# 2x16MUX_1.net
KiCad netlist of a schematic drawn in EAGLE
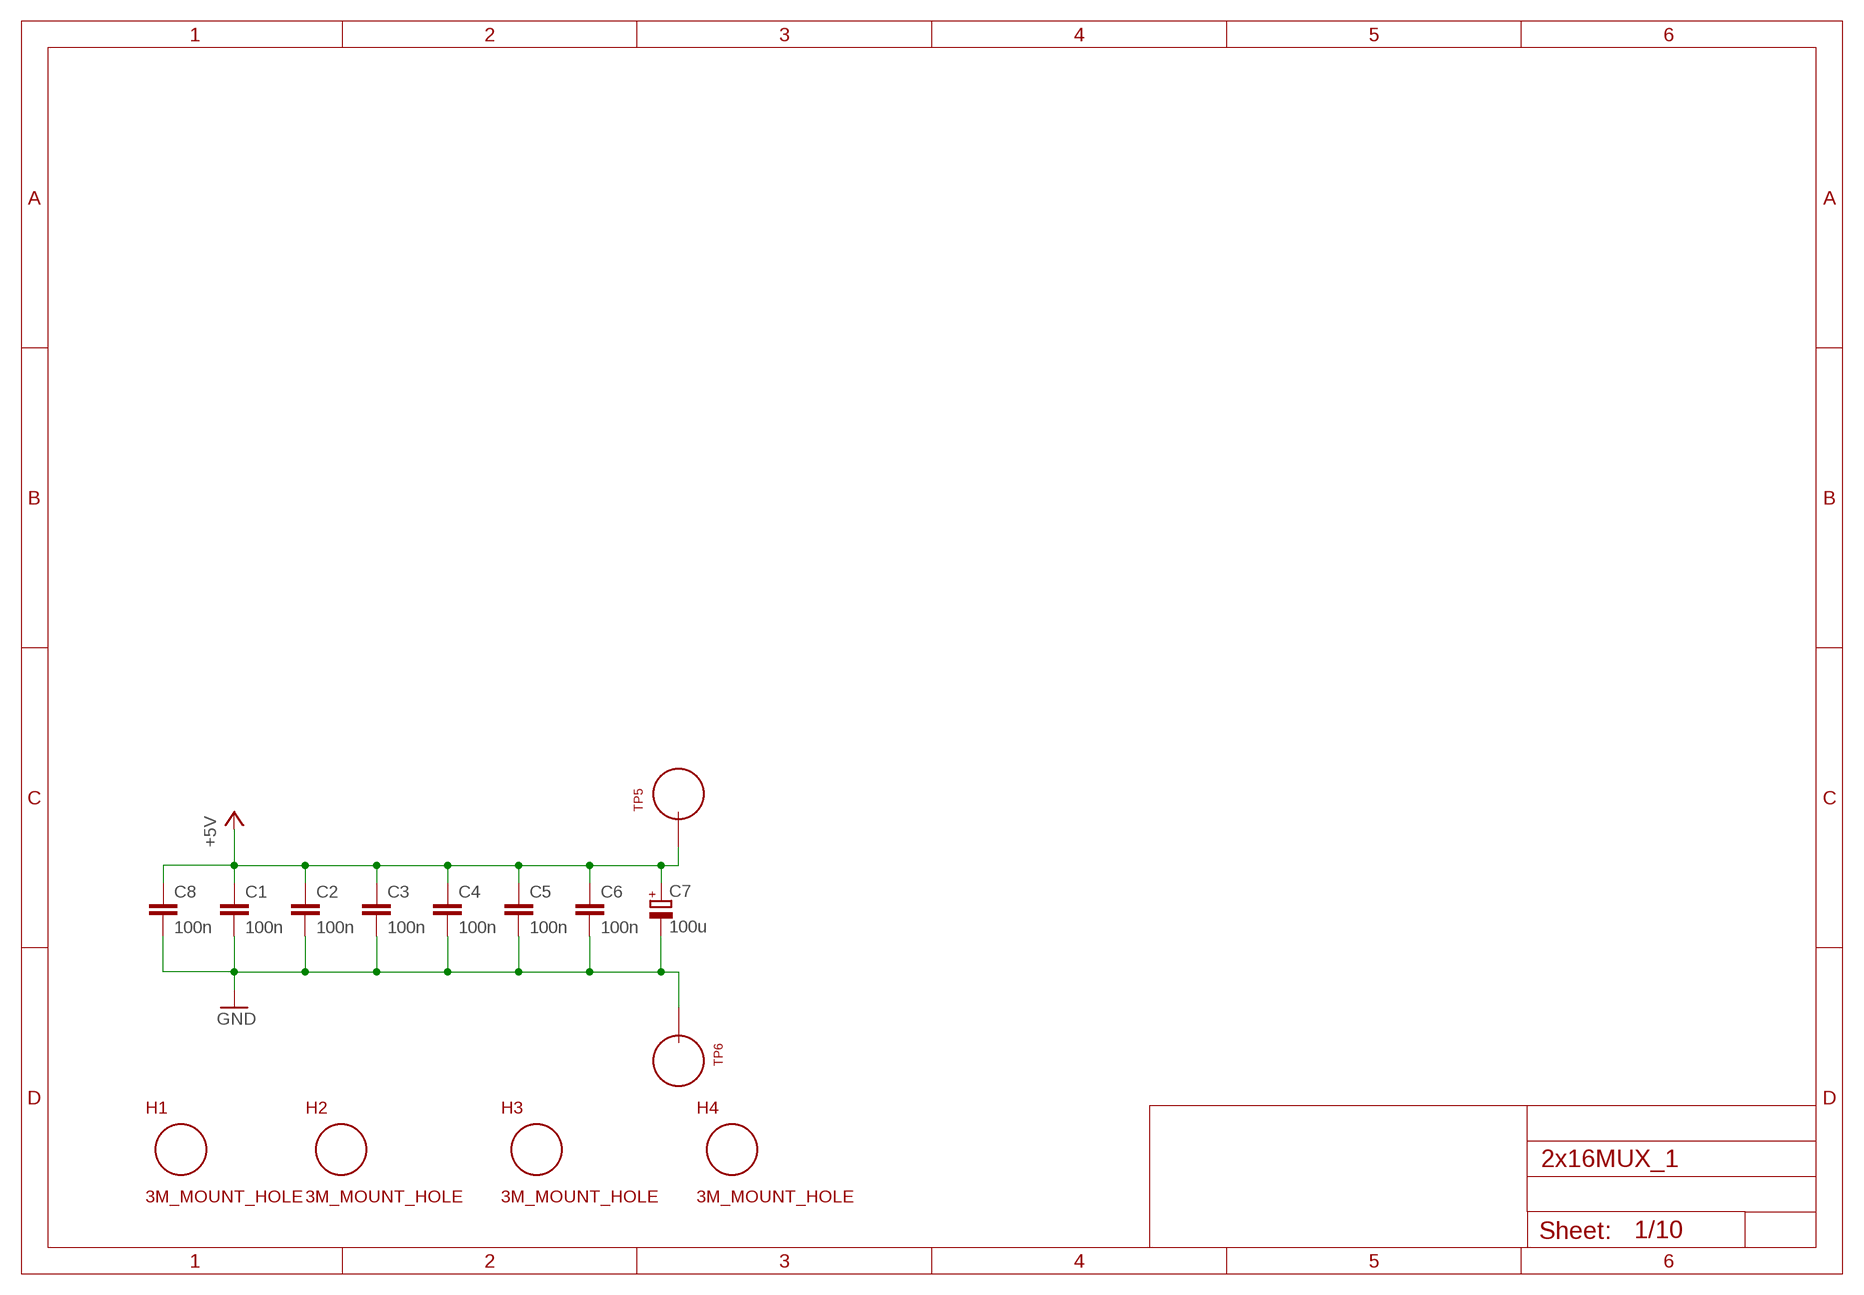
[diagram p0: schematic, sheet 1]
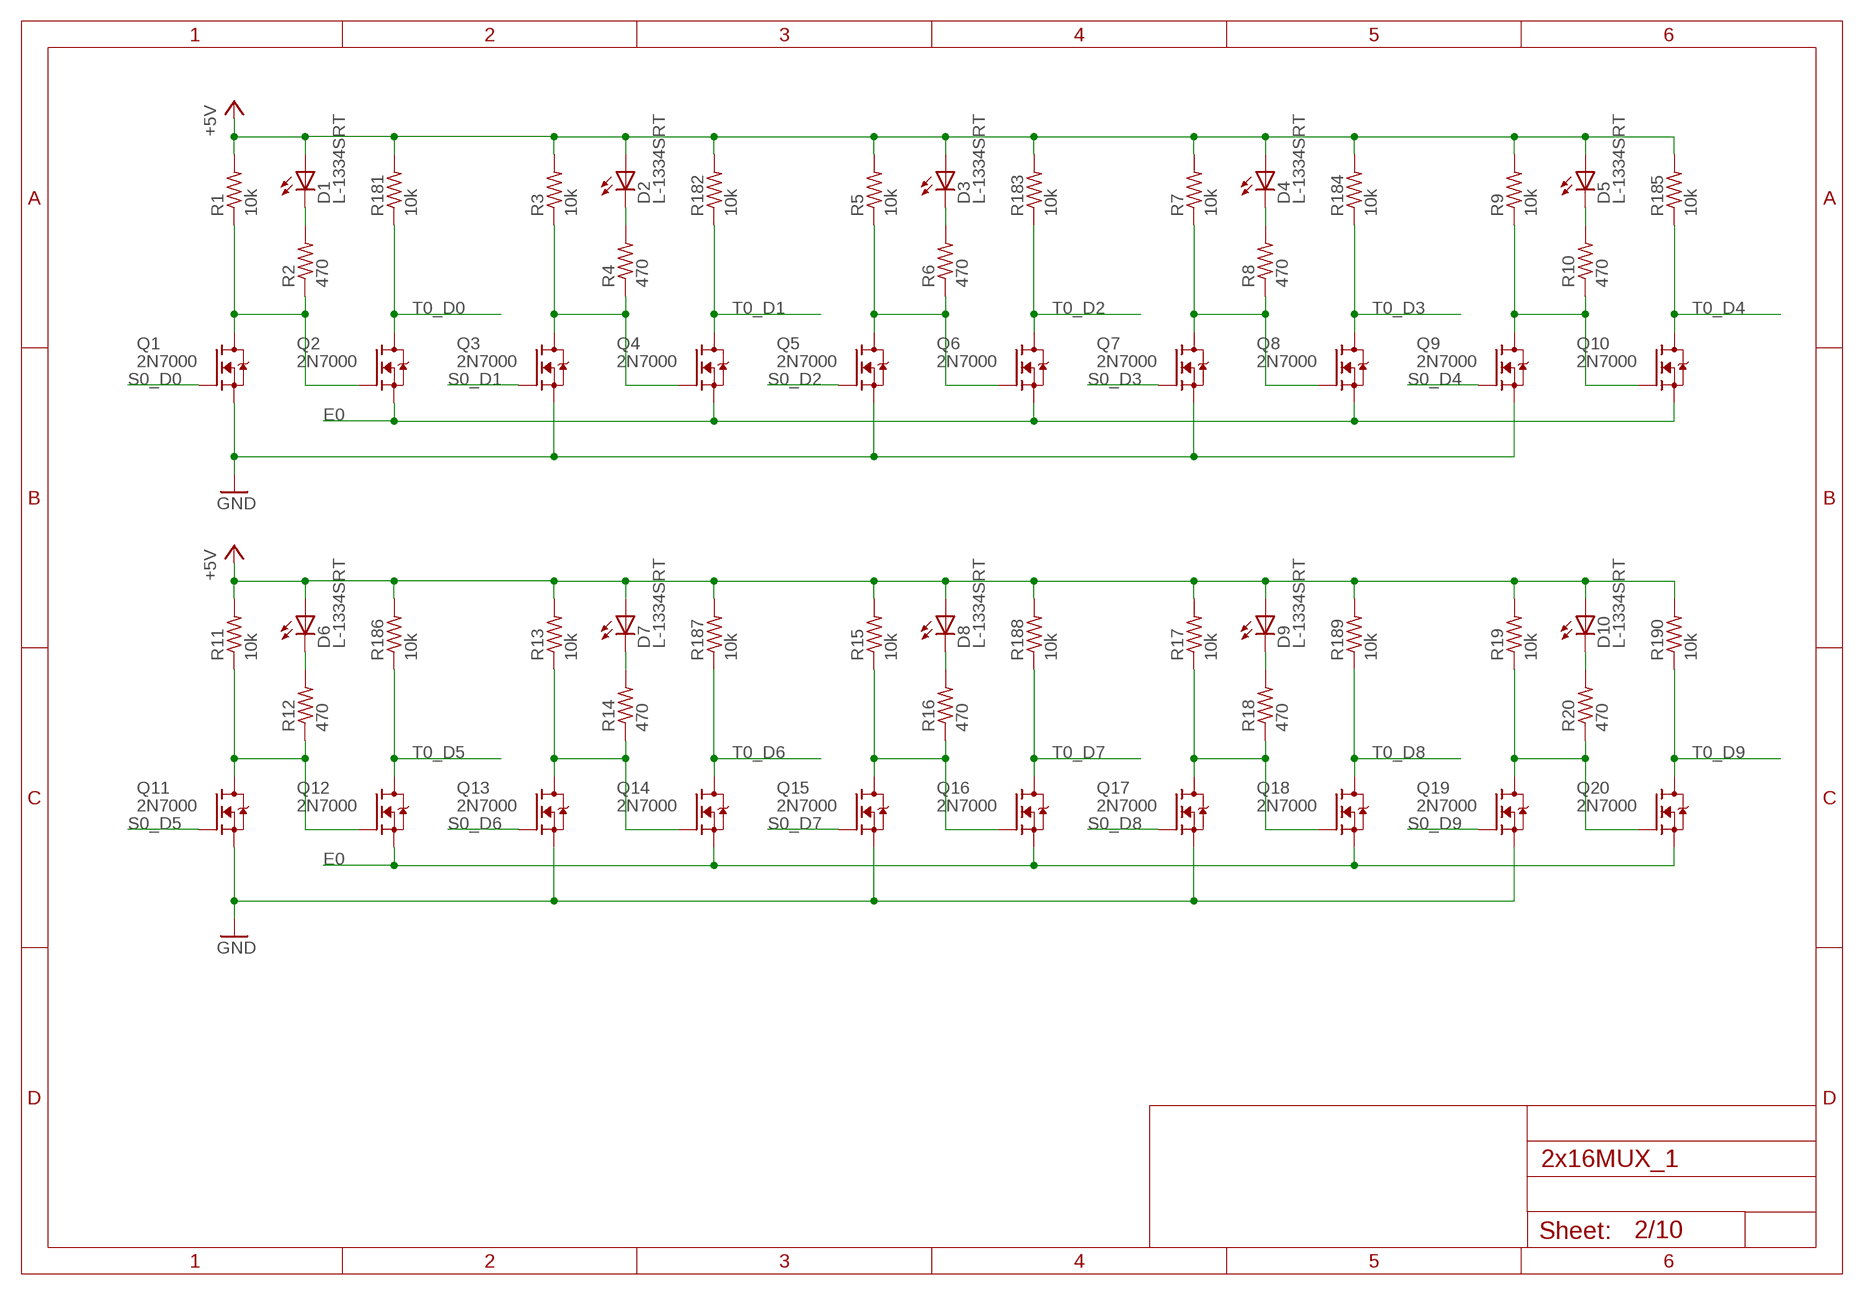
[diagram p1: schematic, sheet 2]
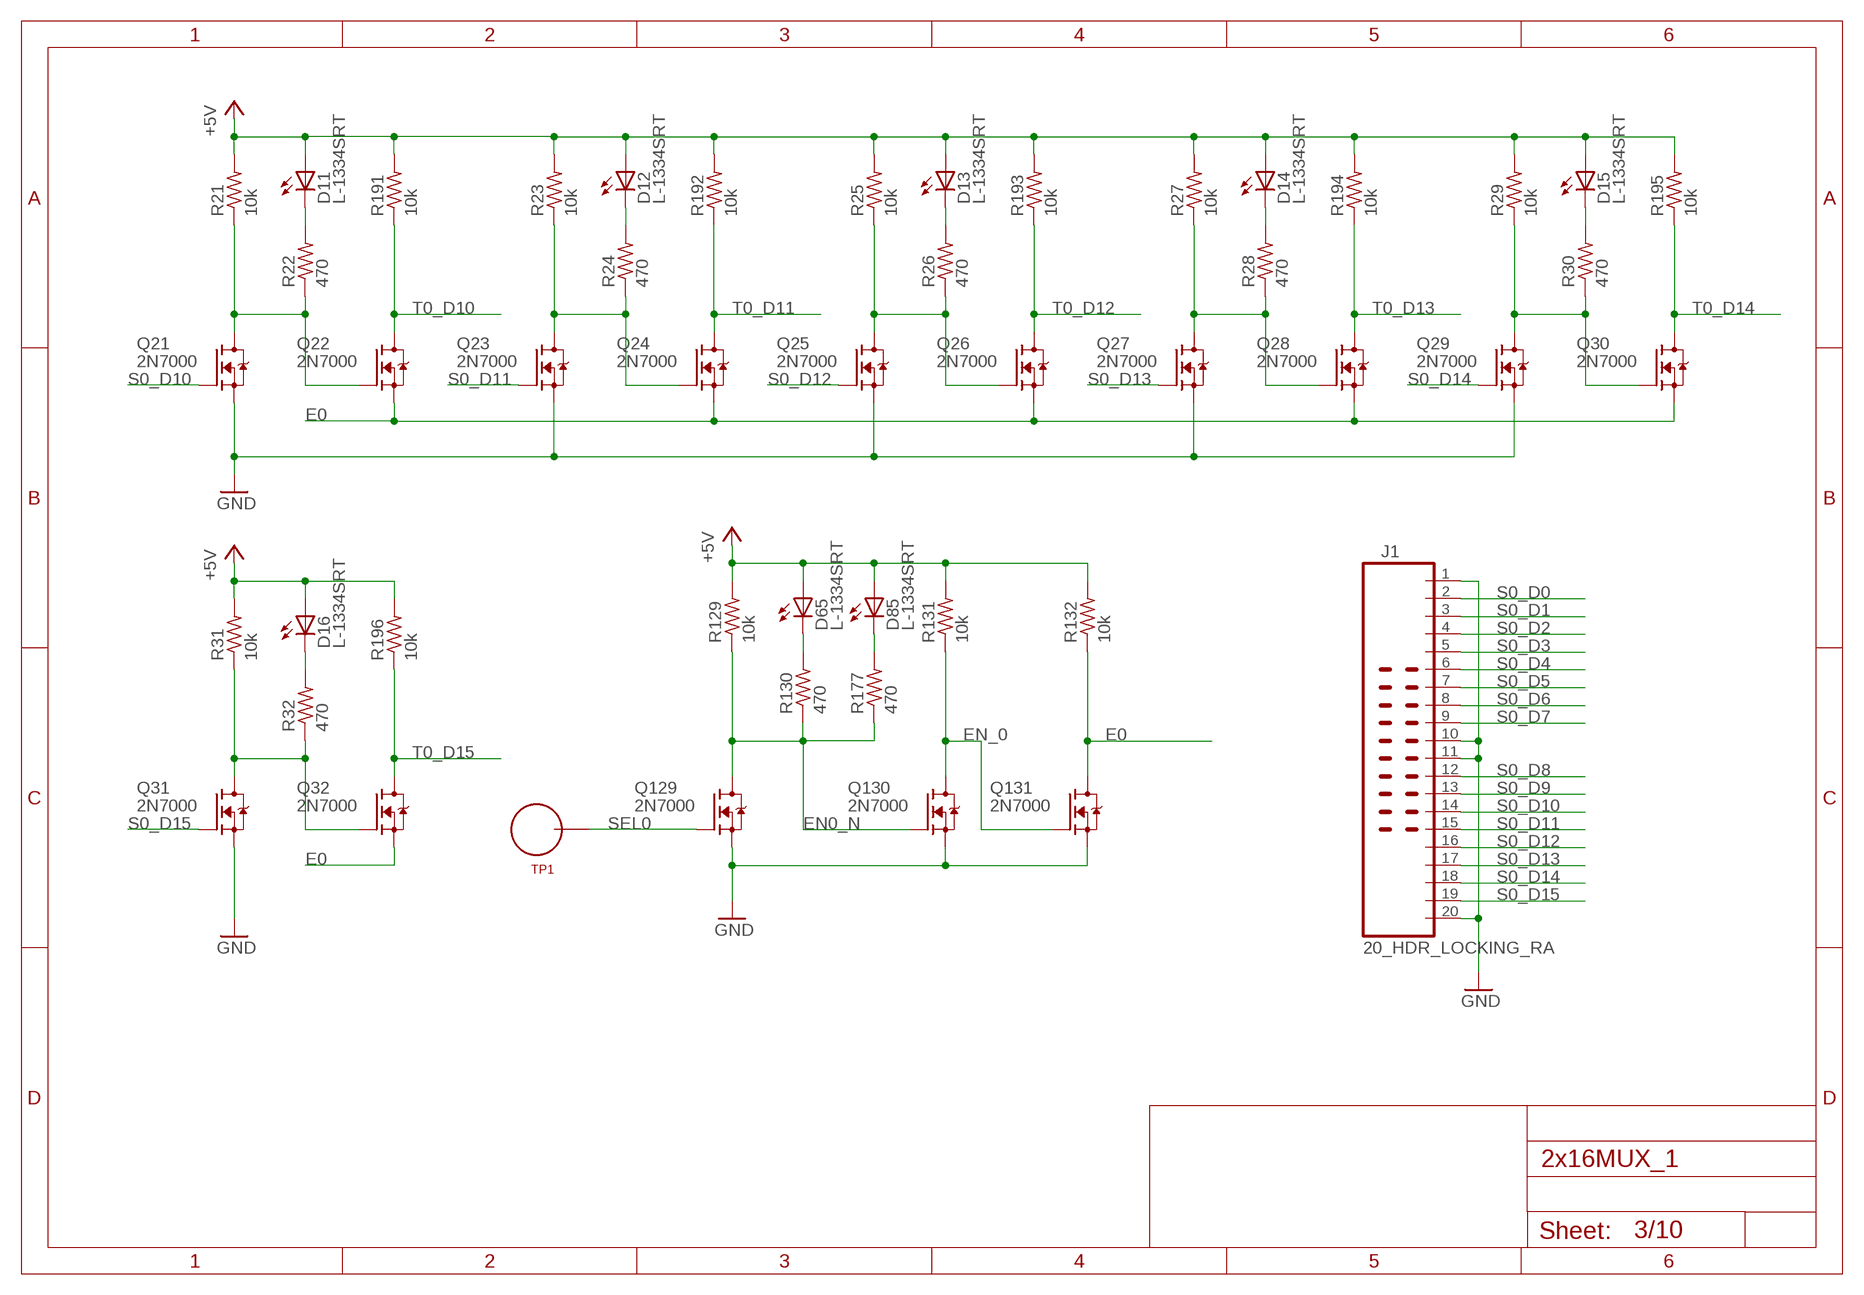
[diagram p2: schematic, sheet 3]
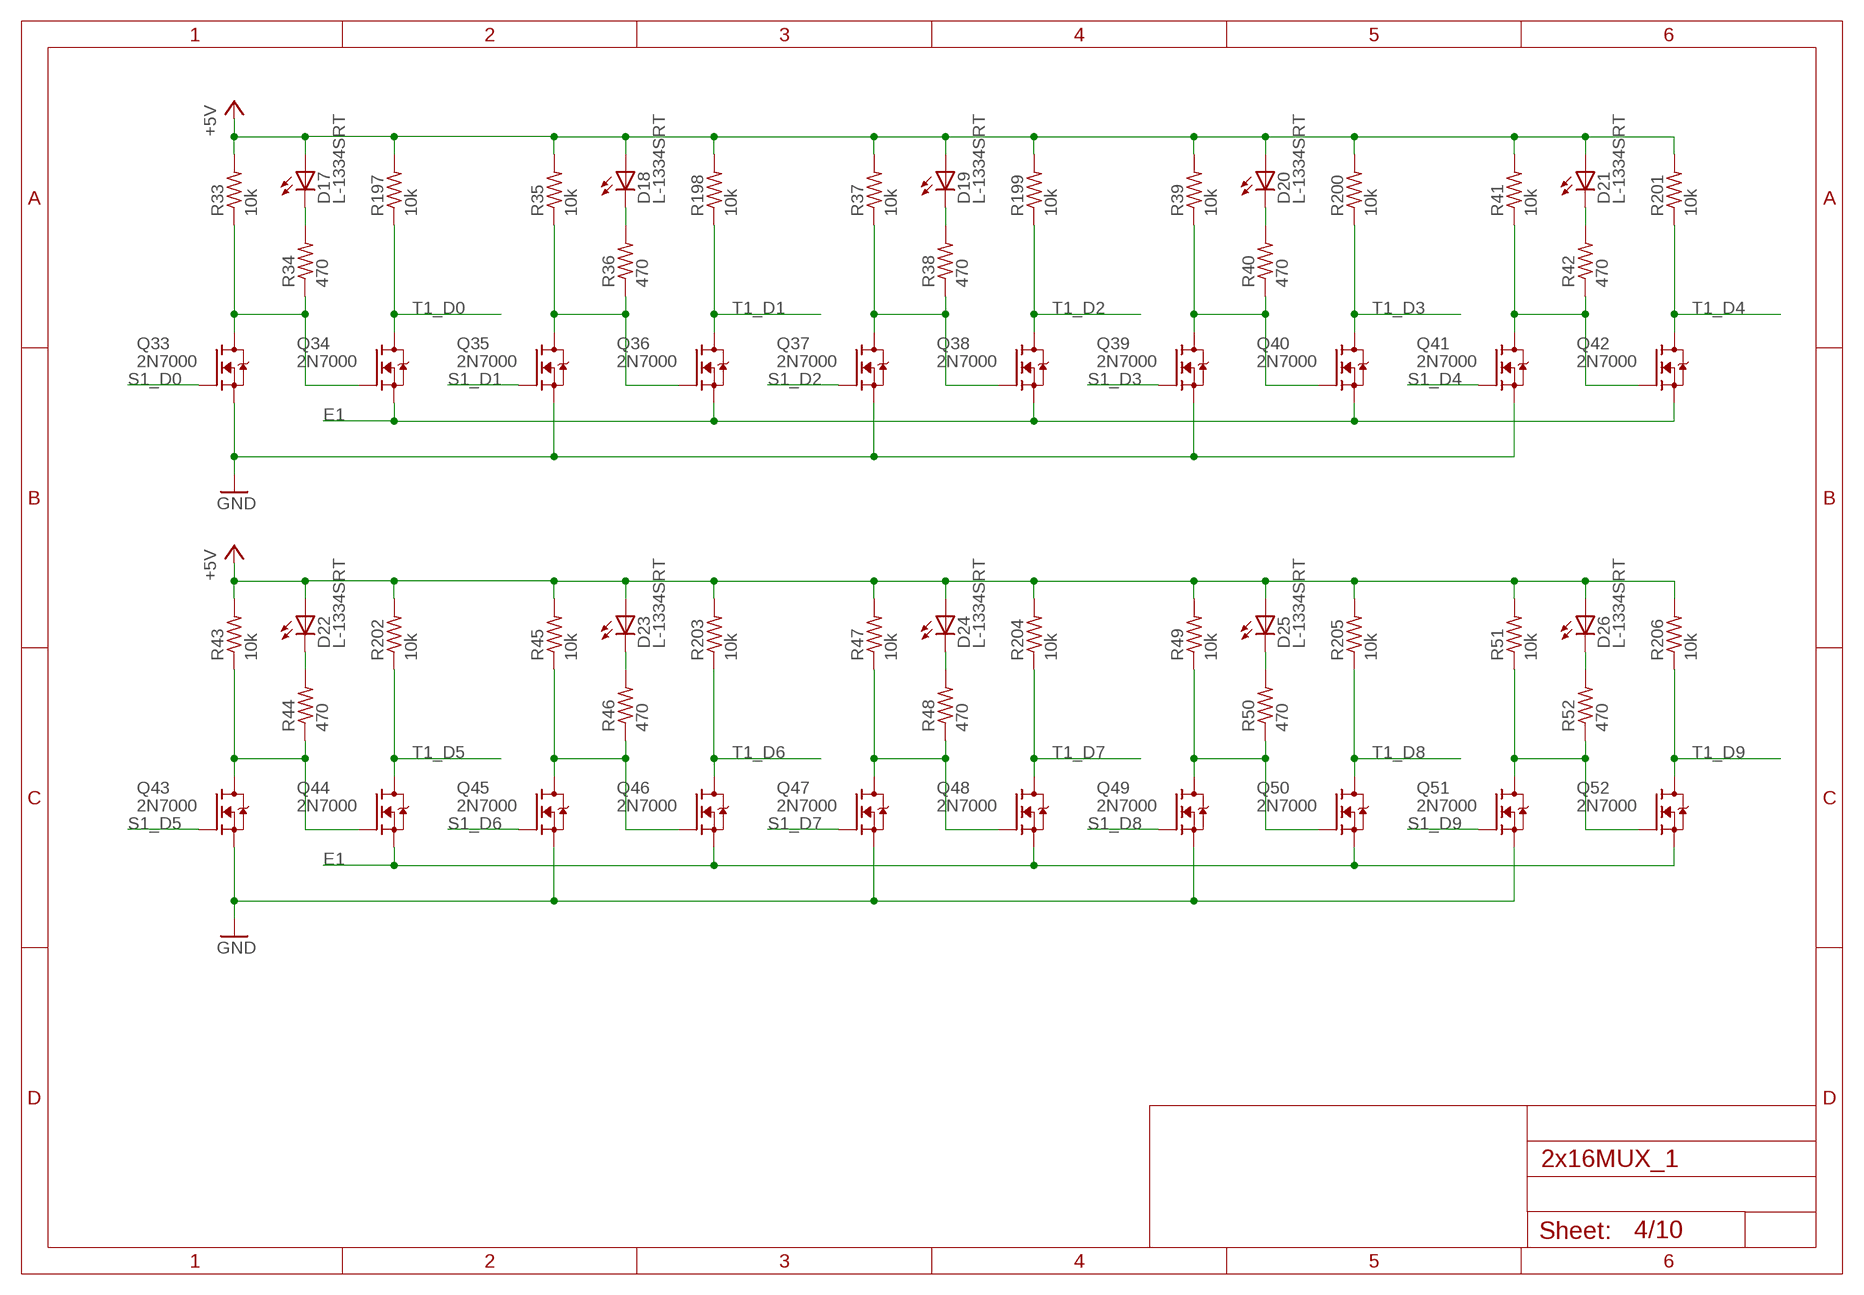
[diagram p3: schematic, sheet 4]
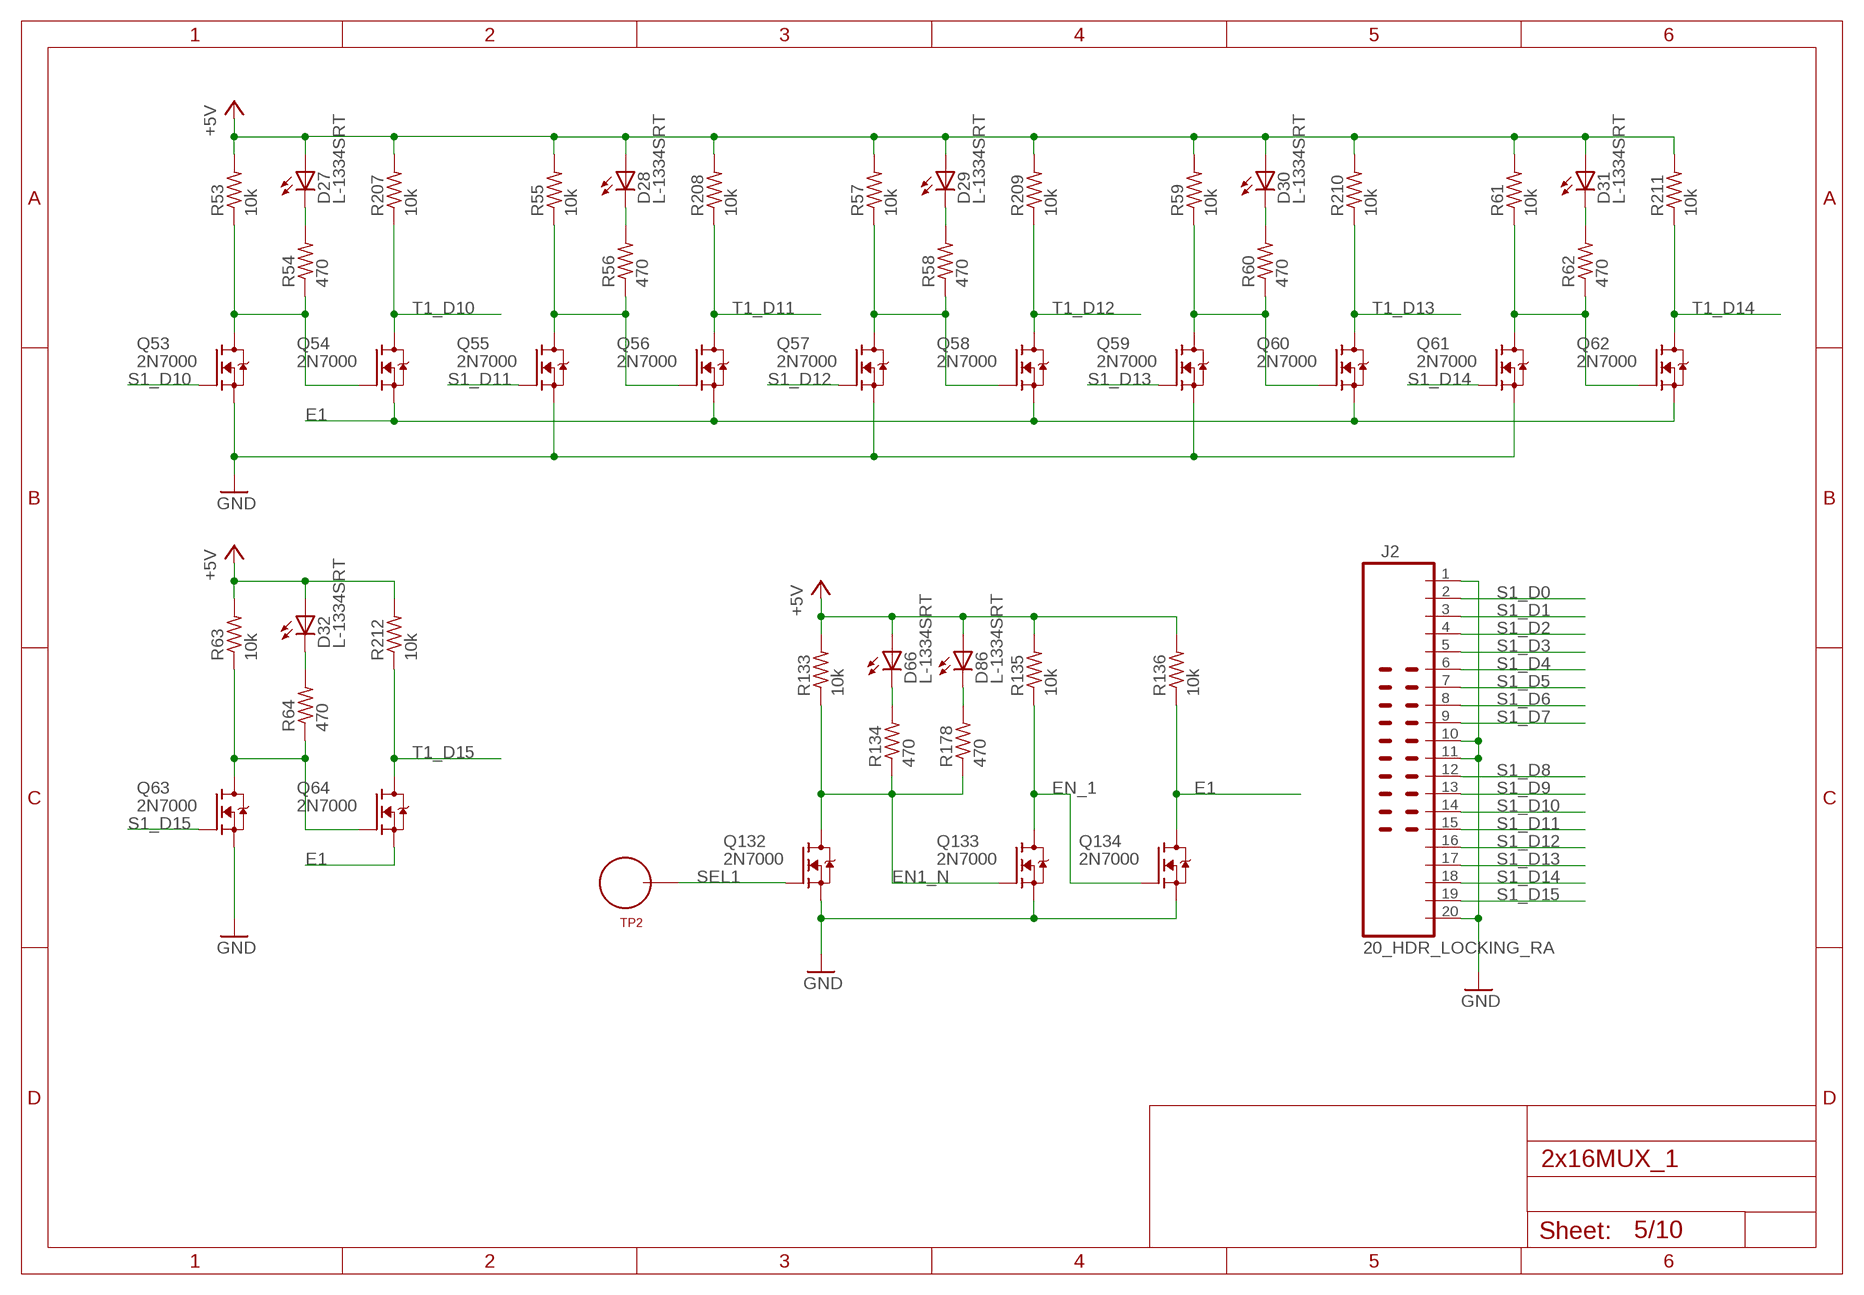
[diagram p4: schematic, sheet 5]
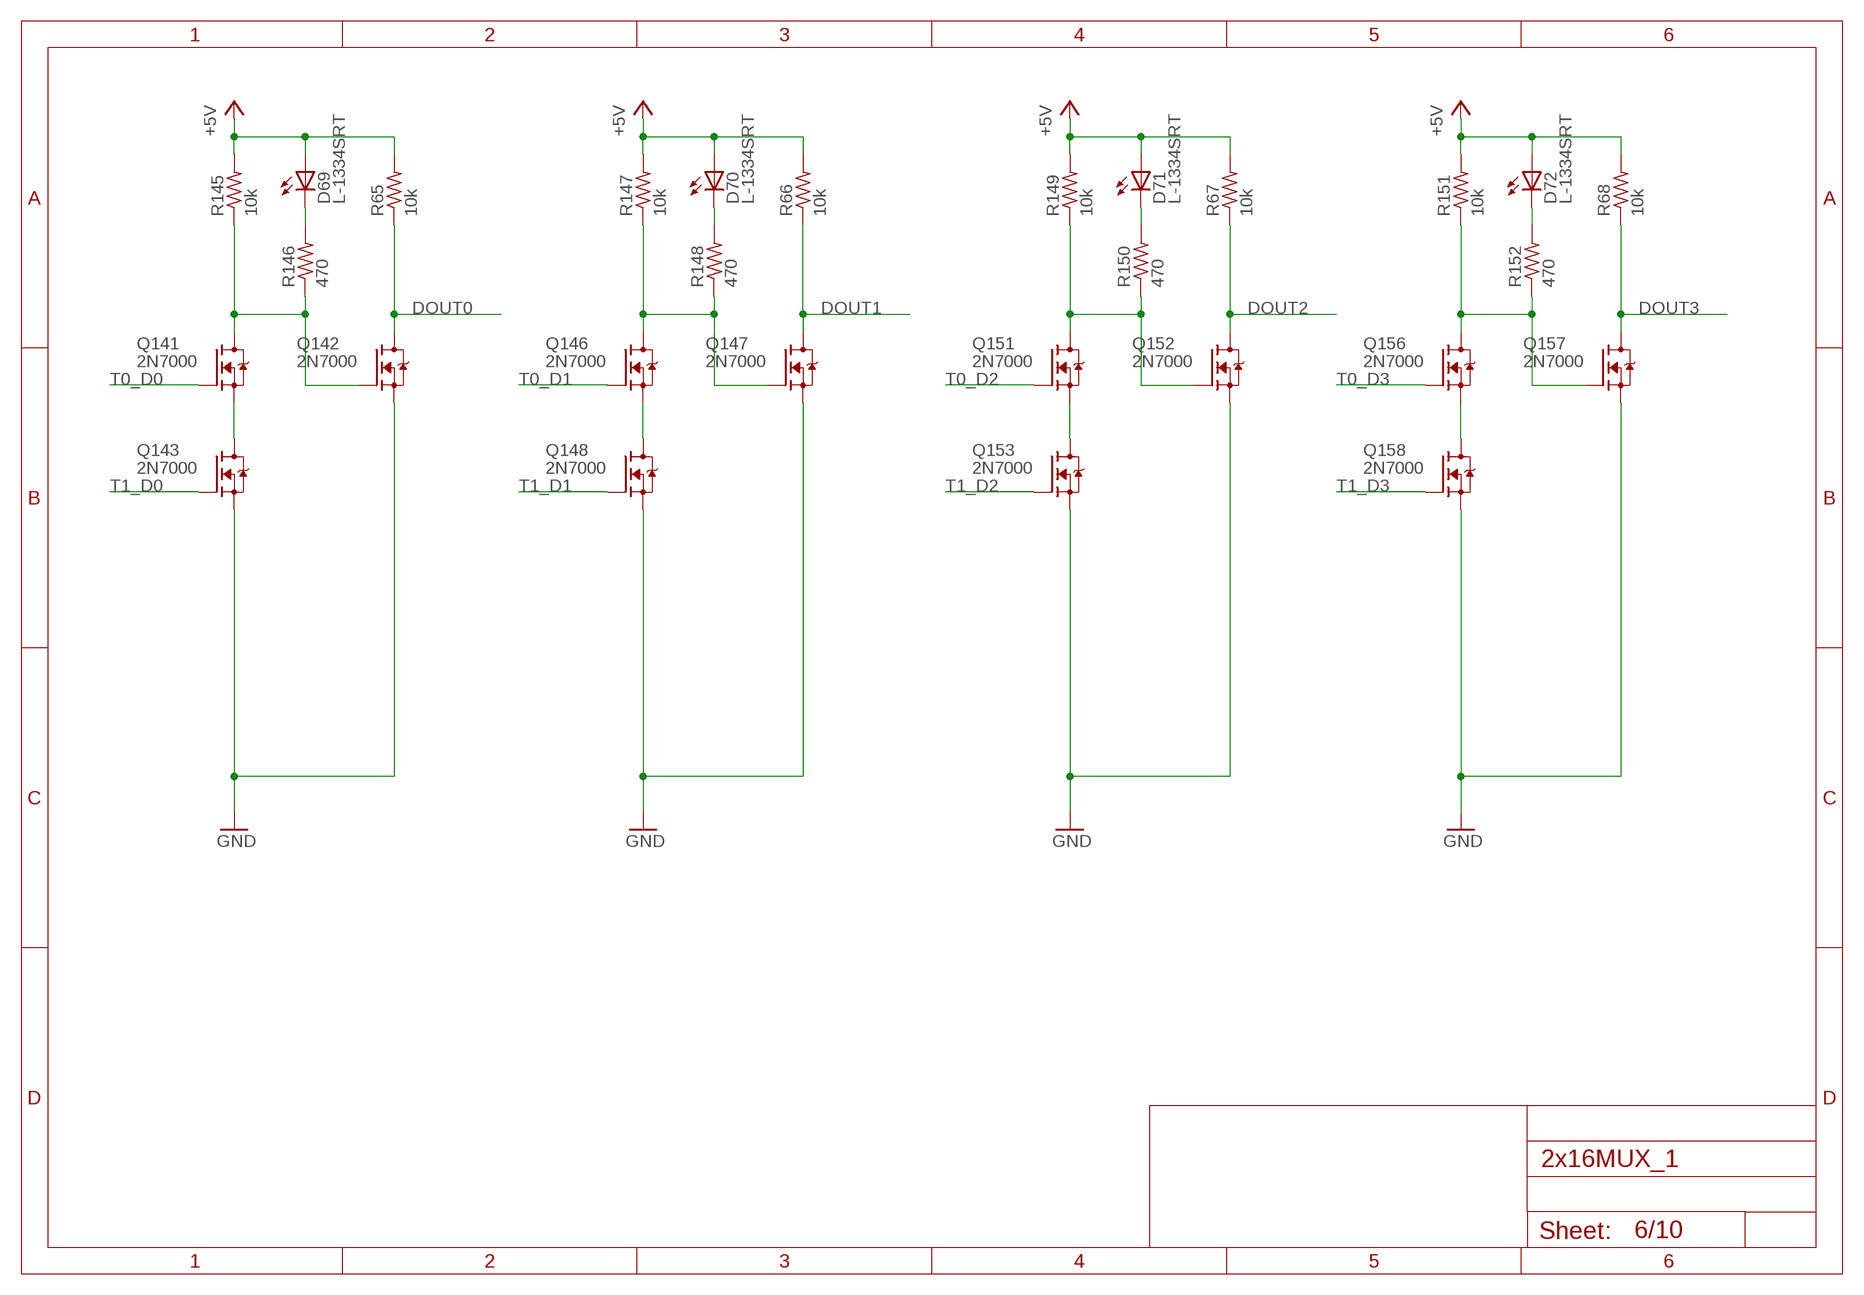
[diagram p5: schematic, sheet 6]
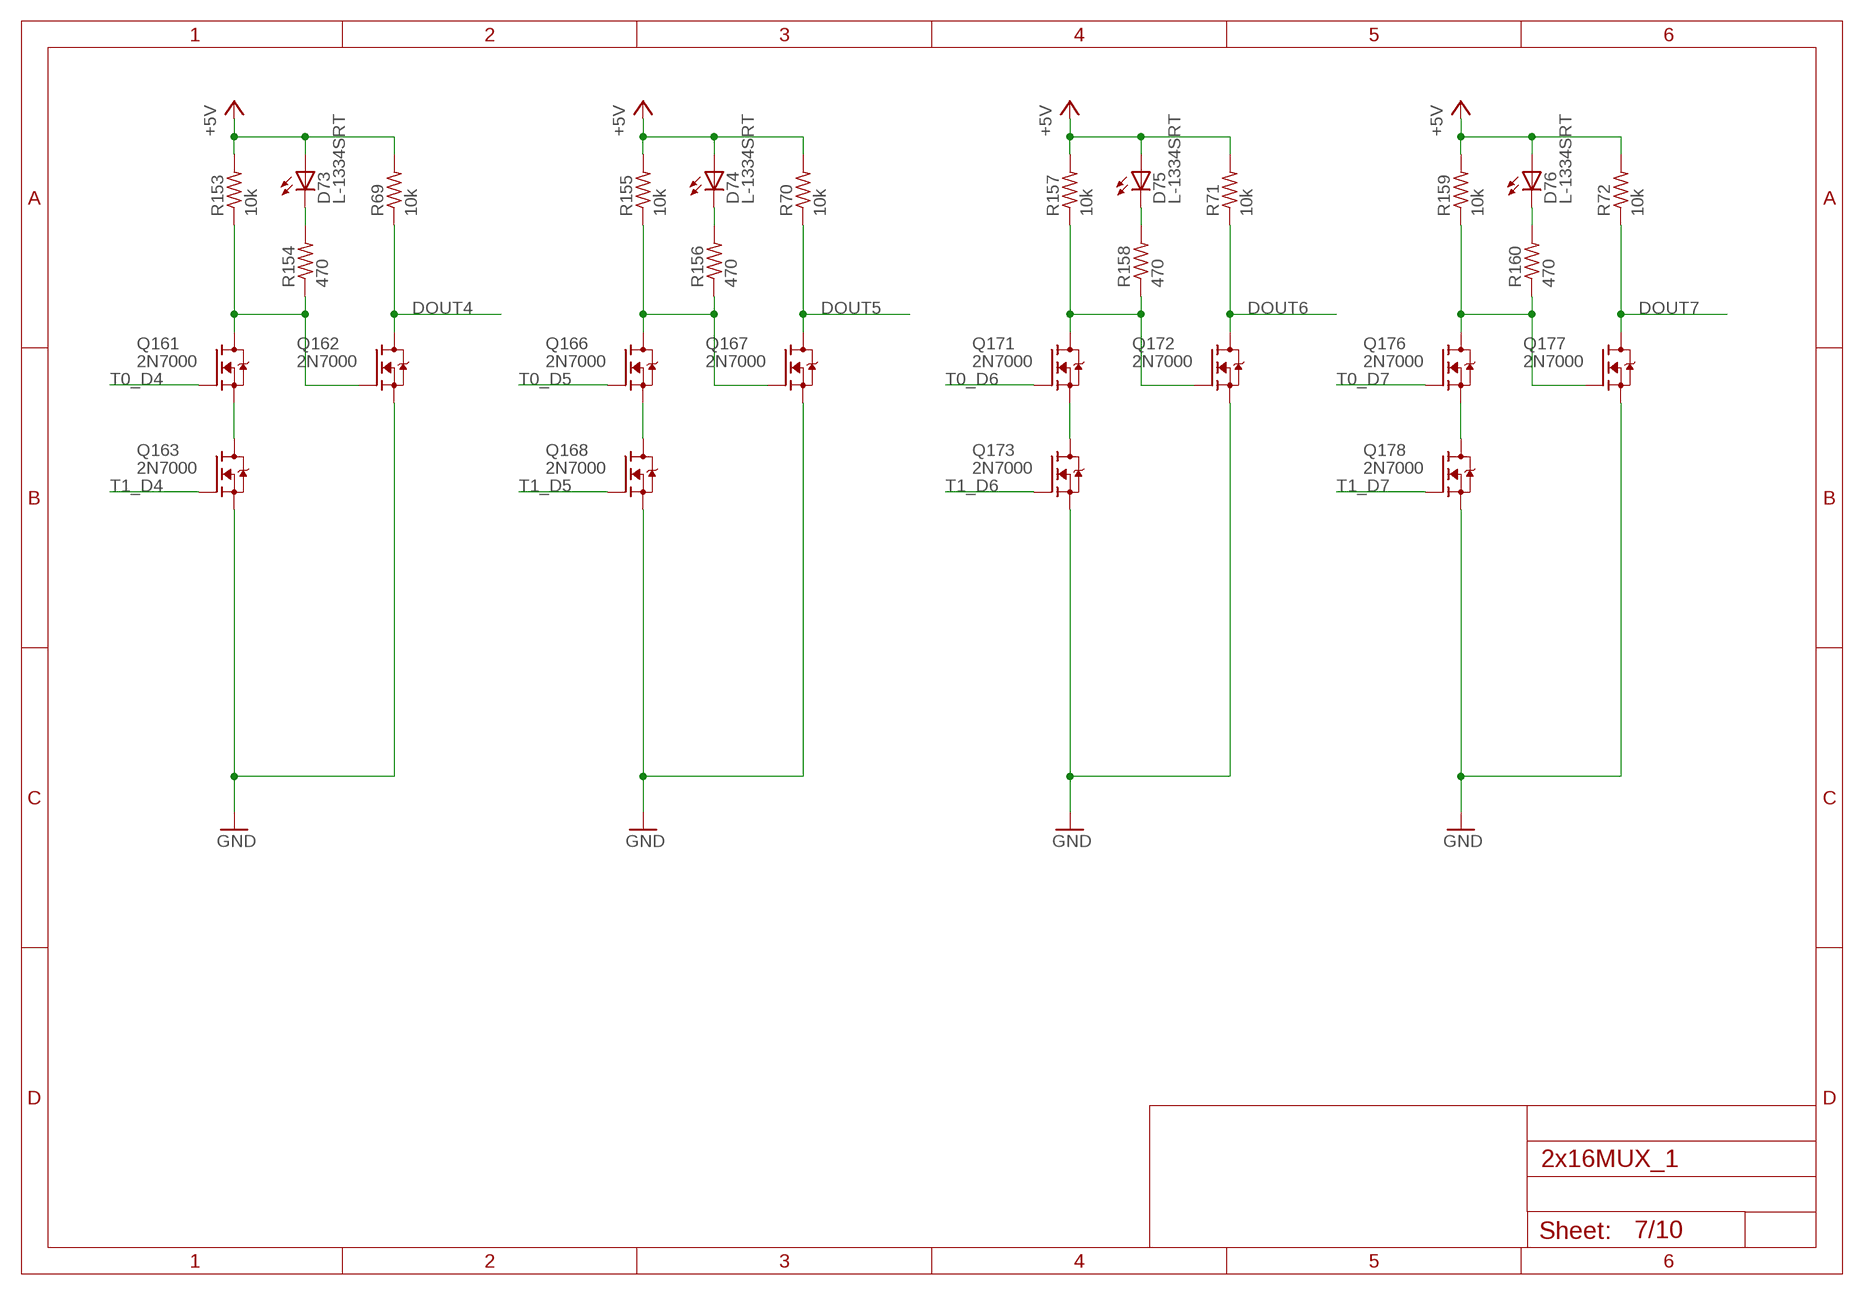
[diagram p6: schematic, sheet 7]
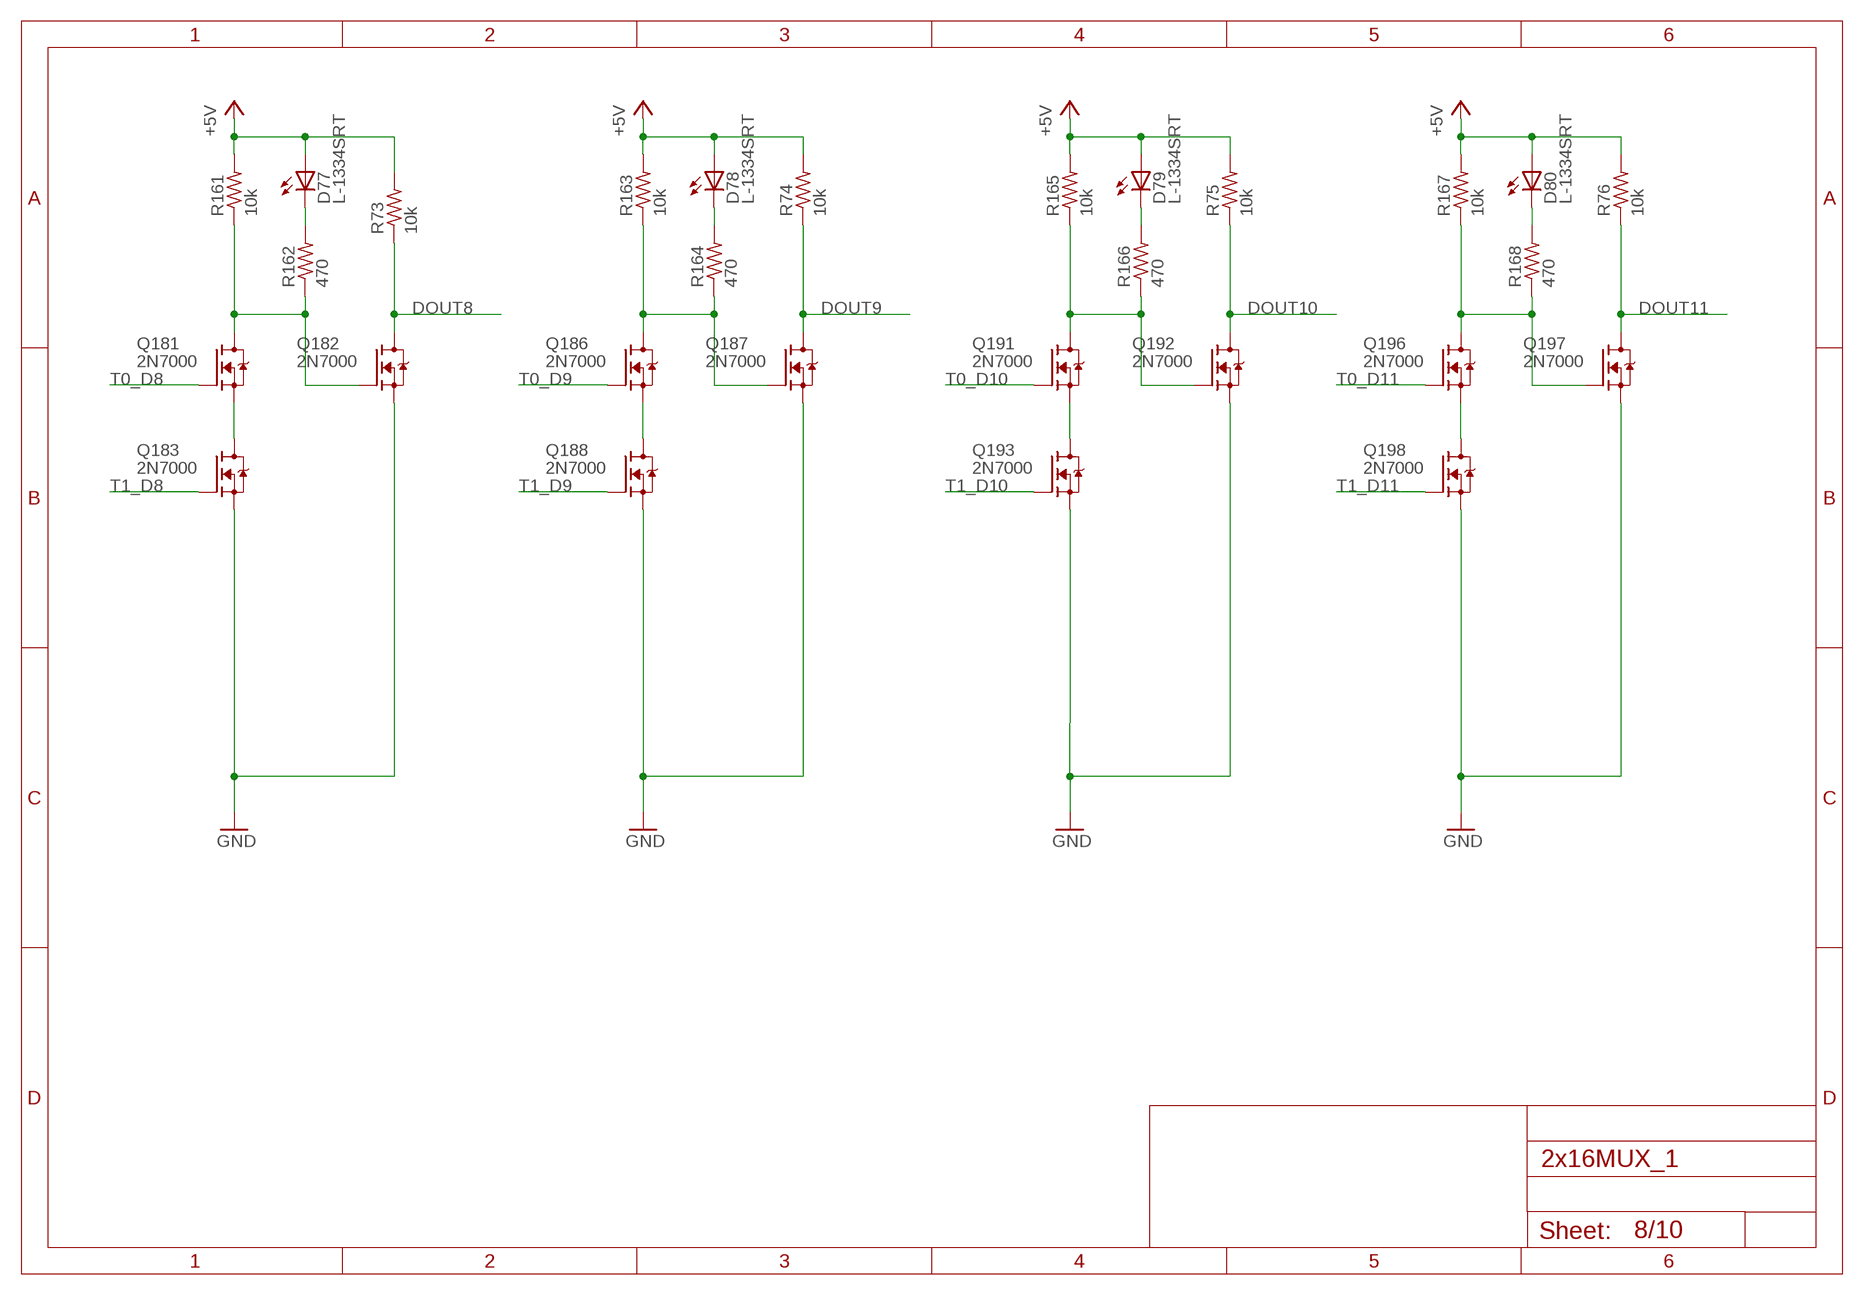
[diagram p7: schematic, sheet 8]
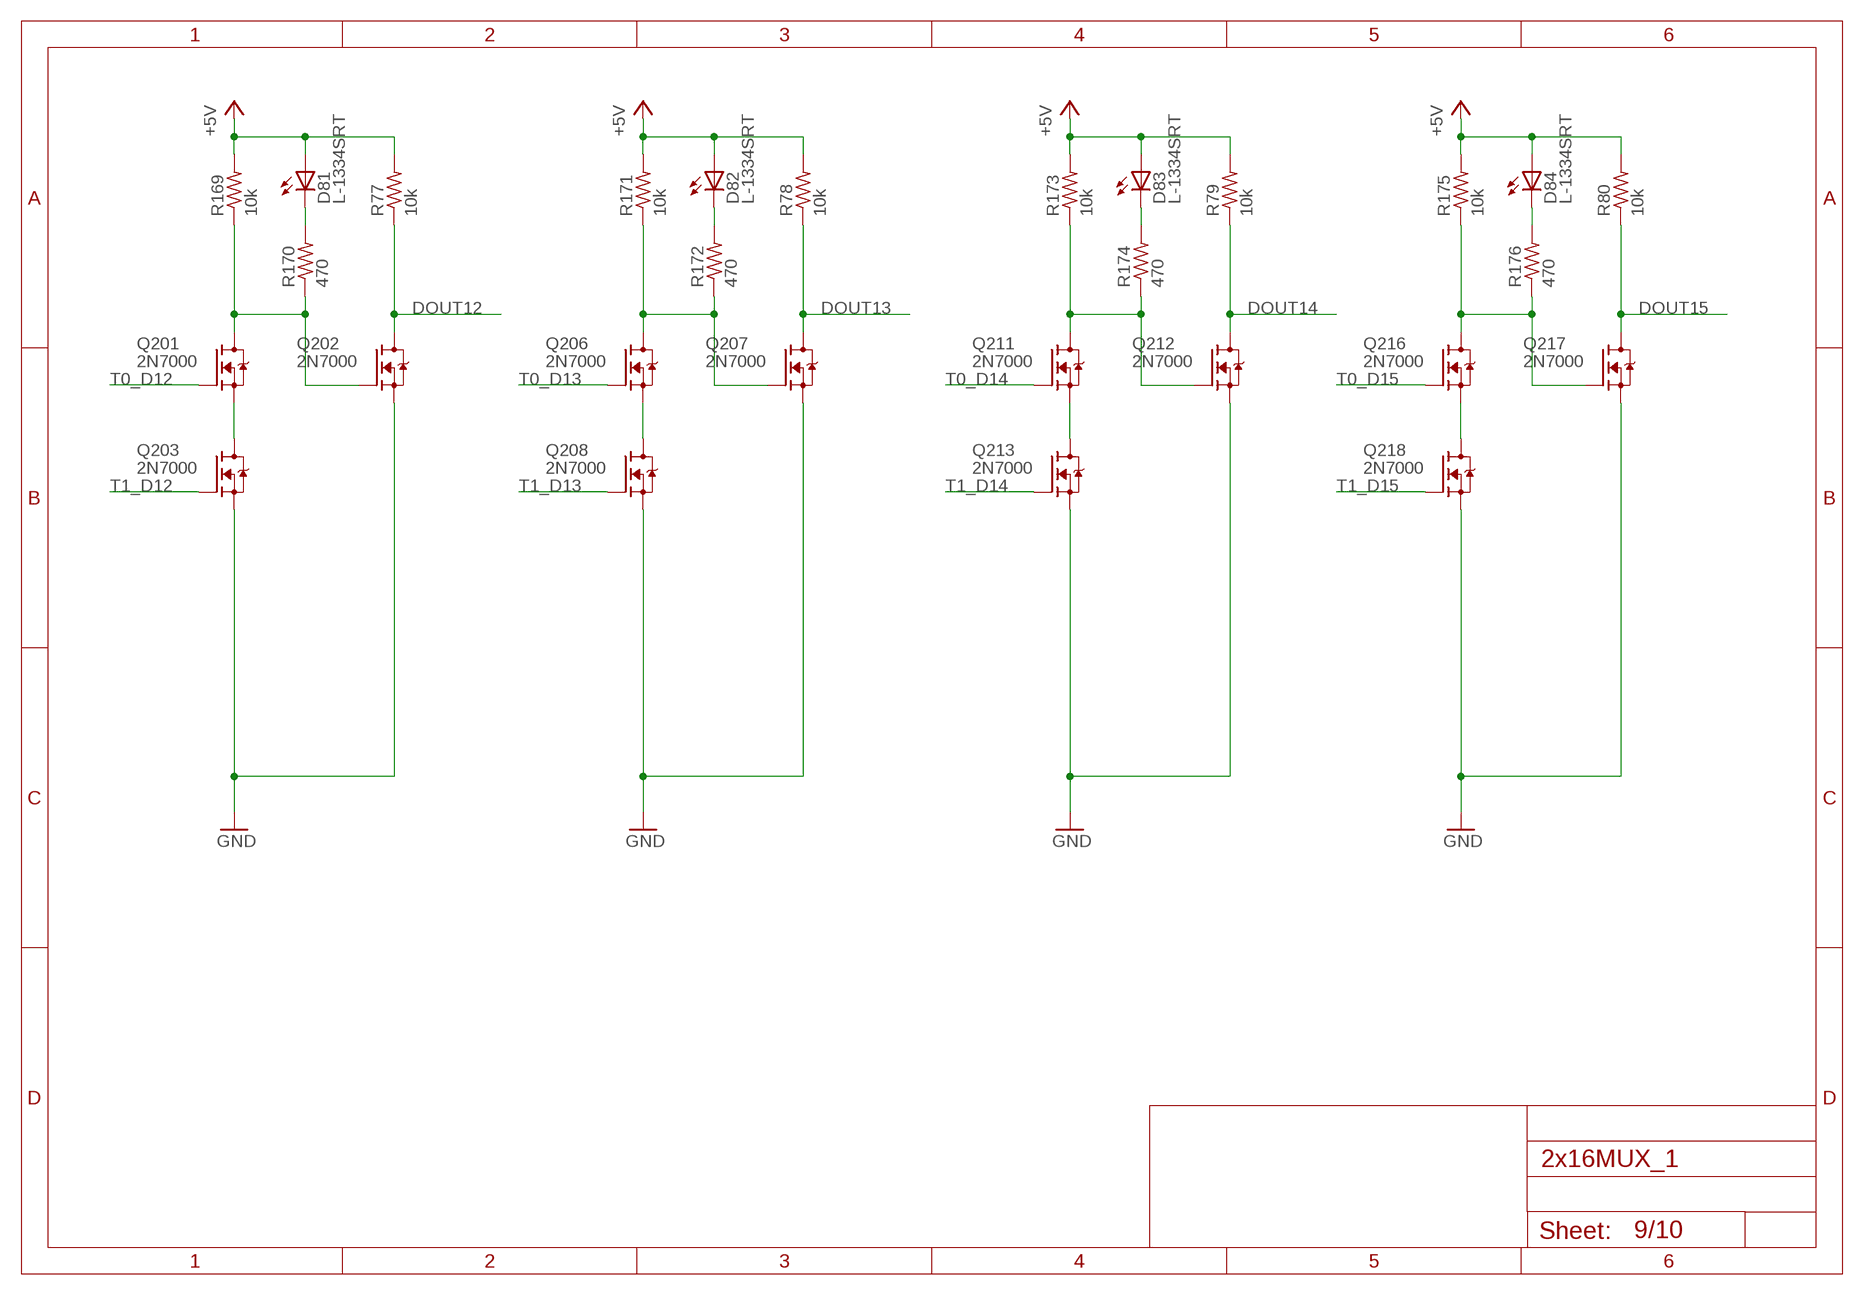
[diagram p8: schematic, sheet 9]
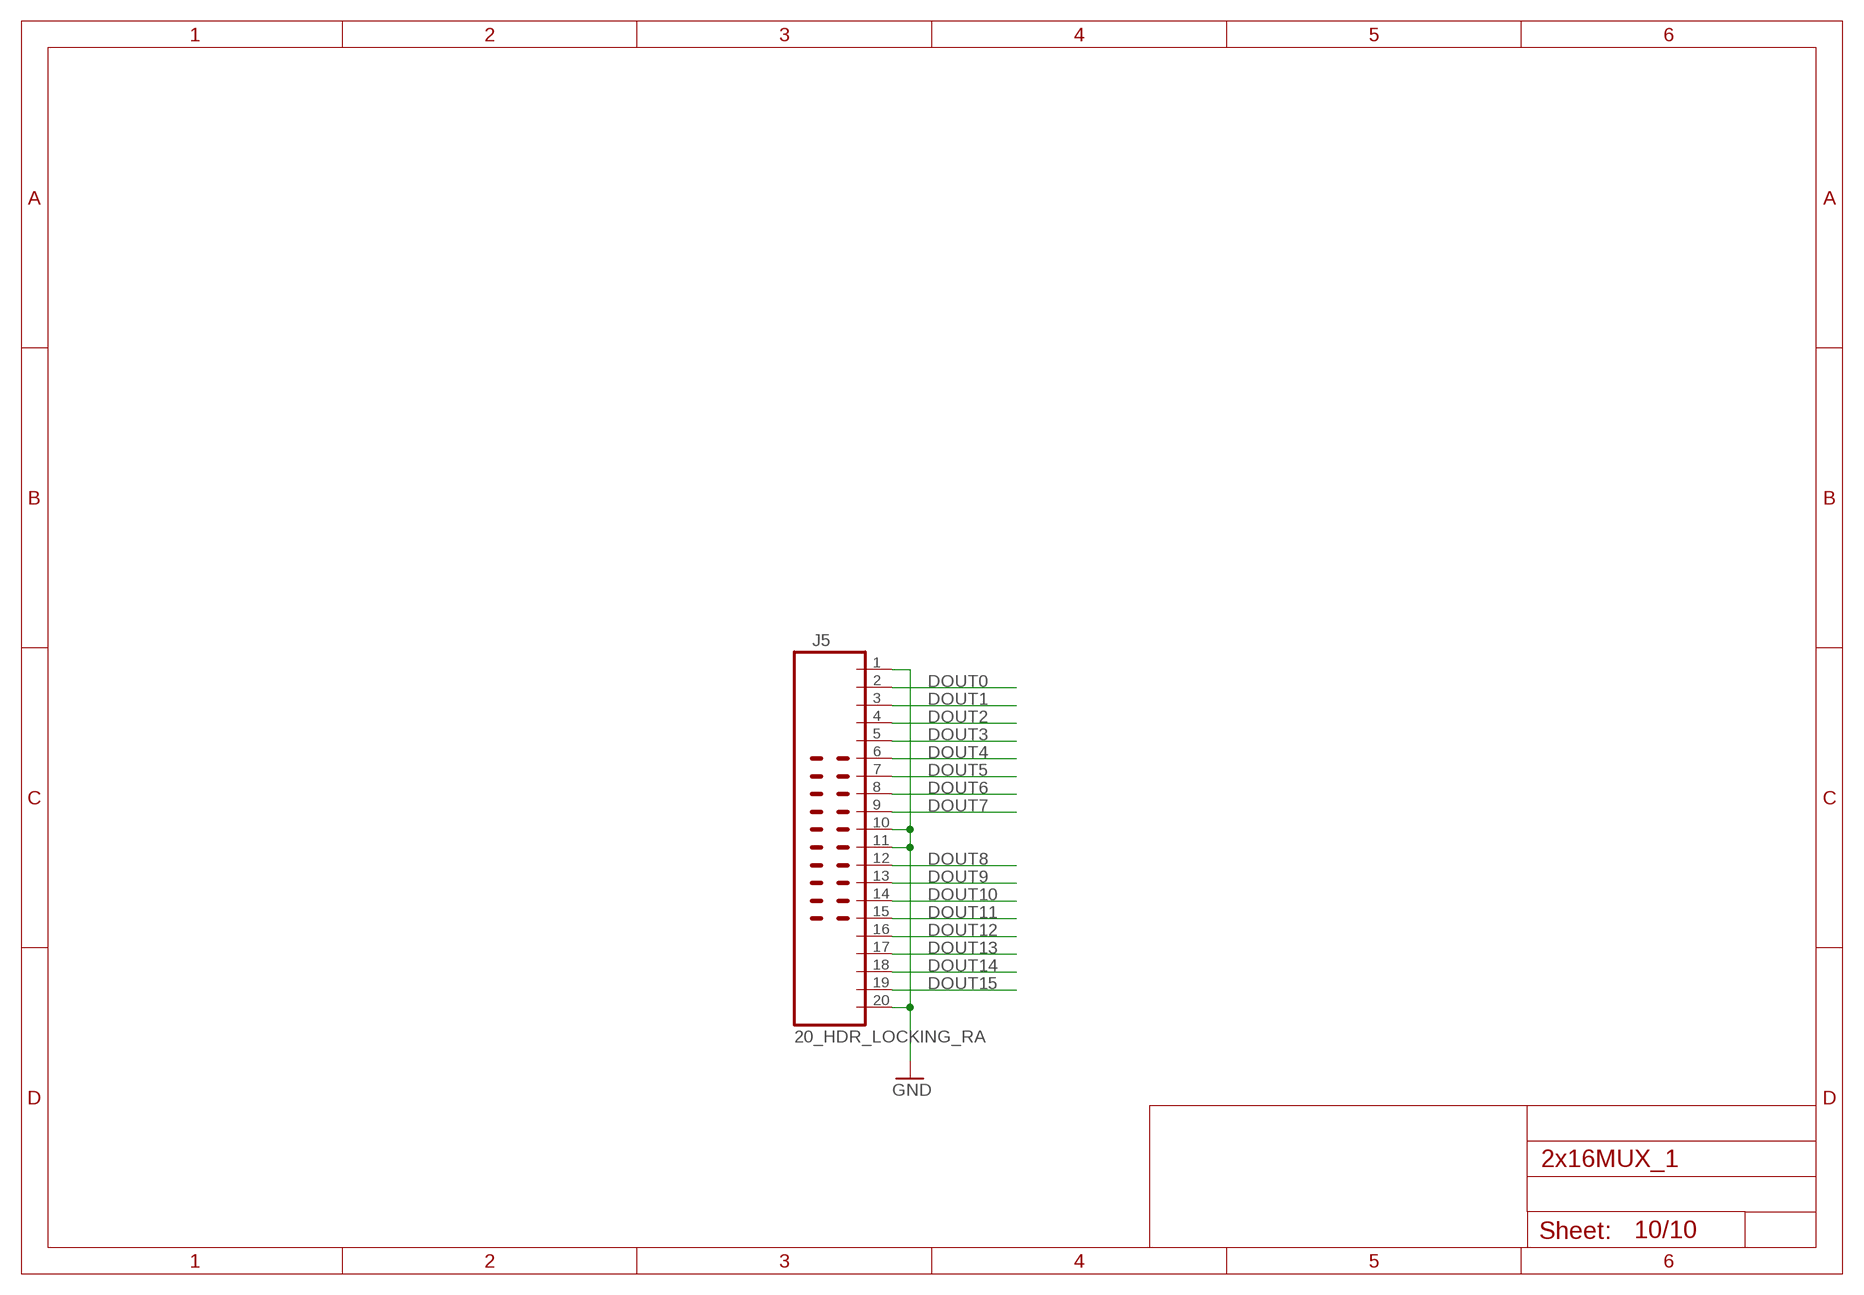
[diagram p9: schematic, sheet 10]

(export (version "E")
  (design (tool "Eeschema 10.0.6"))
  (components
    (comp (ref "J5")
      (value "20_HDR_LOCKING_RA")
      (footprint "eagle-import:20_HDR_LOCKING_RA")
      (libsource (lib "eagle-import") (part "20_HDR_LOCKING_RA"))
    )
    (comp (ref "D27")
      (value "L-1334SRT")
      (footprint "eagle-import:LED3MM")
      (libsource (lib "eagle-import") (part "L-1334SRT"))
    )
    (comp (ref "D28")
      (value "L-1334SRT")
      (footprint "eagle-import:LED3MM")
      (libsource (lib "eagle-import") (part "L-1334SRT"))
    )
    (comp (ref "D29")
      (value "L-1334SRT")
      (footprint "eagle-import:LED3MM")
      (libsource (lib "eagle-import") (part "L-1334SRT"))
    )
    (comp (ref "D30")
      (value "L-1334SRT")
      (footprint "eagle-import:LED3MM")
      (libsource (lib "eagle-import") (part "L-1334SRT"))
    )
    (comp (ref "D31")
      (value "L-1334SRT")
      (footprint "eagle-import:LED3MM")
      (libsource (lib "eagle-import") (part "L-1334SRT"))
    )
    (comp (ref "D32")
      (value "L-1334SRT")
      (footprint "eagle-import:LED3MM")
      (libsource (lib "eagle-import") (part "L-1334SRT"))
    )
    (comp (ref "D66")
      (value "L-1334SRT")
      (footprint "eagle-import:LED3MM")
      (libsource (lib "eagle-import") (part "L-1334SRT"))
    )
    (comp (ref "D86")
      (value "L-1334SRT")
      (footprint "eagle-import:LED3MM")
      (libsource (lib "eagle-import") (part "L-1334SRT"))
    )
    (comp (ref "J2")
      (value "20_HDR_LOCKING_RA")
      (footprint "eagle-import:20_HDR_LOCKING_RA")
      (libsource (lib "eagle-import") (part "20_HDR_LOCKING_RA"))
    )
    (comp (ref "Q53")
      (value "2N7000")
      (footprint "eagle-import:TO92-DGS")
      (libsource (lib "eagle-import") (part "2N7000"))
    )
    (comp (ref "Q54")
      (value "2N7000")
      (footprint "eagle-import:TO92-DGS")
      (libsource (lib "eagle-import") (part "2N7000"))
    )
    (comp (ref "Q55")
      (value "2N7000")
      (footprint "eagle-import:TO92-DGS")
      (libsource (lib "eagle-import") (part "2N7000"))
    )
    (comp (ref "Q56")
      (value "2N7000")
      (footprint "eagle-import:TO92-DGS")
      (libsource (lib "eagle-import") (part "2N7000"))
    )
    (comp (ref "Q57")
      (value "2N7000")
      (footprint "eagle-import:TO92-DGS")
      (libsource (lib "eagle-import") (part "2N7000"))
    )
    (comp (ref "Q58")
      (value "2N7000")
      (footprint "eagle-import:TO92-DGS")
      (libsource (lib "eagle-import") (part "2N7000"))
    )
    (comp (ref "Q59")
      (value "2N7000")
      (footprint "eagle-import:TO92-DGS")
      (libsource (lib "eagle-import") (part "2N7000"))
    )
    (comp (ref "Q60")
      (value "2N7000")
      (footprint "eagle-import:TO92-DGS")
      (libsource (lib "eagle-import") (part "2N7000"))
    )
    (comp (ref "Q61")
      (value "2N7000")
      (footprint "eagle-import:TO92-DGS")
      (libsource (lib "eagle-import") (part "2N7000"))
    )
    (comp (ref "Q62")
      (value "2N7000")
      (footprint "eagle-import:TO92-DGS")
      (libsource (lib "eagle-import") (part "2N7000"))
    )
    (comp (ref "Q63")
      (value "2N7000")
      (footprint "eagle-import:TO92-DGS")
      (libsource (lib "eagle-import") (part "2N7000"))
    )
    (comp (ref "Q64")
      (value "2N7000")
      (footprint "eagle-import:TO92-DGS")
      (libsource (lib "eagle-import") (part "2N7000"))
    )
    (comp (ref "Q132")
      (value "2N7000")
      (footprint "eagle-import:TO92-DGS")
      (libsource (lib "eagle-import") (part "2N7000"))
    )
    (comp (ref "Q133")
      (value "2N7000")
      (footprint "eagle-import:TO92-DGS")
      (libsource (lib "eagle-import") (part "2N7000"))
    )
    (comp (ref "Q134")
      (value "2N7000")
      (footprint "eagle-import:TO92-DGS")
      (libsource (lib "eagle-import") (part "2N7000"))
    )
    (comp (ref "R53")
      (value "10k")
      (footprint "eagle-import:R_P2INCH")
      (libsource (lib "eagle-import") (part "R_P2INCH"))
    )
    (comp (ref "R54")
      (value "470")
      (footprint "eagle-import:R_P2INCH")
      (libsource (lib "eagle-import") (part "R_P2INCH"))
    )
    (comp (ref "R55")
      (value "10k")
      (footprint "eagle-import:R_P2INCH")
      (libsource (lib "eagle-import") (part "R_P2INCH"))
    )
    (comp (ref "R56")
      (value "470")
      (footprint "eagle-import:R_P2INCH")
      (libsource (lib "eagle-import") (part "R_P2INCH"))
    )
    (comp (ref "R57")
      (value "10k")
      (footprint "eagle-import:R_P2INCH")
      (libsource (lib "eagle-import") (part "R_P2INCH"))
    )
    (comp (ref "R58")
      (value "470")
      (footprint "eagle-import:R_P2INCH")
      (libsource (lib "eagle-import") (part "R_P2INCH"))
    )
    (comp (ref "R59")
      (value "10k")
      (footprint "eagle-import:R_P2INCH")
      (libsource (lib "eagle-import") (part "R_P2INCH"))
    )
    (comp (ref "R60")
      (value "470")
      (footprint "eagle-import:R_P2INCH")
      (libsource (lib "eagle-import") (part "R_P2INCH"))
    )
    (comp (ref "R61")
      (value "10k")
      (footprint "eagle-import:R_P2INCH")
      (libsource (lib "eagle-import") (part "R_P2INCH"))
    )
    (comp (ref "R62")
      (value "470")
      (footprint "eagle-import:R_P2INCH")
      (libsource (lib "eagle-import") (part "R_P2INCH"))
    )
    (comp (ref "R63")
      (value "10k")
      (footprint "eagle-import:R_P2INCH")
      (libsource (lib "eagle-import") (part "R_P2INCH"))
    )
    (comp (ref "R64")
      (value "470")
      (footprint "eagle-import:R_P2INCH")
      (libsource (lib "eagle-import") (part "R_P2INCH"))
    )
    (comp (ref "R133")
      (value "10k")
      (footprint "eagle-import:R_P2INCH")
      (libsource (lib "eagle-import") (part "R_P2INCH"))
    )
    (comp (ref "R134")
      (value "470")
      (footprint "eagle-import:R_P2INCH")
      (libsource (lib "eagle-import") (part "R_P2INCH"))
    )
    (comp (ref "R135")
      (value "10k")
      (footprint "eagle-import:R_P2INCH")
      (libsource (lib "eagle-import") (part "R_P2INCH"))
    )
    (comp (ref "R136")
      (value "10k")
      (footprint "eagle-import:R_P2INCH")
      (libsource (lib "eagle-import") (part "R_P2INCH"))
    )
    (comp (ref "R178")
      (value "470")
      (footprint "eagle-import:R_P2INCH")
      (libsource (lib "eagle-import") (part "R_P2INCH"))
    )
    (comp (ref "R207")
      (value "10k")
      (footprint "eagle-import:R_P2INCH")
      (libsource (lib "eagle-import") (part "R_P2INCH"))
    )
    (comp (ref "R208")
      (value "10k")
      (footprint "eagle-import:R_P2INCH")
      (libsource (lib "eagle-import") (part "R_P2INCH"))
    )
    (comp (ref "R209")
      (value "10k")
      (footprint "eagle-import:R_P2INCH")
      (libsource (lib "eagle-import") (part "R_P2INCH"))
    )
    (comp (ref "R210")
      (value "10k")
      (footprint "eagle-import:R_P2INCH")
      (libsource (lib "eagle-import") (part "R_P2INCH"))
    )
    (comp (ref "R211")
      (value "10k")
      (footprint "eagle-import:R_P2INCH")
      (libsource (lib "eagle-import") (part "R_P2INCH"))
    )
    (comp (ref "R212")
      (value "10k")
      (footprint "eagle-import:R_P2INCH")
      (libsource (lib "eagle-import") (part "R_P2INCH"))
    )
    (comp (ref "TP2")
      (value "TEST_LOOP")
      (footprint "eagle-import:TEST_LOOP")
      (libsource (lib "eagle-import") (part "TEST_LOOP"))
    )
    (comp (ref "D69")
      (value "L-1334SRT")
      (footprint "eagle-import:LED3MM")
      (libsource (lib "eagle-import") (part "L-1334SRT"))
    )
    (comp (ref "D70")
      (value "L-1334SRT")
      (footprint "eagle-import:LED3MM")
      (libsource (lib "eagle-import") (part "L-1334SRT"))
    )
    (comp (ref "D71")
      (value "L-1334SRT")
      (footprint "eagle-import:LED3MM")
      (libsource (lib "eagle-import") (part "L-1334SRT"))
    )
    (comp (ref "D72")
      (value "L-1334SRT")
      (footprint "eagle-import:LED3MM")
      (libsource (lib "eagle-import") (part "L-1334SRT"))
    )
    (comp (ref "Q141")
      (value "2N7000")
      (footprint "eagle-import:TO92-DGS")
      (libsource (lib "eagle-import") (part "2N7000"))
    )
    (comp (ref "Q142")
      (value "2N7000")
      (footprint "eagle-import:TO92-DGS")
      (libsource (lib "eagle-import") (part "2N7000"))
    )
    (comp (ref "Q143")
      (value "2N7000")
      (footprint "eagle-import:TO92-DGS")
      (libsource (lib "eagle-import") (part "2N7000"))
    )
    (comp (ref "Q146")
      (value "2N7000")
      (footprint "eagle-import:TO92-DGS")
      (libsource (lib "eagle-import") (part "2N7000"))
    )
    (comp (ref "Q147")
      (value "2N7000")
      (footprint "eagle-import:TO92-DGS")
      (libsource (lib "eagle-import") (part "2N7000"))
    )
    (comp (ref "Q148")
      (value "2N7000")
      (footprint "eagle-import:TO92-DGS")
      (libsource (lib "eagle-import") (part "2N7000"))
    )
    (comp (ref "Q151")
      (value "2N7000")
      (footprint "eagle-import:TO92-DGS")
      (libsource (lib "eagle-import") (part "2N7000"))
    )
    (comp (ref "Q152")
      (value "2N7000")
      (footprint "eagle-import:TO92-DGS")
      (libsource (lib "eagle-import") (part "2N7000"))
    )
    (comp (ref "Q153")
      (value "2N7000")
      (footprint "eagle-import:TO92-DGS")
      (libsource (lib "eagle-import") (part "2N7000"))
    )
    (comp (ref "Q156")
      (value "2N7000")
      (footprint "eagle-import:TO92-DGS")
      (libsource (lib "eagle-import") (part "2N7000"))
    )
    (comp (ref "Q157")
      (value "2N7000")
      (footprint "eagle-import:TO92-DGS")
      (libsource (lib "eagle-import") (part "2N7000"))
    )
    (comp (ref "Q158")
      (value "2N7000")
      (footprint "eagle-import:TO92-DGS")
      (libsource (lib "eagle-import") (part "2N7000"))
    )
    (comp (ref "R65")
      (value "10k")
      (footprint "eagle-import:R_P2INCH")
      (libsource (lib "eagle-import") (part "R_P2INCH"))
    )
    (comp (ref "R66")
      (value "10k")
      (footprint "eagle-import:R_P2INCH")
      (libsource (lib "eagle-import") (part "R_P2INCH"))
    )
    (comp (ref "R67")
      (value "10k")
      (footprint "eagle-import:R_P2INCH")
      (libsource (lib "eagle-import") (part "R_P2INCH"))
    )
    (comp (ref "R68")
      (value "10k")
      (footprint "eagle-import:R_P2INCH")
      (libsource (lib "eagle-import") (part "R_P2INCH"))
    )
    (comp (ref "R145")
      (value "10k")
      (footprint "eagle-import:R_P2INCH")
      (libsource (lib "eagle-import") (part "R_P2INCH"))
    )
    (comp (ref "R146")
      (value "470")
      (footprint "eagle-import:R_P2INCH")
      (libsource (lib "eagle-import") (part "R_P2INCH"))
    )
    (comp (ref "R147")
      (value "10k")
      (footprint "eagle-import:R_P2INCH")
      (libsource (lib "eagle-import") (part "R_P2INCH"))
    )
    (comp (ref "R148")
      (value "470")
      (footprint "eagle-import:R_P2INCH")
      (libsource (lib "eagle-import") (part "R_P2INCH"))
    )
    (comp (ref "R149")
      (value "10k")
      (footprint "eagle-import:R_P2INCH")
      (libsource (lib "eagle-import") (part "R_P2INCH"))
    )
    (comp (ref "R150")
      (value "470")
      (footprint "eagle-import:R_P2INCH")
      (libsource (lib "eagle-import") (part "R_P2INCH"))
    )
    (comp (ref "R151")
      (value "10k")
      (footprint "eagle-import:R_P2INCH")
      (libsource (lib "eagle-import") (part "R_P2INCH"))
    )
    (comp (ref "R152")
      (value "470")
      (footprint "eagle-import:R_P2INCH")
      (libsource (lib "eagle-import") (part "R_P2INCH"))
    )
    (comp (ref "D77")
      (value "L-1334SRT")
      (footprint "eagle-import:LED3MM")
      (libsource (lib "eagle-import") (part "L-1334SRT"))
    )
    (comp (ref "D78")
      (value "L-1334SRT")
      (footprint "eagle-import:LED3MM")
      (libsource (lib "eagle-import") (part "L-1334SRT"))
    )
    (comp (ref "D79")
      (value "L-1334SRT")
      (footprint "eagle-import:LED3MM")
      (libsource (lib "eagle-import") (part "L-1334SRT"))
    )
    (comp (ref "D80")
      (value "L-1334SRT")
      (footprint "eagle-import:LED3MM")
      (libsource (lib "eagle-import") (part "L-1334SRT"))
    )
    (comp (ref "Q181")
      (value "2N7000")
      (footprint "eagle-import:TO92-DGS")
      (libsource (lib "eagle-import") (part "2N7000"))
    )
    (comp (ref "Q182")
      (value "2N7000")
      (footprint "eagle-import:TO92-DGS")
      (libsource (lib "eagle-import") (part "2N7000"))
    )
    (comp (ref "Q183")
      (value "2N7000")
      (footprint "eagle-import:TO92-DGS")
      (libsource (lib "eagle-import") (part "2N7000"))
    )
    (comp (ref "Q186")
      (value "2N7000")
      (footprint "eagle-import:TO92-DGS")
      (libsource (lib "eagle-import") (part "2N7000"))
    )
    (comp (ref "Q187")
      (value "2N7000")
      (footprint "eagle-import:TO92-DGS")
      (libsource (lib "eagle-import") (part "2N7000"))
    )
    (comp (ref "Q188")
      (value "2N7000")
      (footprint "eagle-import:TO92-DGS")
      (libsource (lib "eagle-import") (part "2N7000"))
    )
    (comp (ref "Q191")
      (value "2N7000")
      (footprint "eagle-import:TO92-DGS")
      (libsource (lib "eagle-import") (part "2N7000"))
    )
    (comp (ref "Q192")
      (value "2N7000")
      (footprint "eagle-import:TO92-DGS")
      (libsource (lib "eagle-import") (part "2N7000"))
    )
    (comp (ref "Q193")
      (value "2N7000")
      (footprint "eagle-import:TO92-DGS")
      (libsource (lib "eagle-import") (part "2N7000"))
    )
    (comp (ref "Q196")
      (value "2N7000")
      (footprint "eagle-import:TO92-DGS")
      (libsource (lib "eagle-import") (part "2N7000"))
    )
    (comp (ref "Q197")
      (value "2N7000")
      (footprint "eagle-import:TO92-DGS")
      (libsource (lib "eagle-import") (part "2N7000"))
    )
    (comp (ref "Q198")
      (value "2N7000")
      (footprint "eagle-import:TO92-DGS")
      (libsource (lib "eagle-import") (part "2N7000"))
    )
    (comp (ref "R73")
      (value "10k")
      (footprint "eagle-import:R_P2INCH")
      (libsource (lib "eagle-import") (part "R_P2INCH"))
    )
    (comp (ref "R74")
      (value "10k")
      (footprint "eagle-import:R_P2INCH")
      (libsource (lib "eagle-import") (part "R_P2INCH"))
    )
    (comp (ref "R75")
      (value "10k")
      (footprint "eagle-import:R_P2INCH")
      (libsource (lib "eagle-import") (part "R_P2INCH"))
    )
    (comp (ref "R76")
      (value "10k")
      (footprint "eagle-import:R_P2INCH")
      (libsource (lib "eagle-import") (part "R_P2INCH"))
    )
    (comp (ref "R161")
      (value "10k")
      (footprint "eagle-import:R_P2INCH")
      (libsource (lib "eagle-import") (part "R_P2INCH"))
    )
    (comp (ref "R162")
      (value "470")
      (footprint "eagle-import:R_P2INCH")
      (libsource (lib "eagle-import") (part "R_P2INCH"))
    )
    (comp (ref "R163")
      (value "10k")
      (footprint "eagle-import:R_P2INCH")
      (libsource (lib "eagle-import") (part "R_P2INCH"))
    )
    (comp (ref "R164")
      (value "470")
      (footprint "eagle-import:R_P2INCH")
      (libsource (lib "eagle-import") (part "R_P2INCH"))
    )
    (comp (ref "R165")
      (value "10k")
      (footprint "eagle-import:R_P2INCH")
      (libsource (lib "eagle-import") (part "R_P2INCH"))
    )
    (comp (ref "R166")
      (value "470")
      (footprint "eagle-import:R_P2INCH")
      (libsource (lib "eagle-import") (part "R_P2INCH"))
    )
    (comp (ref "R167")
      (value "10k")
      (footprint "eagle-import:R_P2INCH")
      (libsource (lib "eagle-import") (part "R_P2INCH"))
    )
    (comp (ref "R168")
      (value "470")
      (footprint "eagle-import:R_P2INCH")
      (libsource (lib "eagle-import") (part "R_P2INCH"))
    )
    (comp (ref "C1")
      (value "100n")
      (footprint "eagle-import:CAP_P2INCH")
      (libsource (lib "eagle-import") (part "C_P2INCH"))
    )
    (comp (ref "C2")
      (value "100n")
      (footprint "eagle-import:CAP_P2INCH")
      (libsource (lib "eagle-import") (part "C_P2INCH"))
    )
    (comp (ref "C3")
      (value "100n")
      (footprint "eagle-import:CAP_P2INCH")
      (libsource (lib "eagle-import") (part "C_P2INCH"))
    )
    (comp (ref "C4")
      (value "100n")
      (footprint "eagle-import:CAP_P2INCH")
      (libsource (lib "eagle-import") (part "C_P2INCH"))
    )
    (comp (ref "C5")
      (value "100n")
      (footprint "eagle-import:CAP_P2INCH")
      (libsource (lib "eagle-import") (part "C_P2INCH"))
    )
    (comp (ref "C6")
      (value "100n")
      (footprint "eagle-import:CAP_P2INCH")
      (libsource (lib "eagle-import") (part "C_P2INCH"))
    )
    (comp (ref "C7")
      (value "100u")
      (footprint "eagle-import:POLARISED_CAP_2P5_6P3MM")
      (libsource (lib "eagle-import") (part "POLARISED_CAP_2P5_6P3MM"))
    )
    (comp (ref "C8")
      (value "100n")
      (footprint "eagle-import:CAP_P2INCH")
      (libsource (lib "eagle-import") (part "C_P2INCH"))
    )
    (comp (ref "H1")
      (value "3M_MOUNT_HOLE")
      (footprint "eagle-import:3M_HOLE")
      (libsource (lib "eagle-import") (part "3M_MOUNT_HOLE"))
    )
    (comp (ref "H2")
      (value "3M_MOUNT_HOLE")
      (footprint "eagle-import:3M_HOLE")
      (libsource (lib "eagle-import") (part "3M_MOUNT_HOLE"))
    )
    (comp (ref "H3")
      (value "3M_MOUNT_HOLE")
      (footprint "eagle-import:3M_HOLE")
      (libsource (lib "eagle-import") (part "3M_MOUNT_HOLE"))
    )
    (comp (ref "H4")
      (value "3M_MOUNT_HOLE")
      (footprint "eagle-import:3M_HOLE")
      (libsource (lib "eagle-import") (part "3M_MOUNT_HOLE"))
    )
    (comp (ref "TP5")
      (value "TEST_LOOP")
      (footprint "eagle-import:TEST_LOOP")
      (libsource (lib "eagle-import") (part "TEST_LOOP"))
    )
    (comp (ref "TP6")
      (value "TEST_LOOP")
      (footprint "eagle-import:TEST_LOOP")
      (libsource (lib "eagle-import") (part "TEST_LOOP"))
    )
    (comp (ref "D1")
      (value "L-1334SRT")
      (footprint "eagle-import:LED3MM")
      (libsource (lib "eagle-import") (part "L-1334SRT"))
    )
    (comp (ref "D2")
      (value "L-1334SRT")
      (footprint "eagle-import:LED3MM")
      (libsource (lib "eagle-import") (part "L-1334SRT"))
    )
    (comp (ref "D3")
      (value "L-1334SRT")
      (footprint "eagle-import:LED3MM")
      (libsource (lib "eagle-import") (part "L-1334SRT"))
    )
    (comp (ref "D4")
      (value "L-1334SRT")
      (footprint "eagle-import:LED3MM")
      (libsource (lib "eagle-import") (part "L-1334SRT"))
    )
    (comp (ref "D5")
      (value "L-1334SRT")
      (footprint "eagle-import:LED3MM")
      (libsource (lib "eagle-import") (part "L-1334SRT"))
    )
    (comp (ref "D6")
      (value "L-1334SRT")
      (footprint "eagle-import:LED3MM")
      (libsource (lib "eagle-import") (part "L-1334SRT"))
    )
    (comp (ref "D7")
      (value "L-1334SRT")
      (footprint "eagle-import:LED3MM")
      (libsource (lib "eagle-import") (part "L-1334SRT"))
    )
    (comp (ref "D8")
      (value "L-1334SRT")
      (footprint "eagle-import:LED3MM")
      (libsource (lib "eagle-import") (part "L-1334SRT"))
    )
    (comp (ref "D9")
      (value "L-1334SRT")
      (footprint "eagle-import:LED3MM")
      (libsource (lib "eagle-import") (part "L-1334SRT"))
    )
    (comp (ref "D10")
      (value "L-1334SRT")
      (footprint "eagle-import:LED3MM")
      (libsource (lib "eagle-import") (part "L-1334SRT"))
    )
    (comp (ref "Q1")
      (value "2N7000")
      (footprint "eagle-import:TO92-DGS")
      (libsource (lib "eagle-import") (part "2N7000"))
    )
    (comp (ref "Q2")
      (value "2N7000")
      (footprint "eagle-import:TO92-DGS")
      (libsource (lib "eagle-import") (part "2N7000"))
    )
    (comp (ref "Q3")
      (value "2N7000")
      (footprint "eagle-import:TO92-DGS")
      (libsource (lib "eagle-import") (part "2N7000"))
    )
    (comp (ref "Q4")
      (value "2N7000")
      (footprint "eagle-import:TO92-DGS")
      (libsource (lib "eagle-import") (part "2N7000"))
    )
    (comp (ref "Q5")
      (value "2N7000")
      (footprint "eagle-import:TO92-DGS")
      (libsource (lib "eagle-import") (part "2N7000"))
    )
    (comp (ref "Q6")
      (value "2N7000")
      (footprint "eagle-import:TO92-DGS")
      (libsource (lib "eagle-import") (part "2N7000"))
    )
    (comp (ref "Q7")
      (value "2N7000")
      (footprint "eagle-import:TO92-DGS")
      (libsource (lib "eagle-import") (part "2N7000"))
    )
    (comp (ref "Q8")
      (value "2N7000")
      (footprint "eagle-import:TO92-DGS")
      (libsource (lib "eagle-import") (part "2N7000"))
    )
    (comp (ref "Q9")
      (value "2N7000")
      (footprint "eagle-import:TO92-DGS")
      (libsource (lib "eagle-import") (part "2N7000"))
    )
    (comp (ref "Q10")
      (value "2N7000")
      (footprint "eagle-import:TO92-DGS")
      (libsource (lib "eagle-import") (part "2N7000"))
    )
    (comp (ref "Q11")
      (value "2N7000")
      (footprint "eagle-import:TO92-DGS")
      (libsource (lib "eagle-import") (part "2N7000"))
    )
    (comp (ref "Q12")
      (value "2N7000")
      (footprint "eagle-import:TO92-DGS")
      (libsource (lib "eagle-import") (part "2N7000"))
    )
    (comp (ref "Q13")
      (value "2N7000")
      (footprint "eagle-import:TO92-DGS")
      (libsource (lib "eagle-import") (part "2N7000"))
    )
    (comp (ref "Q14")
      (value "2N7000")
      (footprint "eagle-import:TO92-DGS")
      (libsource (lib "eagle-import") (part "2N7000"))
    )
    (comp (ref "Q15")
      (value "2N7000")
      (footprint "eagle-import:TO92-DGS")
      (libsource (lib "eagle-import") (part "2N7000"))
    )
    (comp (ref "Q16")
      (value "2N7000")
      (footprint "eagle-import:TO92-DGS")
      (libsource (lib "eagle-import") (part "2N7000"))
    )
    (comp (ref "Q17")
      (value "2N7000")
      (footprint "eagle-import:TO92-DGS")
      (libsource (lib "eagle-import") (part "2N7000"))
    )
    (comp (ref "Q18")
      (value "2N7000")
      (footprint "eagle-import:TO92-DGS")
      (libsource (lib "eagle-import") (part "2N7000"))
    )
    (comp (ref "Q19")
      (value "2N7000")
      (footprint "eagle-import:TO92-DGS")
      (libsource (lib "eagle-import") (part "2N7000"))
    )
    (comp (ref "Q20")
      (value "2N7000")
      (footprint "eagle-import:TO92-DGS")
      (libsource (lib "eagle-import") (part "2N7000"))
    )
    (comp (ref "R1")
      (value "10k")
      (footprint "eagle-import:R_P2INCH")
      (libsource (lib "eagle-import") (part "R_P2INCH"))
    )
    (comp (ref "R2")
      (value "470")
      (footprint "eagle-import:R_P2INCH")
      (libsource (lib "eagle-import") (part "R_P2INCH"))
    )
    (comp (ref "R3")
      (value "10k")
      (footprint "eagle-import:R_P2INCH")
      (libsource (lib "eagle-import") (part "R_P2INCH"))
    )
    (comp (ref "R4")
      (value "470")
      (footprint "eagle-import:R_P2INCH")
      (libsource (lib "eagle-import") (part "R_P2INCH"))
    )
    (comp (ref "R5")
      (value "10k")
      (footprint "eagle-import:R_P2INCH")
      (libsource (lib "eagle-import") (part "R_P2INCH"))
    )
    (comp (ref "R6")
      (value "470")
      (footprint "eagle-import:R_P2INCH")
      (libsource (lib "eagle-import") (part "R_P2INCH"))
    )
    (comp (ref "R7")
      (value "10k")
      (footprint "eagle-import:R_P2INCH")
      (libsource (lib "eagle-import") (part "R_P2INCH"))
    )
    (comp (ref "R8")
      (value "470")
      (footprint "eagle-import:R_P2INCH")
      (libsource (lib "eagle-import") (part "R_P2INCH"))
    )
    (comp (ref "R9")
      (value "10k")
      (footprint "eagle-import:R_P2INCH")
      (libsource (lib "eagle-import") (part "R_P2INCH"))
    )
    (comp (ref "R10")
      (value "470")
      (footprint "eagle-import:R_P2INCH")
      (libsource (lib "eagle-import") (part "R_P2INCH"))
    )
    (comp (ref "R11")
      (value "10k")
      (footprint "eagle-import:R_P2INCH")
      (libsource (lib "eagle-import") (part "R_P2INCH"))
    )
    (comp (ref "R12")
      (value "470")
      (footprint "eagle-import:R_P2INCH")
      (libsource (lib "eagle-import") (part "R_P2INCH"))
    )
    (comp (ref "R13")
      (value "10k")
      (footprint "eagle-import:R_P2INCH")
      (libsource (lib "eagle-import") (part "R_P2INCH"))
    )
    (comp (ref "R14")
      (value "470")
      (footprint "eagle-import:R_P2INCH")
      (libsource (lib "eagle-import") (part "R_P2INCH"))
    )
    (comp (ref "R15")
      (value "10k")
      (footprint "eagle-import:R_P2INCH")
      (libsource (lib "eagle-import") (part "R_P2INCH"))
    )
    (comp (ref "R16")
      (value "470")
      (footprint "eagle-import:R_P2INCH")
      (libsource (lib "eagle-import") (part "R_P2INCH"))
    )
    (comp (ref "R17")
      (value "10k")
      (footprint "eagle-import:R_P2INCH")
      (libsource (lib "eagle-import") (part "R_P2INCH"))
    )
    (comp (ref "R18")
      (value "470")
      (footprint "eagle-import:R_P2INCH")
      (libsource (lib "eagle-import") (part "R_P2INCH"))
    )
    (comp (ref "R19")
      (value "10k")
      (footprint "eagle-import:R_P2INCH")
      (libsource (lib "eagle-import") (part "R_P2INCH"))
    )
    (comp (ref "R20")
      (value "470")
      (footprint "eagle-import:R_P2INCH")
      (libsource (lib "eagle-import") (part "R_P2INCH"))
    )
    (comp (ref "R181")
      (value "10k")
      (footprint "eagle-import:R_P2INCH")
      (libsource (lib "eagle-import") (part "R_P2INCH"))
    )
    (comp (ref "R182")
      (value "10k")
      (footprint "eagle-import:R_P2INCH")
      (libsource (lib "eagle-import") (part "R_P2INCH"))
    )
    (comp (ref "R183")
      (value "10k")
      (footprint "eagle-import:R_P2INCH")
      (libsource (lib "eagle-import") (part "R_P2INCH"))
    )
    (comp (ref "R184")
      (value "10k")
      (footprint "eagle-import:R_P2INCH")
      (libsource (lib "eagle-import") (part "R_P2INCH"))
    )
    (comp (ref "R185")
      (value "10k")
      (footprint "eagle-import:R_P2INCH")
      (libsource (lib "eagle-import") (part "R_P2INCH"))
    )
    (comp (ref "R186")
      (value "10k")
      (footprint "eagle-import:R_P2INCH")
      (libsource (lib "eagle-import") (part "R_P2INCH"))
    )
    (comp (ref "R187")
      (value "10k")
      (footprint "eagle-import:R_P2INCH")
      (libsource (lib "eagle-import") (part "R_P2INCH"))
    )
    (comp (ref "R188")
      (value "10k")
      (footprint "eagle-import:R_P2INCH")
      (libsource (lib "eagle-import") (part "R_P2INCH"))
    )
    (comp (ref "R189")
      (value "10k")
      (footprint "eagle-import:R_P2INCH")
      (libsource (lib "eagle-import") (part "R_P2INCH"))
    )
    (comp (ref "R190")
      (value "10k")
      (footprint "eagle-import:R_P2INCH")
      (libsource (lib "eagle-import") (part "R_P2INCH"))
    )
    (comp (ref "D73")
      (value "L-1334SRT")
      (footprint "eagle-import:LED3MM")
      (libsource (lib "eagle-import") (part "L-1334SRT"))
    )
    (comp (ref "D74")
      (value "L-1334SRT")
      (footprint "eagle-import:LED3MM")
      (libsource (lib "eagle-import") (part "L-1334SRT"))
    )
    (comp (ref "D75")
      (value "L-1334SRT")
      (footprint "eagle-import:LED3MM")
      (libsource (lib "eagle-import") (part "L-1334SRT"))
    )
    (comp (ref "D76")
      (value "L-1334SRT")
      (footprint "eagle-import:LED3MM")
      (libsource (lib "eagle-import") (part "L-1334SRT"))
    )
    (comp (ref "Q161")
      (value "2N7000")
      (footprint "eagle-import:TO92-DGS")
      (libsource (lib "eagle-import") (part "2N7000"))
    )
    (comp (ref "Q162")
      (value "2N7000")
      (footprint "eagle-import:TO92-DGS")
      (libsource (lib "eagle-import") (part "2N7000"))
    )
    (comp (ref "Q163")
      (value "2N7000")
      (footprint "eagle-import:TO92-DGS")
      (libsource (lib "eagle-import") (part "2N7000"))
    )
    (comp (ref "Q166")
      (value "2N7000")
      (footprint "eagle-import:TO92-DGS")
      (libsource (lib "eagle-import") (part "2N7000"))
    )
    (comp (ref "Q167")
      (value "2N7000")
      (footprint "eagle-import:TO92-DGS")
      (libsource (lib "eagle-import") (part "2N7000"))
    )
    (comp (ref "Q168")
      (value "2N7000")
      (footprint "eagle-import:TO92-DGS")
      (libsource (lib "eagle-import") (part "2N7000"))
    )
    (comp (ref "Q171")
      (value "2N7000")
      (footprint "eagle-import:TO92-DGS")
      (libsource (lib "eagle-import") (part "2N7000"))
    )
    (comp (ref "Q172")
      (value "2N7000")
      (footprint "eagle-import:TO92-DGS")
      (libsource (lib "eagle-import") (part "2N7000"))
    )
    (comp (ref "Q173")
      (value "2N7000")
      (footprint "eagle-import:TO92-DGS")
      (libsource (lib "eagle-import") (part "2N7000"))
    )
    (comp (ref "Q176")
      (value "2N7000")
      (footprint "eagle-import:TO92-DGS")
      (libsource (lib "eagle-import") (part "2N7000"))
    )
    (comp (ref "Q177")
      (value "2N7000")
      (footprint "eagle-import:TO92-DGS")
      (libsource (lib "eagle-import") (part "2N7000"))
    )
    (comp (ref "Q178")
      (value "2N7000")
      (footprint "eagle-import:TO92-DGS")
      (libsource (lib "eagle-import") (part "2N7000"))
    )
    (comp (ref "R69")
      (value "10k")
      (footprint "eagle-import:R_P2INCH")
      (libsource (lib "eagle-import") (part "R_P2INCH"))
    )
    (comp (ref "R70")
      (value "10k")
      (footprint "eagle-import:R_P2INCH")
      (libsource (lib "eagle-import") (part "R_P2INCH"))
    )
    (comp (ref "R71")
      (value "10k")
      (footprint "eagle-import:R_P2INCH")
      (libsource (lib "eagle-import") (part "R_P2INCH"))
    )
    (comp (ref "R72")
      (value "10k")
      (footprint "eagle-import:R_P2INCH")
      (libsource (lib "eagle-import") (part "R_P2INCH"))
    )
    (comp (ref "R153")
      (value "10k")
      (footprint "eagle-import:R_P2INCH")
      (libsource (lib "eagle-import") (part "R_P2INCH"))
    )
    (comp (ref "R154")
      (value "470")
      (footprint "eagle-import:R_P2INCH")
      (libsource (lib "eagle-import") (part "R_P2INCH"))
    )
    (comp (ref "R155")
      (value "10k")
      (footprint "eagle-import:R_P2INCH")
      (libsource (lib "eagle-import") (part "R_P2INCH"))
    )
    (comp (ref "R156")
      (value "470")
      (footprint "eagle-import:R_P2INCH")
      (libsource (lib "eagle-import") (part "R_P2INCH"))
    )
    (comp (ref "R157")
      (value "10k")
      (footprint "eagle-import:R_P2INCH")
      (libsource (lib "eagle-import") (part "R_P2INCH"))
    )
    (comp (ref "R158")
      (value "470")
      (footprint "eagle-import:R_P2INCH")
      (libsource (lib "eagle-import") (part "R_P2INCH"))
    )
    (comp (ref "R159")
      (value "10k")
      (footprint "eagle-import:R_P2INCH")
      (libsource (lib "eagle-import") (part "R_P2INCH"))
    )
    (comp (ref "R160")
      (value "470")
      (footprint "eagle-import:R_P2INCH")
      (libsource (lib "eagle-import") (part "R_P2INCH"))
    )
    (comp (ref "D81")
      (value "L-1334SRT")
      (footprint "eagle-import:LED3MM")
      (libsource (lib "eagle-import") (part "L-1334SRT"))
    )
    (comp (ref "D82")
      (value "L-1334SRT")
      (footprint "eagle-import:LED3MM")
      (libsource (lib "eagle-import") (part "L-1334SRT"))
    )
    (comp (ref "D83")
      (value "L-1334SRT")
      (footprint "eagle-import:LED3MM")
      (libsource (lib "eagle-import") (part "L-1334SRT"))
    )
    (comp (ref "D84")
      (value "L-1334SRT")
      (footprint "eagle-import:LED3MM")
      (libsource (lib "eagle-import") (part "L-1334SRT"))
    )
    (comp (ref "Q201")
      (value "2N7000")
      (footprint "eagle-import:TO92-DGS")
      (libsource (lib "eagle-import") (part "2N7000"))
    )
    (comp (ref "Q202")
      (value "2N7000")
      (footprint "eagle-import:TO92-DGS")
      (libsource (lib "eagle-import") (part "2N7000"))
    )
    (comp (ref "Q203")
      (value "2N7000")
      (footprint "eagle-import:TO92-DGS")
      (libsource (lib "eagle-import") (part "2N7000"))
    )
    (comp (ref "Q206")
      (value "2N7000")
      (footprint "eagle-import:TO92-DGS")
      (libsource (lib "eagle-import") (part "2N7000"))
    )
    (comp (ref "Q207")
      (value "2N7000")
      (footprint "eagle-import:TO92-DGS")
      (libsource (lib "eagle-import") (part "2N7000"))
    )
    (comp (ref "Q208")
      (value "2N7000")
      (footprint "eagle-import:TO92-DGS")
      (libsource (lib "eagle-import") (part "2N7000"))
    )
    (comp (ref "Q211")
      (value "2N7000")
      (footprint "eagle-import:TO92-DGS")
      (libsource (lib "eagle-import") (part "2N7000"))
    )
    (comp (ref "Q212")
      (value "2N7000")
      (footprint "eagle-import:TO92-DGS")
      (libsource (lib "eagle-import") (part "2N7000"))
    )
    (comp (ref "Q213")
      (value "2N7000")
      (footprint "eagle-import:TO92-DGS")
      (libsource (lib "eagle-import") (part "2N7000"))
    )
    (comp (ref "Q216")
      (value "2N7000")
      (footprint "eagle-import:TO92-DGS")
      (libsource (lib "eagle-import") (part "2N7000"))
    )
    (comp (ref "Q217")
      (value "2N7000")
      (footprint "eagle-import:TO92-DGS")
      (libsource (lib "eagle-import") (part "2N7000"))
    )
    (comp (ref "Q218")
      (value "2N7000")
      (footprint "eagle-import:TO92-DGS")
      (libsource (lib "eagle-import") (part "2N7000"))
    )
    (comp (ref "R77")
      (value "10k")
      (footprint "eagle-import:R_P2INCH")
      (libsource (lib "eagle-import") (part "R_P2INCH"))
    )
    (comp (ref "R78")
      (value "10k")
      (footprint "eagle-import:R_P2INCH")
      (libsource (lib "eagle-import") (part "R_P2INCH"))
    )
    (comp (ref "R79")
      (value "10k")
      (footprint "eagle-import:R_P2INCH")
      (libsource (lib "eagle-import") (part "R_P2INCH"))
    )
    (comp (ref "R80")
      (value "10k")
      (footprint "eagle-import:R_P2INCH")
      (libsource (lib "eagle-import") (part "R_P2INCH"))
    )
    (comp (ref "R169")
      (value "10k")
      (footprint "eagle-import:R_P2INCH")
      (libsource (lib "eagle-import") (part "R_P2INCH"))
    )
    (comp (ref "R170")
      (value "470")
      (footprint "eagle-import:R_P2INCH")
      (libsource (lib "eagle-import") (part "R_P2INCH"))
    )
    (comp (ref "R171")
      (value "10k")
      (footprint "eagle-import:R_P2INCH")
      (libsource (lib "eagle-import") (part "R_P2INCH"))
    )
    (comp (ref "R172")
      (value "470")
      (footprint "eagle-import:R_P2INCH")
      (libsource (lib "eagle-import") (part "R_P2INCH"))
    )
    (comp (ref "R173")
      (value "10k")
      (footprint "eagle-import:R_P2INCH")
      (libsource (lib "eagle-import") (part "R_P2INCH"))
    )
    (comp (ref "R174")
      (value "470")
      (footprint "eagle-import:R_P2INCH")
      (libsource (lib "eagle-import") (part "R_P2INCH"))
    )
    (comp (ref "R175")
      (value "10k")
      (footprint "eagle-import:R_P2INCH")
      (libsource (lib "eagle-import") (part "R_P2INCH"))
    )
    (comp (ref "R176")
      (value "470")
      (footprint "eagle-import:R_P2INCH")
      (libsource (lib "eagle-import") (part "R_P2INCH"))
    )
    (comp (ref "D17")
      (value "L-1334SRT")
      (footprint "eagle-import:LED3MM")
      (libsource (lib "eagle-import") (part "L-1334SRT"))
    )
    (comp (ref "D18")
      (value "L-1334SRT")
      (footprint "eagle-import:LED3MM")
      (libsource (lib "eagle-import") (part "L-1334SRT"))
    )
    (comp (ref "D19")
      (value "L-1334SRT")
      (footprint "eagle-import:LED3MM")
      (libsource (lib "eagle-import") (part "L-1334SRT"))
    )
    (comp (ref "D20")
      (value "L-1334SRT")
      (footprint "eagle-import:LED3MM")
      (libsource (lib "eagle-import") (part "L-1334SRT"))
    )
    (comp (ref "D21")
      (value "L-1334SRT")
      (footprint "eagle-import:LED3MM")
      (libsource (lib "eagle-import") (part "L-1334SRT"))
    )
    (comp (ref "D22")
      (value "L-1334SRT")
      (footprint "eagle-import:LED3MM")
      (libsource (lib "eagle-import") (part "L-1334SRT"))
    )
    (comp (ref "D23")
      (value "L-1334SRT")
      (footprint "eagle-import:LED3MM")
      (libsource (lib "eagle-import") (part "L-1334SRT"))
    )
    (comp (ref "D24")
      (value "L-1334SRT")
      (footprint "eagle-import:LED3MM")
      (libsource (lib "eagle-import") (part "L-1334SRT"))
    )
    (comp (ref "D25")
      (value "L-1334SRT")
      (footprint "eagle-import:LED3MM")
      (libsource (lib "eagle-import") (part "L-1334SRT"))
    )
    (comp (ref "D26")
      (value "L-1334SRT")
      (footprint "eagle-import:LED3MM")
      (libsource (lib "eagle-import") (part "L-1334SRT"))
    )
    (comp (ref "Q33")
      (value "2N7000")
      (footprint "eagle-import:TO92-DGS")
      (libsource (lib "eagle-import") (part "2N7000"))
    )
    (comp (ref "Q34")
      (value "2N7000")
      (footprint "eagle-import:TO92-DGS")
      (libsource (lib "eagle-import") (part "2N7000"))
    )
    (comp (ref "Q35")
      (value "2N7000")
      (footprint "eagle-import:TO92-DGS")
      (libsource (lib "eagle-import") (part "2N7000"))
    )
    (comp (ref "Q36")
      (value "2N7000")
      (footprint "eagle-import:TO92-DGS")
      (libsource (lib "eagle-import") (part "2N7000"))
    )
    (comp (ref "Q37")
      (value "2N7000")
      (footprint "eagle-import:TO92-DGS")
      (libsource (lib "eagle-import") (part "2N7000"))
    )
    (comp (ref "Q38")
      (value "2N7000")
      (footprint "eagle-import:TO92-DGS")
      (libsource (lib "eagle-import") (part "2N7000"))
    )
    (comp (ref "Q39")
      (value "2N7000")
      (footprint "eagle-import:TO92-DGS")
      (libsource (lib "eagle-import") (part "2N7000"))
    )
    (comp (ref "Q40")
      (value "2N7000")
      (footprint "eagle-import:TO92-DGS")
      (libsource (lib "eagle-import") (part "2N7000"))
    )
    (comp (ref "Q41")
      (value "2N7000")
      (footprint "eagle-import:TO92-DGS")
      (libsource (lib "eagle-import") (part "2N7000"))
    )
    (comp (ref "Q42")
      (value "2N7000")
      (footprint "eagle-import:TO92-DGS")
      (libsource (lib "eagle-import") (part "2N7000"))
    )
    (comp (ref "Q43")
      (value "2N7000")
      (footprint "eagle-import:TO92-DGS")
      (libsource (lib "eagle-import") (part "2N7000"))
    )
    (comp (ref "Q44")
      (value "2N7000")
      (footprint "eagle-import:TO92-DGS")
      (libsource (lib "eagle-import") (part "2N7000"))
    )
    (comp (ref "Q45")
      (value "2N7000")
      (footprint "eagle-import:TO92-DGS")
      (libsource (lib "eagle-import") (part "2N7000"))
    )
    (comp (ref "Q46")
      (value "2N7000")
      (footprint "eagle-import:TO92-DGS")
      (libsource (lib "eagle-import") (part "2N7000"))
    )
    (comp (ref "Q47")
      (value "2N7000")
      (footprint "eagle-import:TO92-DGS")
      (libsource (lib "eagle-import") (part "2N7000"))
    )
    (comp (ref "Q48")
      (value "2N7000")
      (footprint "eagle-import:TO92-DGS")
      (libsource (lib "eagle-import") (part "2N7000"))
    )
    (comp (ref "Q49")
      (value "2N7000")
      (footprint "eagle-import:TO92-DGS")
      (libsource (lib "eagle-import") (part "2N7000"))
    )
    (comp (ref "Q50")
      (value "2N7000")
      (footprint "eagle-import:TO92-DGS")
      (libsource (lib "eagle-import") (part "2N7000"))
    )
    (comp (ref "Q51")
      (value "2N7000")
      (footprint "eagle-import:TO92-DGS")
      (libsource (lib "eagle-import") (part "2N7000"))
    )
    (comp (ref "Q52")
      (value "2N7000")
      (footprint "eagle-import:TO92-DGS")
      (libsource (lib "eagle-import") (part "2N7000"))
    )
    (comp (ref "R33")
      (value "10k")
      (footprint "eagle-import:R_P2INCH")
      (libsource (lib "eagle-import") (part "R_P2INCH"))
    )
    (comp (ref "R34")
      (value "470")
      (footprint "eagle-import:R_P2INCH")
      (libsource (lib "eagle-import") (part "R_P2INCH"))
    )
    (comp (ref "R35")
      (value "10k")
      (footprint "eagle-import:R_P2INCH")
      (libsource (lib "eagle-import") (part "R_P2INCH"))
    )
    (comp (ref "R36")
      (value "470")
      (footprint "eagle-import:R_P2INCH")
      (libsource (lib "eagle-import") (part "R_P2INCH"))
    )
    (comp (ref "R37")
      (value "10k")
      (footprint "eagle-import:R_P2INCH")
      (libsource (lib "eagle-import") (part "R_P2INCH"))
    )
    (comp (ref "R38")
      (value "470")
      (footprint "eagle-import:R_P2INCH")
      (libsource (lib "eagle-import") (part "R_P2INCH"))
    )
    (comp (ref "R39")
      (value "10k")
      (footprint "eagle-import:R_P2INCH")
      (libsource (lib "eagle-import") (part "R_P2INCH"))
    )
    (comp (ref "R40")
      (value "470")
      (footprint "eagle-import:R_P2INCH")
      (libsource (lib "eagle-import") (part "R_P2INCH"))
    )
    (comp (ref "R41")
      (value "10k")
      (footprint "eagle-import:R_P2INCH")
      (libsource (lib "eagle-import") (part "R_P2INCH"))
    )
    (comp (ref "R42")
      (value "470")
      (footprint "eagle-import:R_P2INCH")
      (libsource (lib "eagle-import") (part "R_P2INCH"))
    )
    (comp (ref "R43")
      (value "10k")
      (footprint "eagle-import:R_P2INCH")
      (libsource (lib "eagle-import") (part "R_P2INCH"))
    )
    (comp (ref "R44")
      (value "470")
      (footprint "eagle-import:R_P2INCH")
      (libsource (lib "eagle-import") (part "R_P2INCH"))
    )
    (comp (ref "R45")
      (value "10k")
      (footprint "eagle-import:R_P2INCH")
      (libsource (lib "eagle-import") (part "R_P2INCH"))
    )
    (comp (ref "R46")
      (value "470")
      (footprint "eagle-import:R_P2INCH")
      (libsource (lib "eagle-import") (part "R_P2INCH"))
    )
    (comp (ref "R47")
      (value "10k")
      (footprint "eagle-import:R_P2INCH")
      (libsource (lib "eagle-import") (part "R_P2INCH"))
    )
    (comp (ref "R48")
      (value "470")
      (footprint "eagle-import:R_P2INCH")
      (libsource (lib "eagle-import") (part "R_P2INCH"))
    )
    (comp (ref "R49")
      (value "10k")
      (footprint "eagle-import:R_P2INCH")
      (libsource (lib "eagle-import") (part "R_P2INCH"))
    )
    (comp (ref "R50")
      (value "470")
      (footprint "eagle-import:R_P2INCH")
      (libsource (lib "eagle-import") (part "R_P2INCH"))
    )
    (comp (ref "R51")
      (value "10k")
      (footprint "eagle-import:R_P2INCH")
      (libsource (lib "eagle-import") (part "R_P2INCH"))
    )
    (comp (ref "R52")
      (value "470")
      (footprint "eagle-import:R_P2INCH")
      (libsource (lib "eagle-import") (part "R_P2INCH"))
    )
    (comp (ref "R197")
      (value "10k")
      (footprint "eagle-import:R_P2INCH")
      (libsource (lib "eagle-import") (part "R_P2INCH"))
    )
    (comp (ref "R198")
      (value "10k")
      (footprint "eagle-import:R_P2INCH")
      (libsource (lib "eagle-import") (part "R_P2INCH"))
    )
    (comp (ref "R199")
      (value "10k")
      (footprint "eagle-import:R_P2INCH")
      (libsource (lib "eagle-import") (part "R_P2INCH"))
    )
    (comp (ref "R200")
      (value "10k")
      (footprint "eagle-import:R_P2INCH")
      (libsource (lib "eagle-import") (part "R_P2INCH"))
    )
    (comp (ref "R201")
      (value "10k")
      (footprint "eagle-import:R_P2INCH")
      (libsource (lib "eagle-import") (part "R_P2INCH"))
    )
    (comp (ref "R202")
      (value "10k")
      (footprint "eagle-import:R_P2INCH")
      (libsource (lib "eagle-import") (part "R_P2INCH"))
    )
    (comp (ref "R203")
      (value "10k")
      (footprint "eagle-import:R_P2INCH")
      (libsource (lib "eagle-import") (part "R_P2INCH"))
    )
    (comp (ref "R204")
      (value "10k")
      (footprint "eagle-import:R_P2INCH")
      (libsource (lib "eagle-import") (part "R_P2INCH"))
    )
    (comp (ref "R205")
      (value "10k")
      (footprint "eagle-import:R_P2INCH")
      (libsource (lib "eagle-import") (part "R_P2INCH"))
    )
    (comp (ref "R206")
      (value "10k")
      (footprint "eagle-import:R_P2INCH")
      (libsource (lib "eagle-import") (part "R_P2INCH"))
    )
    (comp (ref "D11")
      (value "L-1334SRT")
      (footprint "eagle-import:LED3MM")
      (libsource (lib "eagle-import") (part "L-1334SRT"))
    )
    (comp (ref "D12")
      (value "L-1334SRT")
      (footprint "eagle-import:LED3MM")
      (libsource (lib "eagle-import") (part "L-1334SRT"))
    )
    (comp (ref "D13")
      (value "L-1334SRT")
      (footprint "eagle-import:LED3MM")
      (libsource (lib "eagle-import") (part "L-1334SRT"))
    )
    (comp (ref "D14")
      (value "L-1334SRT")
      (footprint "eagle-import:LED3MM")
      (libsource (lib "eagle-import") (part "L-1334SRT"))
    )
    (comp (ref "D15")
      (value "L-1334SRT")
      (footprint "eagle-import:LED3MM")
      (libsource (lib "eagle-import") (part "L-1334SRT"))
    )
    (comp (ref "D16")
      (value "L-1334SRT")
      (footprint "eagle-import:LED3MM")
      (libsource (lib "eagle-import") (part "L-1334SRT"))
    )
    (comp (ref "D65")
      (value "L-1334SRT")
      (footprint "eagle-import:LED3MM")
      (libsource (lib "eagle-import") (part "L-1334SRT"))
    )
    (comp (ref "D85")
      (value "L-1334SRT")
      (footprint "eagle-import:LED3MM")
      (libsource (lib "eagle-import") (part "L-1334SRT"))
    )
    (comp (ref "J1")
      (value "20_HDR_LOCKING_RA")
      (footprint "eagle-import:20_HDR_LOCKING_RA")
      (libsource (lib "eagle-import") (part "20_HDR_LOCKING_RA"))
    )
    (comp (ref "Q21")
      (value "2N7000")
      (footprint "eagle-import:TO92-DGS")
      (libsource (lib "eagle-import") (part "2N7000"))
    )
    (comp (ref "Q22")
      (value "2N7000")
      (footprint "eagle-import:TO92-DGS")
      (libsource (lib "eagle-import") (part "2N7000"))
    )
    (comp (ref "Q23")
      (value "2N7000")
      (footprint "eagle-import:TO92-DGS")
      (libsource (lib "eagle-import") (part "2N7000"))
    )
    (comp (ref "Q24")
      (value "2N7000")
      (footprint "eagle-import:TO92-DGS")
      (libsource (lib "eagle-import") (part "2N7000"))
    )
    (comp (ref "Q25")
      (value "2N7000")
      (footprint "eagle-import:TO92-DGS")
      (libsource (lib "eagle-import") (part "2N7000"))
    )
    (comp (ref "Q26")
      (value "2N7000")
      (footprint "eagle-import:TO92-DGS")
      (libsource (lib "eagle-import") (part "2N7000"))
    )
    (comp (ref "Q27")
      (value "2N7000")
      (footprint "eagle-import:TO92-DGS")
      (libsource (lib "eagle-import") (part "2N7000"))
    )
    (comp (ref "Q28")
      (value "2N7000")
      (footprint "eagle-import:TO92-DGS")
      (libsource (lib "eagle-import") (part "2N7000"))
    )
    (comp (ref "Q29")
      (value "2N7000")
      (footprint "eagle-import:TO92-DGS")
      (libsource (lib "eagle-import") (part "2N7000"))
    )
    (comp (ref "Q30")
      (value "2N7000")
      (footprint "eagle-import:TO92-DGS")
      (libsource (lib "eagle-import") (part "2N7000"))
    )
    (comp (ref "Q31")
      (value "2N7000")
      (footprint "eagle-import:TO92-DGS")
      (libsource (lib "eagle-import") (part "2N7000"))
    )
    (comp (ref "Q32")
      (value "2N7000")
      (footprint "eagle-import:TO92-DGS")
      (libsource (lib "eagle-import") (part "2N7000"))
    )
    (comp (ref "Q129")
      (value "2N7000")
      (footprint "eagle-import:TO92-DGS")
      (libsource (lib "eagle-import") (part "2N7000"))
    )
    (comp (ref "Q130")
      (value "2N7000")
      (footprint "eagle-import:TO92-DGS")
      (libsource (lib "eagle-import") (part "2N7000"))
    )
    (comp (ref "Q131")
      (value "2N7000")
      (footprint "eagle-import:TO92-DGS")
      (libsource (lib "eagle-import") (part "2N7000"))
    )
    (comp (ref "R21")
      (value "10k")
      (footprint "eagle-import:R_P2INCH")
      (libsource (lib "eagle-import") (part "R_P2INCH"))
    )
    (comp (ref "R22")
      (value "470")
      (footprint "eagle-import:R_P2INCH")
      (libsource (lib "eagle-import") (part "R_P2INCH"))
    )
    (comp (ref "R23")
      (value "10k")
      (footprint "eagle-import:R_P2INCH")
      (libsource (lib "eagle-import") (part "R_P2INCH"))
    )
    (comp (ref "R24")
      (value "470")
      (footprint "eagle-import:R_P2INCH")
      (libsource (lib "eagle-import") (part "R_P2INCH"))
    )
    (comp (ref "R25")
      (value "10k")
      (footprint "eagle-import:R_P2INCH")
      (libsource (lib "eagle-import") (part "R_P2INCH"))
    )
    (comp (ref "R26")
      (value "470")
      (footprint "eagle-import:R_P2INCH")
      (libsource (lib "eagle-import") (part "R_P2INCH"))
    )
    (comp (ref "R27")
      (value "10k")
      (footprint "eagle-import:R_P2INCH")
      (libsource (lib "eagle-import") (part "R_P2INCH"))
    )
    (comp (ref "R28")
      (value "470")
      (footprint "eagle-import:R_P2INCH")
      (libsource (lib "eagle-import") (part "R_P2INCH"))
    )
    (comp (ref "R29")
      (value "10k")
      (footprint "eagle-import:R_P2INCH")
      (libsource (lib "eagle-import") (part "R_P2INCH"))
    )
    (comp (ref "R30")
      (value "470")
      (footprint "eagle-import:R_P2INCH")
      (libsource (lib "eagle-import") (part "R_P2INCH"))
    )
    (comp (ref "R31")
      (value "10k")
      (footprint "eagle-import:R_P2INCH")
      (libsource (lib "eagle-import") (part "R_P2INCH"))
    )
    (comp (ref "R32")
      (value "470")
      (footprint "eagle-import:R_P2INCH")
      (libsource (lib "eagle-import") (part "R_P2INCH"))
    )
    (comp (ref "R129")
      (value "10k")
      (footprint "eagle-import:R_P2INCH")
      (libsource (lib "eagle-import") (part "R_P2INCH"))
    )
    (comp (ref "R130")
      (value "470")
      (footprint "eagle-import:R_P2INCH")
      (libsource (lib "eagle-import") (part "R_P2INCH"))
    )
    (comp (ref "R131")
      (value "10k")
      (footprint "eagle-import:R_P2INCH")
      (libsource (lib "eagle-import") (part "R_P2INCH"))
    )
    (comp (ref "R132")
      (value "10k")
      (footprint "eagle-import:R_P2INCH")
      (libsource (lib "eagle-import") (part "R_P2INCH"))
    )
    (comp (ref "R177")
      (value "470")
      (footprint "eagle-import:R_P2INCH")
      (libsource (lib "eagle-import") (part "R_P2INCH"))
    )
    (comp (ref "R191")
      (value "10k")
      (footprint "eagle-import:R_P2INCH")
      (libsource (lib "eagle-import") (part "R_P2INCH"))
    )
    (comp (ref "R192")
      (value "10k")
      (footprint "eagle-import:R_P2INCH")
      (libsource (lib "eagle-import") (part "R_P2INCH"))
    )
    (comp (ref "R193")
      (value "10k")
      (footprint "eagle-import:R_P2INCH")
      (libsource (lib "eagle-import") (part "R_P2INCH"))
    )
    (comp (ref "R194")
      (value "10k")
      (footprint "eagle-import:R_P2INCH")
      (libsource (lib "eagle-import") (part "R_P2INCH"))
    )
    (comp (ref "R195")
      (value "10k")
      (footprint "eagle-import:R_P2INCH")
      (libsource (lib "eagle-import") (part "R_P2INCH"))
    )
    (comp (ref "R196")
      (value "10k")
      (footprint "eagle-import:R_P2INCH")
      (libsource (lib "eagle-import") (part "R_P2INCH"))
    )
    (comp (ref "TP1")
      (value "TEST_LOOP")
      (footprint "eagle-import:TEST_LOOP")
      (libsource (lib "eagle-import") (part "TEST_LOOP"))
    )
  )
  (nets
    (net (code "1") (name "+5V") (class "Default")
      (node (ref "C1") (pin "1") (pinfunction "1_1") (pintype "passive"))
      (node (ref "C2") (pin "1") (pinfunction "1_1") (pintype "passive"))
      (node (ref "C3") (pin "1") (pinfunction "1_1") (pintype "passive"))
      (node (ref "C4") (pin "1") (pinfunction "1_1") (pintype "passive"))
      (node (ref "C5") (pin "1") (pinfunction "1_1") (pintype "passive"))
      (node (ref "C6") (pin "1") (pinfunction "1_1") (pintype "passive"))
      (node (ref "C7") (pin "A") (pinfunction "A_A") (pintype "passive"))
      (node (ref "C8") (pin "1") (pinfunction "1_1") (pintype "passive"))
      (node (ref "D1") (pin "A") (pinfunction "A_A") (pintype "passive"))
      (node (ref "D10") (pin "A") (pinfunction "A_A") (pintype "passive"))
      (node (ref "D11") (pin "A") (pinfunction "A_A") (pintype "passive"))
      (node (ref "D12") (pin "A") (pinfunction "A_A") (pintype "passive"))
      (node (ref "D13") (pin "A") (pinfunction "A_A") (pintype "passive"))
      (node (ref "D14") (pin "A") (pinfunction "A_A") (pintype "passive"))
      (node (ref "D15") (pin "A") (pinfunction "A_A") (pintype "passive"))
      (node (ref "D16") (pin "A") (pinfunction "A_A") (pintype "passive"))
      (node (ref "D17") (pin "A") (pinfunction "A_A") (pintype "passive"))
      (node (ref "D18") (pin "A") (pinfunction "A_A") (pintype "passive"))
      (node (ref "D19") (pin "A") (pinfunction "A_A") (pintype "passive"))
      (node (ref "D2") (pin "A") (pinfunction "A_A") (pintype "passive"))
      (node (ref "D20") (pin "A") (pinfunction "A_A") (pintype "passive"))
      (node (ref "D21") (pin "A") (pinfunction "A_A") (pintype "passive"))
      (node (ref "D22") (pin "A") (pinfunction "A_A") (pintype "passive"))
      (node (ref "D23") (pin "A") (pinfunction "A_A") (pintype "passive"))
      (node (ref "D24") (pin "A") (pinfunction "A_A") (pintype "passive"))
      (node (ref "D25") (pin "A") (pinfunction "A_A") (pintype "passive"))
      (node (ref "D26") (pin "A") (pinfunction "A_A") (pintype "passive"))
      (node (ref "D27") (pin "A") (pinfunction "A_A") (pintype "passive"))
      (node (ref "D28") (pin "A") (pinfunction "A_A") (pintype "passive"))
      (node (ref "D29") (pin "A") (pinfunction "A_A") (pintype "passive"))
      (node (ref "D3") (pin "A") (pinfunction "A_A") (pintype "passive"))
      (node (ref "D30") (pin "A") (pinfunction "A_A") (pintype "passive"))
      (node (ref "D31") (pin "A") (pinfunction "A_A") (pintype "passive"))
      (node (ref "D32") (pin "A") (pinfunction "A_A") (pintype "passive"))
      (node (ref "D4") (pin "A") (pinfunction "A_A") (pintype "passive"))
      (node (ref "D5") (pin "A") (pinfunction "A_A") (pintype "passive"))
      (node (ref "D6") (pin "A") (pinfunction "A_A") (pintype "passive"))
      (node (ref "D65") (pin "A") (pinfunction "A_A") (pintype "passive"))
      (node (ref "D66") (pin "A") (pinfunction "A_A") (pintype "passive"))
      (node (ref "D69") (pin "A") (pinfunction "A_A") (pintype "passive"))
      (node (ref "D7") (pin "A") (pinfunction "A_A") (pintype "passive"))
      (node (ref "D70") (pin "A") (pinfunction "A_A") (pintype "passive"))
      (node (ref "D71") (pin "A") (pinfunction "A_A") (pintype "passive"))
      (node (ref "D72") (pin "A") (pinfunction "A_A") (pintype "passive"))
      (node (ref "D73") (pin "A") (pinfunction "A_A") (pintype "passive"))
      (node (ref "D74") (pin "A") (pinfunction "A_A") (pintype "passive"))
      (node (ref "D75") (pin "A") (pinfunction "A_A") (pintype "passive"))
      (node (ref "D76") (pin "A") (pinfunction "A_A") (pintype "passive"))
      (node (ref "D77") (pin "A") (pinfunction "A_A") (pintype "passive"))
      (node (ref "D78") (pin "A") (pinfunction "A_A") (pintype "passive"))
      (node (ref "D79") (pin "A") (pinfunction "A_A") (pintype "passive"))
      (node (ref "D8") (pin "A") (pinfunction "A_A") (pintype "passive"))
      (node (ref "D80") (pin "A") (pinfunction "A_A") (pintype "passive"))
      (node (ref "D81") (pin "A") (pinfunction "A_A") (pintype "passive"))
      (node (ref "D82") (pin "A") (pinfunction "A_A") (pintype "passive"))
      (node (ref "D83") (pin "A") (pinfunction "A_A") (pintype "passive"))
      (node (ref "D84") (pin "A") (pinfunction "A_A") (pintype "passive"))
      (node (ref "D85") (pin "A") (pinfunction "A_A") (pintype "passive"))
      (node (ref "D86") (pin "A") (pinfunction "A_A") (pintype "passive"))
      (node (ref "D9") (pin "A") (pinfunction "A_A") (pintype "passive"))
      (node (ref "R1") (pin "2") (pinfunction "2_2") (pintype "passive"))
      (node (ref "R11") (pin "2") (pinfunction "2_2") (pintype "passive"))
      (node (ref "R129") (pin "2") (pinfunction "2_2") (pintype "passive"))
      (node (ref "R13") (pin "2") (pinfunction "2_2") (pintype "passive"))
      (node (ref "R131") (pin "2") (pinfunction "2_2") (pintype "passive"))
      (node (ref "R132") (pin "2") (pinfunction "2_2") (pintype "passive"))
      (node (ref "R133") (pin "2") (pinfunction "2_2") (pintype "passive"))
      (node (ref "R135") (pin "2") (pinfunction "2_2") (pintype "passive"))
      (node (ref "R136") (pin "2") (pinfunction "2_2") (pintype "passive"))
      (node (ref "R145") (pin "2") (pinfunction "2_2") (pintype "passive"))
      (node (ref "R147") (pin "2") (pinfunction "2_2") (pintype "passive"))
      (node (ref "R149") (pin "2") (pinfunction "2_2") (pintype "passive"))
      (node (ref "R15") (pin "2") (pinfunction "2_2") (pintype "passive"))
      (node (ref "R151") (pin "2") (pinfunction "2_2") (pintype "passive"))
      (node (ref "R153") (pin "2") (pinfunction "2_2") (pintype "passive"))
      (node (ref "R155") (pin "2") (pinfunction "2_2") (pintype "passive"))
      (node (ref "R157") (pin "2") (pinfunction "2_2") (pintype "passive"))
      (node (ref "R159") (pin "2") (pinfunction "2_2") (pintype "passive"))
      (node (ref "R161") (pin "2") (pinfunction "2_2") (pintype "passive"))
      (node (ref "R163") (pin "2") (pinfunction "2_2") (pintype "passive"))
      (node (ref "R165") (pin "2") (pinfunction "2_2") (pintype "passive"))
      (node (ref "R167") (pin "2") (pinfunction "2_2") (pintype "passive"))
      (node (ref "R169") (pin "2") (pinfunction "2_2") (pintype "passive"))
      (node (ref "R17") (pin "2") (pinfunction "2_2") (pintype "passive"))
      (node (ref "R171") (pin "2") (pinfunction "2_2") (pintype "passive"))
      (node (ref "R173") (pin "2") (pinfunction "2_2") (pintype "passive"))
      (node (ref "R175") (pin "2") (pinfunction "2_2") (pintype "passive"))
      (node (ref "R181") (pin "2") (pinfunction "2_2") (pintype "passive"))
      (node (ref "R182") (pin "2") (pinfunction "2_2") (pintype "passive"))
      (node (ref "R183") (pin "2") (pinfunction "2_2") (pintype "passive"))
      (node (ref "R184") (pin "2") (pinfunction "2_2") (pintype "passive"))
      (node (ref "R185") (pin "2") (pinfunction "2_2") (pintype "passive"))
      (node (ref "R186") (pin "2") (pinfunction "2_2") (pintype "passive"))
      (node (ref "R187") (pin "2") (pinfunction "2_2") (pintype "passive"))
      (node (ref "R188") (pin "2") (pinfunction "2_2") (pintype "passive"))
      (node (ref "R189") (pin "2") (pinfunction "2_2") (pintype "passive"))
      (node (ref "R19") (pin "2") (pinfunction "2_2") (pintype "passive"))
      (node (ref "R190") (pin "2") (pinfunction "2_2") (pintype "passive"))
      (node (ref "R191") (pin "2") (pinfunction "2_2") (pintype "passive"))
      (node (ref "R192") (pin "2") (pinfunction "2_2") (pintype "passive"))
      (node (ref "R193") (pin "2") (pinfunction "2_2") (pintype "passive"))
      (node (ref "R194") (pin "2") (pinfunction "2_2") (pintype "passive"))
      (node (ref "R195") (pin "2") (pinfunction "2_2") (pintype "passive"))
      (node (ref "R196") (pin "2") (pinfunction "2_2") (pintype "passive"))
      (node (ref "R197") (pin "2") (pinfunction "2_2") (pintype "passive"))
      (node (ref "R198") (pin "2") (pinfunction "2_2") (pintype "passive"))
      (node (ref "R199") (pin "2") (pinfunction "2_2") (pintype "passive"))
      (node (ref "R200") (pin "2") (pinfunction "2_2") (pintype "passive"))
      (node (ref "R201") (pin "2") (pinfunction "2_2") (pintype "passive"))
      (node (ref "R202") (pin "2") (pinfunction "2_2") (pintype "passive"))
      (node (ref "R203") (pin "2") (pinfunction "2_2") (pintype "passive"))
      (node (ref "R204") (pin "2") (pinfunction "2_2") (pintype "passive"))
      (node (ref "R205") (pin "2") (pinfunction "2_2") (pintype "passive"))
      (node (ref "R206") (pin "2") (pinfunction "2_2") (pintype "passive"))
      (node (ref "R207") (pin "2") (pinfunction "2_2") (pintype "passive"))
      (node (ref "R208") (pin "2") (pinfunction "2_2") (pintype "passive"))
      (node (ref "R209") (pin "2") (pinfunction "2_2") (pintype "passive"))
      (node (ref "R21") (pin "2") (pinfunction "2_2") (pintype "passive"))
      (node (ref "R210") (pin "2") (pinfunction "2_2") (pintype "passive"))
      (node (ref "R211") (pin "2") (pinfunction "2_2") (pintype "passive"))
      (node (ref "R212") (pin "2") (pinfunction "2_2") (pintype "passive"))
      (node (ref "R23") (pin "2") (pinfunction "2_2") (pintype "passive"))
      (node (ref "R25") (pin "2") (pinfunction "2_2") (pintype "passive"))
      (node (ref "R27") (pin "2") (pinfunction "2_2") (pintype "passive"))
      (node (ref "R29") (pin "2") (pinfunction "2_2") (pintype "passive"))
      (node (ref "R3") (pin "2") (pinfunction "2_2") (pintype "passive"))
      (node (ref "R31") (pin "2") (pinfunction "2_2") (pintype "passive"))
      (node (ref "R33") (pin "2") (pinfunction "2_2") (pintype "passive"))
      (node (ref "R35") (pin "2") (pinfunction "2_2") (pintype "passive"))
      (node (ref "R37") (pin "2") (pinfunction "2_2") (pintype "passive"))
      (node (ref "R39") (pin "2") (pinfunction "2_2") (pintype "passive"))
      (node (ref "R41") (pin "2") (pinfunction "2_2") (pintype "passive"))
      (node (ref "R43") (pin "2") (pinfunction "2_2") (pintype "passive"))
      (node (ref "R45") (pin "2") (pinfunction "2_2") (pintype "passive"))
      (node (ref "R47") (pin "2") (pinfunction "2_2") (pintype "passive"))
      (node (ref "R49") (pin "2") (pinfunction "2_2") (pintype "passive"))
      (node (ref "R5") (pin "2") (pinfunction "2_2") (pintype "passive"))
      (node (ref "R51") (pin "2") (pinfunction "2_2") (pintype "passive"))
      (node (ref "R53") (pin "2") (pinfunction "2_2") (pintype "passive"))
      (node (ref "R55") (pin "2") (pinfunction "2_2") (pintype "passive"))
      (node (ref "R57") (pin "2") (pinfunction "2_2") (pintype "passive"))
      (node (ref "R59") (pin "2") (pinfunction "2_2") (pintype "passive"))
      (node (ref "R61") (pin "2") (pinfunction "2_2") (pintype "passive"))
      (node (ref "R63") (pin "2") (pinfunction "2_2") (pintype "passive"))
      (node (ref "R65") (pin "2") (pinfunction "2_2") (pintype "passive"))
      (node (ref "R66") (pin "2") (pinfunction "2_2") (pintype "passive"))
      (node (ref "R67") (pin "2") (pinfunction "2_2") (pintype "passive"))
      (node (ref "R68") (pin "2") (pinfunction "2_2") (pintype "passive"))
      (node (ref "R69") (pin "2") (pinfunction "2_2") (pintype "passive"))
      (node (ref "R7") (pin "2") (pinfunction "2_2") (pintype "passive"))
      (node (ref "R70") (pin "2") (pinfunction "2_2") (pintype "passive"))
      (node (ref "R71") (pin "2") (pinfunction "2_2") (pintype "passive"))
      (node (ref "R72") (pin "2") (pinfunction "2_2") (pintype "passive"))
      (node (ref "R73") (pin "2") (pinfunction "2_2") (pintype "passive"))
      (node (ref "R74") (pin "2") (pinfunction "2_2") (pintype "passive"))
      (node (ref "R75") (pin "2") (pinfunction "2_2") (pintype "passive"))
      (node (ref "R76") (pin "2") (pinfunction "2_2") (pintype "passive"))
      (node (ref "R77") (pin "2") (pinfunction "2_2") (pintype "passive"))
      (node (ref "R78") (pin "2") (pinfunction "2_2") (pintype "passive"))
      (node (ref "R79") (pin "2") (pinfunction "2_2") (pintype "passive"))
      (node (ref "R80") (pin "2") (pinfunction "2_2") (pintype "passive"))
      (node (ref "R9") (pin "2") (pinfunction "2_2") (pintype "passive"))
      (node (ref "TP5") (pin "P$1") (pinfunction "P$1_P$1") (pintype "bidirectional"))
    )
    (net (code "2") (name "DOUT0") (class "Default")
      (node (ref "J5") (pin "2") (pinfunction "2_2") (pintype "bidirectional"))
      (node (ref "Q142") (pin "D") (pinfunction "D_D") (pintype "passive"))
      (node (ref "R65") (pin "1") (pinfunction "1_1") (pintype "passive"))
    )
    (net (code "3") (name "DOUT1") (class "Default")
      (node (ref "J5") (pin "3") (pinfunction "3_3") (pintype "bidirectional"))
      (node (ref "Q147") (pin "D") (pinfunction "D_D") (pintype "passive"))
      (node (ref "R66") (pin "1") (pinfunction "1_1") (pintype "passive"))
    )
    (net (code "4") (name "DOUT2") (class "Default")
      (node (ref "J5") (pin "4") (pinfunction "4_4") (pintype "bidirectional"))
      (node (ref "Q152") (pin "D") (pinfunction "D_D") (pintype "passive"))
      (node (ref "R67") (pin "1") (pinfunction "1_1") (pintype "passive"))
    )
    (net (code "5") (name "DOUT3") (class "Default")
      (node (ref "J5") (pin "5") (pinfunction "5_5") (pintype "bidirectional"))
      (node (ref "Q157") (pin "D") (pinfunction "D_D") (pintype "passive"))
      (node (ref "R68") (pin "1") (pinfunction "1_1") (pintype "passive"))
    )
    (net (code "6") (name "DOUT4") (class "Default")
      (node (ref "J5") (pin "6") (pinfunction "6_6") (pintype "bidirectional"))
      (node (ref "Q162") (pin "D") (pinfunction "D_D") (pintype "passive"))
      (node (ref "R69") (pin "1") (pinfunction "1_1") (pintype "passive"))
    )
    (net (code "7") (name "DOUT5") (class "Default")
      (node (ref "J5") (pin "7") (pinfunction "7_7") (pintype "bidirectional"))
      (node (ref "Q167") (pin "D") (pinfunction "D_D") (pintype "passive"))
      (node (ref "R70") (pin "1") (pinfunction "1_1") (pintype "passive"))
    )
    (net (code "8") (name "DOUT6") (class "Default")
      (node (ref "J5") (pin "8") (pinfunction "8_8") (pintype "bidirectional"))
      (node (ref "Q172") (pin "D") (pinfunction "D_D") (pintype "passive"))
      (node (ref "R71") (pin "1") (pinfunction "1_1") (pintype "passive"))
    )
    (net (code "9") (name "DOUT7") (class "Default")
      (node (ref "J5") (pin "9") (pinfunction "9_9") (pintype "bidirectional"))
      (node (ref "Q177") (pin "D") (pinfunction "D_D") (pintype "passive"))
      (node (ref "R72") (pin "1") (pinfunction "1_1") (pintype "passive"))
    )
    (net (code "10") (name "DOUT8") (class "Default")
      (node (ref "J5") (pin "12") (pinfunction "12_12") (pintype "bidirectional"))
      (node (ref "Q182") (pin "D") (pinfunction "D_D") (pintype "passive"))
      (node (ref "R73") (pin "1") (pinfunction "1_1") (pintype "passive"))
    )
    (net (code "11") (name "DOUT9") (class "Default")
      (node (ref "J5") (pin "13") (pinfunction "13_13") (pintype "bidirectional"))
      (node (ref "Q187") (pin "D") (pinfunction "D_D") (pintype "passive"))
      (node (ref "R74") (pin "1") (pinfunction "1_1") (pintype "passive"))
    )
    (net (code "12") (name "DOUT10") (class "Default")
      (node (ref "J5") (pin "14") (pinfunction "14_14") (pintype "bidirectional"))
      (node (ref "Q192") (pin "D") (pinfunction "D_D") (pintype "passive"))
      (node (ref "R75") (pin "1") (pinfunction "1_1") (pintype "passive"))
    )
    (net (code "13") (name "DOUT11") (class "Default")
      (node (ref "J5") (pin "15") (pinfunction "15_15") (pintype "bidirectional"))
      (node (ref "Q197") (pin "D") (pinfunction "D_D") (pintype "passive"))
      (node (ref "R76") (pin "1") (pinfunction "1_1") (pintype "passive"))
    )
    (net (code "14") (name "DOUT12") (class "Default")
      (node (ref "J5") (pin "16") (pinfunction "16_16") (pintype "bidirectional"))
      (node (ref "Q202") (pin "D") (pinfunction "D_D") (pintype "passive"))
      (node (ref "R77") (pin "1") (pinfunction "1_1") (pintype "passive"))
    )
    (net (code "15") (name "DOUT13") (class "Default")
      (node (ref "J5") (pin "17") (pinfunction "17_17") (pintype "bidirectional"))
      (node (ref "Q207") (pin "D") (pinfunction "D_D") (pintype "passive"))
      (node (ref "R78") (pin "1") (pinfunction "1_1") (pintype "passive"))
    )
    (net (code "16") (name "DOUT14") (class "Default")
      (node (ref "J5") (pin "18") (pinfunction "18_18") (pintype "bidirectional"))
      (node (ref "Q212") (pin "D") (pinfunction "D_D") (pintype "passive"))
      (node (ref "R79") (pin "1") (pinfunction "1_1") (pintype "passive"))
    )
    (net (code "17") (name "DOUT15") (class "Default")
      (node (ref "J5") (pin "19") (pinfunction "19_19") (pintype "bidirectional"))
      (node (ref "Q217") (pin "D") (pinfunction "D_D") (pintype "passive"))
      (node (ref "R80") (pin "1") (pinfunction "1_1") (pintype "passive"))
    )
    (net (code "18") (name "E0") (class "Default")
      (node (ref "Q10") (pin "S") (pinfunction "S_S") (pintype "passive"))
      (node (ref "Q12") (pin "S") (pinfunction "S_S") (pintype "passive"))
      (node (ref "Q131") (pin "D") (pinfunction "D_D") (pintype "passive"))
      (node (ref "Q14") (pin "S") (pinfunction "S_S") (pintype "passive"))
      (node (ref "Q16") (pin "S") (pinfunction "S_S") (pintype "passive"))
      (node (ref "Q18") (pin "S") (pinfunction "S_S") (pintype "passive"))
      (node (ref "Q2") (pin "S") (pinfunction "S_S") (pintype "passive"))
      (node (ref "Q20") (pin "S") (pinfunction "S_S") (pintype "passive"))
      (node (ref "Q22") (pin "S") (pinfunction "S_S") (pintype "passive"))
      (node (ref "Q24") (pin "S") (pinfunction "S_S") (pintype "passive"))
      (node (ref "Q26") (pin "S") (pinfunction "S_S") (pintype "passive"))
      (node (ref "Q28") (pin "S") (pinfunction "S_S") (pintype "passive"))
      (node (ref "Q30") (pin "S") (pinfunction "S_S") (pintype "passive"))
      (node (ref "Q32") (pin "S") (pinfunction "S_S") (pintype "passive"))
      (node (ref "Q4") (pin "S") (pinfunction "S_S") (pintype "passive"))
      (node (ref "Q6") (pin "S") (pinfunction "S_S") (pintype "passive"))
      (node (ref "Q8") (pin "S") (pinfunction "S_S") (pintype "passive"))
      (node (ref "R132") (pin "1") (pinfunction "1_1") (pintype "passive"))
    )
    (net (code "19") (name "E1") (class "Default")
      (node (ref "Q134") (pin "D") (pinfunction "D_D") (pintype "passive"))
      (node (ref "Q34") (pin "S") (pinfunction "S_S") (pintype "passive"))
      (node (ref "Q36") (pin "S") (pinfunction "S_S") (pintype "passive"))
      (node (ref "Q38") (pin "S") (pinfunction "S_S") (pintype "passive"))
      (node (ref "Q40") (pin "S") (pinfunction "S_S") (pintype "passive"))
      (node (ref "Q42") (pin "S") (pinfunction "S_S") (pintype "passive"))
      (node (ref "Q44") (pin "S") (pinfunction "S_S") (pintype "passive"))
      (node (ref "Q46") (pin "S") (pinfunction "S_S") (pintype "passive"))
      (node (ref "Q48") (pin "S") (pinfunction "S_S") (pintype "passive"))
      (node (ref "Q50") (pin "S") (pinfunction "S_S") (pintype "passive"))
      (node (ref "Q52") (pin "S") (pinfunction "S_S") (pintype "passive"))
      (node (ref "Q54") (pin "S") (pinfunction "S_S") (pintype "passive"))
      (node (ref "Q56") (pin "S") (pinfunction "S_S") (pintype "passive"))
      (node (ref "Q58") (pin "S") (pinfunction "S_S") (pintype "passive"))
      (node (ref "Q60") (pin "S") (pinfunction "S_S") (pintype "passive"))
      (node (ref "Q62") (pin "S") (pinfunction "S_S") (pintype "passive"))
      (node (ref "Q64") (pin "S") (pinfunction "S_S") (pintype "passive"))
      (node (ref "R136") (pin "1") (pinfunction "1_1") (pintype "passive"))
    )
    (net (code "20") (name "EN0_N") (class "Default")
      (node (ref "Q129") (pin "D") (pinfunction "D_D") (pintype "passive"))
      (node (ref "Q130") (pin "G") (pinfunction "G_G") (pintype "passive"))
      (node (ref "R129") (pin "1") (pinfunction "1_1") (pintype "passive"))
      (node (ref "R130") (pin "1") (pinfunction "1_1") (pintype "passive"))
      (node (ref "R177") (pin "1") (pinfunction "1_1") (pintype "passive"))
    )
    (net (code "21") (name "EN1_N") (class "Default")
      (node (ref "Q132") (pin "D") (pinfunction "D_D") (pintype "passive"))
      (node (ref "Q133") (pin "G") (pinfunction "G_G") (pintype "passive"))
      (node (ref "R133") (pin "1") (pinfunction "1_1") (pintype "passive"))
      (node (ref "R134") (pin "1") (pinfunction "1_1") (pintype "passive"))
      (node (ref "R178") (pin "1") (pinfunction "1_1") (pintype "passive"))
    )
    (net (code "22") (name "EN_0") (class "Default")
      (node (ref "Q130") (pin "D") (pinfunction "D_D") (pintype "passive"))
      (node (ref "Q131") (pin "G") (pinfunction "G_G") (pintype "passive"))
      (node (ref "R131") (pin "1") (pinfunction "1_1") (pintype "passive"))
    )
    (net (code "23") (name "EN_1") (class "Default")
      (node (ref "Q133") (pin "D") (pinfunction "D_D") (pintype "passive"))
      (node (ref "Q134") (pin "G") (pinfunction "G_G") (pintype "passive"))
      (node (ref "R135") (pin "1") (pinfunction "1_1") (pintype "passive"))
    )
    (net (code "24") (name "GND") (class "Default")
      (node (ref "C1") (pin "2") (pinfunction "2_2") (pintype "passive"))
      (node (ref "C2") (pin "2") (pinfunction "2_2") (pintype "passive"))
      (node (ref "C3") (pin "2") (pinfunction "2_2") (pintype "passive"))
      (node (ref "C4") (pin "2") (pinfunction "2_2") (pintype "passive"))
      (node (ref "C5") (pin "2") (pinfunction "2_2") (pintype "passive"))
      (node (ref "C6") (pin "2") (pinfunction "2_2") (pintype "passive"))
      (node (ref "C7") (pin "K") (pinfunction "K_K") (pintype "passive"))
      (node (ref "C8") (pin "2") (pinfunction "2_2") (pintype "passive"))
      (node (ref "J1") (pin "1") (pinfunction "1_1") (pintype "bidirectional"))
      (node (ref "J1") (pin "10") (pinfunction "10_10") (pintype "bidirectional"))
      (node (ref "J1") (pin "11") (pinfunction "11_11") (pintype "bidirectional"))
      (node (ref "J1") (pin "20") (pinfunction "20_20") (pintype "bidirectional"))
      (node (ref "J2") (pin "1") (pinfunction "1_1") (pintype "bidirectional"))
      (node (ref "J2") (pin "10") (pinfunction "10_10") (pintype "bidirectional"))
      (node (ref "J2") (pin "11") (pinfunction "11_11") (pintype "bidirectional"))
      (node (ref "J2") (pin "20") (pinfunction "20_20") (pintype "bidirectional"))
      (node (ref "J5") (pin "1") (pinfunction "1_1") (pintype "bidirectional"))
      (node (ref "J5") (pin "10") (pinfunction "10_10") (pintype "bidirectional"))
      (node (ref "J5") (pin "11") (pinfunction "11_11") (pintype "bidirectional"))
      (node (ref "J5") (pin "20") (pinfunction "20_20") (pintype "bidirectional"))
      (node (ref "Q1") (pin "S") (pinfunction "S_S") (pintype "passive"))
      (node (ref "Q11") (pin "S") (pinfunction "S_S") (pintype "passive"))
      (node (ref "Q129") (pin "S") (pinfunction "S_S") (pintype "passive"))
      (node (ref "Q13") (pin "S") (pinfunction "S_S") (pintype "passive"))
      (node (ref "Q130") (pin "S") (pinfunction "S_S") (pintype "passive"))
      (node (ref "Q131") (pin "S") (pinfunction "S_S") (pintype "passive"))
      (node (ref "Q132") (pin "S") (pinfunction "S_S") (pintype "passive"))
      (node (ref "Q133") (pin "S") (pinfunction "S_S") (pintype "passive"))
      (node (ref "Q134") (pin "S") (pinfunction "S_S") (pintype "passive"))
      (node (ref "Q142") (pin "S") (pinfunction "S_S") (pintype "passive"))
      (node (ref "Q143") (pin "S") (pinfunction "S_S") (pintype "passive"))
      (node (ref "Q147") (pin "S") (pinfunction "S_S") (pintype "passive"))
      (node (ref "Q148") (pin "S") (pinfunction "S_S") (pintype "passive"))
      (node (ref "Q15") (pin "S") (pinfunction "S_S") (pintype "passive"))
      (node (ref "Q152") (pin "S") (pinfunction "S_S") (pintype "passive"))
      (node (ref "Q153") (pin "S") (pinfunction "S_S") (pintype "passive"))
      (node (ref "Q157") (pin "S") (pinfunction "S_S") (pintype "passive"))
      (node (ref "Q158") (pin "S") (pinfunction "S_S") (pintype "passive"))
      (node (ref "Q162") (pin "S") (pinfunction "S_S") (pintype "passive"))
      (node (ref "Q163") (pin "S") (pinfunction "S_S") (pintype "passive"))
      (node (ref "Q167") (pin "S") (pinfunction "S_S") (pintype "passive"))
      (node (ref "Q168") (pin "S") (pinfunction "S_S") (pintype "passive"))
      (node (ref "Q17") (pin "S") (pinfunction "S_S") (pintype "passive"))
      (node (ref "Q172") (pin "S") (pinfunction "S_S") (pintype "passive"))
      (node (ref "Q173") (pin "S") (pinfunction "S_S") (pintype "passive"))
      (node (ref "Q177") (pin "S") (pinfunction "S_S") (pintype "passive"))
      (node (ref "Q178") (pin "S") (pinfunction "S_S") (pintype "passive"))
      (node (ref "Q182") (pin "S") (pinfunction "S_S") (pintype "passive"))
      (node (ref "Q183") (pin "S") (pinfunction "S_S") (pintype "passive"))
      (node (ref "Q187") (pin "S") (pinfunction "S_S") (pintype "passive"))
      (node (ref "Q188") (pin "S") (pinfunction "S_S") (pintype "passive"))
      (node (ref "Q19") (pin "S") (pinfunction "S_S") (pintype "passive"))
      (node (ref "Q192") (pin "S") (pinfunction "S_S") (pintype "passive"))
      (node (ref "Q193") (pin "S") (pinfunction "S_S") (pintype "passive"))
      (node (ref "Q197") (pin "S") (pinfunction "S_S") (pintype "passive"))
      (node (ref "Q198") (pin "S") (pinfunction "S_S") (pintype "passive"))
      (node (ref "Q202") (pin "S") (pinfunction "S_S") (pintype "passive"))
      (node (ref "Q203") (pin "S") (pinfunction "S_S") (pintype "passive"))
      (node (ref "Q207") (pin "S") (pinfunction "S_S") (pintype "passive"))
      (node (ref "Q208") (pin "S") (pinfunction "S_S") (pintype "passive"))
      (node (ref "Q21") (pin "S") (pinfunction "S_S") (pintype "passive"))
      (node (ref "Q212") (pin "S") (pinfunction "S_S") (pintype "passive"))
      (node (ref "Q213") (pin "S") (pinfunction "S_S") (pintype "passive"))
      (node (ref "Q217") (pin "S") (pinfunction "S_S") (pintype "passive"))
      (node (ref "Q218") (pin "S") (pinfunction "S_S") (pintype "passive"))
      (node (ref "Q23") (pin "S") (pinfunction "S_S") (pintype "passive"))
      (node (ref "Q25") (pin "S") (pinfunction "S_S") (pintype "passive"))
      (node (ref "Q27") (pin "S") (pinfunction "S_S") (pintype "passive"))
      (node (ref "Q29") (pin "S") (pinfunction "S_S") (pintype "passive"))
      (node (ref "Q3") (pin "S") (pinfunction "S_S") (pintype "passive"))
      (node (ref "Q31") (pin "S") (pinfunction "S_S") (pintype "passive"))
      (node (ref "Q33") (pin "S") (pinfunction "S_S") (pintype "passive"))
      (node (ref "Q35") (pin "S") (pinfunction "S_S") (pintype "passive"))
      (node (ref "Q37") (pin "S") (pinfunction "S_S") (pintype "passive"))
      (node (ref "Q39") (pin "S") (pinfunction "S_S") (pintype "passive"))
      (node (ref "Q41") (pin "S") (pinfunction "S_S") (pintype "passive"))
      (node (ref "Q43") (pin "S") (pinfunction "S_S") (pintype "passive"))
      (node (ref "Q45") (pin "S") (pinfunction "S_S") (pintype "passive"))
      (node (ref "Q47") (pin "S") (pinfunction "S_S") (pintype "passive"))
      (node (ref "Q49") (pin "S") (pinfunction "S_S") (pintype "passive"))
      (node (ref "Q5") (pin "S") (pinfunction "S_S") (pintype "passive"))
      (node (ref "Q51") (pin "S") (pinfunction "S_S") (pintype "passive"))
      (node (ref "Q53") (pin "S") (pinfunction "S_S") (pintype "passive"))
      (node (ref "Q55") (pin "S") (pinfunction "S_S") (pintype "passive"))
      (node (ref "Q57") (pin "S") (pinfunction "S_S") (pintype "passive"))
      (node (ref "Q59") (pin "S") (pinfunction "S_S") (pintype "passive"))
      (node (ref "Q61") (pin "S") (pinfunction "S_S") (pintype "passive"))
      (node (ref "Q63") (pin "S") (pinfunction "S_S") (pintype "passive"))
      (node (ref "Q7") (pin "S") (pinfunction "S_S") (pintype "passive"))
      (node (ref "Q9") (pin "S") (pinfunction "S_S") (pintype "passive"))
      (node (ref "TP6") (pin "P$1") (pinfunction "P$1_P$1") (pintype "bidirectional"))
    )
    (net (code "25") (name "Net-(D1-C)") (class "Default")
      (node (ref "D1") (pin "K") (pinfunction "C_K") (pintype "passive"))
      (node (ref "R2") (pin "2") (pinfunction "2_2") (pintype "passive"))
    )
    (net (code "26") (name "Net-(D2-C)") (class "Default")
      (node (ref "D2") (pin "K") (pinfunction "C_K") (pintype "passive"))
      (node (ref "R4") (pin "2") (pinfunction "2_2") (pintype "passive"))
    )
    (net (code "27") (name "Net-(D3-C)") (class "Default")
      (node (ref "D3") (pin "K") (pinfunction "C_K") (pintype "passive"))
      (node (ref "R6") (pin "2") (pinfunction "2_2") (pintype "passive"))
    )
    (net (code "28") (name "Net-(D4-C)") (class "Default")
      (node (ref "D4") (pin "K") (pinfunction "C_K") (pintype "passive"))
      (node (ref "R8") (pin "2") (pinfunction "2_2") (pintype "passive"))
    )
    (net (code "29") (name "Net-(D5-C)") (class "Default")
      (node (ref "D5") (pin "K") (pinfunction "C_K") (pintype "passive"))
      (node (ref "R10") (pin "2") (pinfunction "2_2") (pintype "passive"))
    )
    (net (code "30") (name "Net-(D6-C)") (class "Default")
      (node (ref "D6") (pin "K") (pinfunction "C_K") (pintype "passive"))
      (node (ref "R12") (pin "2") (pinfunction "2_2") (pintype "passive"))
    )
    (net (code "31") (name "Net-(D7-C)") (class "Default")
      (node (ref "D7") (pin "K") (pinfunction "C_K") (pintype "passive"))
      (node (ref "R14") (pin "2") (pinfunction "2_2") (pintype "passive"))
    )
    (net (code "32") (name "Net-(D8-C)") (class "Default")
      (node (ref "D8") (pin "K") (pinfunction "C_K") (pintype "passive"))
      (node (ref "R16") (pin "2") (pinfunction "2_2") (pintype "passive"))
    )
    (net (code "33") (name "Net-(D9-C)") (class "Default")
      (node (ref "D9") (pin "K") (pinfunction "C_K") (pintype "passive"))
      (node (ref "R18") (pin "2") (pinfunction "2_2") (pintype "passive"))
    )
    (net (code "34") (name "Net-(D10-C)") (class "Default")
      (node (ref "D10") (pin "K") (pinfunction "C_K") (pintype "passive"))
      (node (ref "R20") (pin "2") (pinfunction "2_2") (pintype "passive"))
    )
    (net (code "35") (name "Net-(D11-C)") (class "Default")
      (node (ref "D11") (pin "K") (pinfunction "C_K") (pintype "passive"))
      (node (ref "R22") (pin "2") (pinfunction "2_2") (pintype "passive"))
    )
    (net (code "36") (name "Net-(D12-C)") (class "Default")
      (node (ref "D12") (pin "K") (pinfunction "C_K") (pintype "passive"))
      (node (ref "R24") (pin "2") (pinfunction "2_2") (pintype "passive"))
    )
    (net (code "37") (name "Net-(D13-C)") (class "Default")
      (node (ref "D13") (pin "K") (pinfunction "C_K") (pintype "passive"))
      (node (ref "R26") (pin "2") (pinfunction "2_2") (pintype "passive"))
    )
    (net (code "38") (name "Net-(D14-C)") (class "Default")
      (node (ref "D14") (pin "K") (pinfunction "C_K") (pintype "passive"))
      (node (ref "R28") (pin "2") (pinfunction "2_2") (pintype "passive"))
    )
    (net (code "39") (name "Net-(D15-C)") (class "Default")
      (node (ref "D15") (pin "K") (pinfunction "C_K") (pintype "passive"))
      (node (ref "R30") (pin "2") (pinfunction "2_2") (pintype "passive"))
    )
    (net (code "40") (name "Net-(D16-C)") (class "Default")
      (node (ref "D16") (pin "K") (pinfunction "C_K") (pintype "passive"))
      (node (ref "R32") (pin "2") (pinfunction "2_2") (pintype "passive"))
    )
    (net (code "41") (name "Net-(D17-C)") (class "Default")
      (node (ref "D17") (pin "K") (pinfunction "C_K") (pintype "passive"))
      (node (ref "R34") (pin "2") (pinfunction "2_2") (pintype "passive"))
    )
    (net (code "42") (name "Net-(D18-C)") (class "Default")
      (node (ref "D18") (pin "K") (pinfunction "C_K") (pintype "passive"))
      (node (ref "R36") (pin "2") (pinfunction "2_2") (pintype "passive"))
    )
    (net (code "43") (name "Net-(D19-C)") (class "Default")
      (node (ref "D19") (pin "K") (pinfunction "C_K") (pintype "passive"))
      (node (ref "R38") (pin "2") (pinfunction "2_2") (pintype "passive"))
    )
    (net (code "44") (name "Net-(D20-C)") (class "Default")
      (node (ref "D20") (pin "K") (pinfunction "C_K") (pintype "passive"))
      (node (ref "R40") (pin "2") (pinfunction "2_2") (pintype "passive"))
    )
    (net (code "45") (name "Net-(D21-C)") (class "Default")
      (node (ref "D21") (pin "K") (pinfunction "C_K") (pintype "passive"))
      (node (ref "R42") (pin "2") (pinfunction "2_2") (pintype "passive"))
    )
    (net (code "46") (name "Net-(D22-C)") (class "Default")
      (node (ref "D22") (pin "K") (pinfunction "C_K") (pintype "passive"))
      (node (ref "R44") (pin "2") (pinfunction "2_2") (pintype "passive"))
    )
    (net (code "47") (name "Net-(D23-C)") (class "Default")
      (node (ref "D23") (pin "K") (pinfunction "C_K") (pintype "passive"))
      (node (ref "R46") (pin "2") (pinfunction "2_2") (pintype "passive"))
    )
    (net (code "48") (name "Net-(D24-C)") (class "Default")
      (node (ref "D24") (pin "K") (pinfunction "C_K") (pintype "passive"))
      (node (ref "R48") (pin "2") (pinfunction "2_2") (pintype "passive"))
    )
    (net (code "49") (name "Net-(D25-C)") (class "Default")
      (node (ref "D25") (pin "K") (pinfunction "C_K") (pintype "passive"))
      (node (ref "R50") (pin "2") (pinfunction "2_2") (pintype "passive"))
    )
    (net (code "50") (name "Net-(D26-C)") (class "Default")
      (node (ref "D26") (pin "K") (pinfunction "C_K") (pintype "passive"))
      (node (ref "R52") (pin "2") (pinfunction "2_2") (pintype "passive"))
    )
    (net (code "51") (name "Net-(D27-C)") (class "Default")
      (node (ref "D27") (pin "K") (pinfunction "C_K") (pintype "passive"))
      (node (ref "R54") (pin "2") (pinfunction "2_2") (pintype "passive"))
    )
    (net (code "52") (name "Net-(D28-C)") (class "Default")
      (node (ref "D28") (pin "K") (pinfunction "C_K") (pintype "passive"))
      (node (ref "R56") (pin "2") (pinfunction "2_2") (pintype "passive"))
    )
    (net (code "53") (name "Net-(D29-C)") (class "Default")
      (node (ref "D29") (pin "K") (pinfunction "C_K") (pintype "passive"))
      (node (ref "R58") (pin "2") (pinfunction "2_2") (pintype "passive"))
    )
    (net (code "54") (name "Net-(D30-C)") (class "Default")
      (node (ref "D30") (pin "K") (pinfunction "C_K") (pintype "passive"))
      (node (ref "R60") (pin "2") (pinfunction "2_2") (pintype "passive"))
    )
    (net (code "55") (name "Net-(D31-C)") (class "Default")
      (node (ref "D31") (pin "K") (pinfunction "C_K") (pintype "passive"))
      (node (ref "R62") (pin "2") (pinfunction "2_2") (pintype "passive"))
    )
    (net (code "56") (name "Net-(D32-C)") (class "Default")
      (node (ref "D32") (pin "K") (pinfunction "C_K") (pintype "passive"))
      (node (ref "R64") (pin "2") (pinfunction "2_2") (pintype "passive"))
    )
    (net (code "57") (name "Net-(D65-C)") (class "Default")
      (node (ref "D65") (pin "K") (pinfunction "C_K") (pintype "passive"))
      (node (ref "R130") (pin "2") (pinfunction "2_2") (pintype "passive"))
    )
    (net (code "58") (name "Net-(D66-C)") (class "Default")
      (node (ref "D66") (pin "K") (pinfunction "C_K") (pintype "passive"))
      (node (ref "R134") (pin "2") (pinfunction "2_2") (pintype "passive"))
    )
    (net (code "59") (name "Net-(D69-C)") (class "Default")
      (node (ref "D69") (pin "K") (pinfunction "C_K") (pintype "passive"))
      (node (ref "R146") (pin "2") (pinfunction "2_2") (pintype "passive"))
    )
    (net (code "60") (name "Net-(D70-C)") (class "Default")
      (node (ref "D70") (pin "K") (pinfunction "C_K") (pintype "passive"))
      (node (ref "R148") (pin "2") (pinfunction "2_2") (pintype "passive"))
    )
    (net (code "61") (name "Net-(D71-C)") (class "Default")
      (node (ref "D71") (pin "K") (pinfunction "C_K") (pintype "passive"))
      (node (ref "R150") (pin "2") (pinfunction "2_2") (pintype "passive"))
    )
    (net (code "62") (name "Net-(D72-C)") (class "Default")
      (node (ref "D72") (pin "K") (pinfunction "C_K") (pintype "passive"))
      (node (ref "R152") (pin "2") (pinfunction "2_2") (pintype "passive"))
    )
    (net (code "63") (name "Net-(D73-C)") (class "Default")
      (node (ref "D73") (pin "K") (pinfunction "C_K") (pintype "passive"))
      (node (ref "R154") (pin "2") (pinfunction "2_2") (pintype "passive"))
    )
    (net (code "64") (name "Net-(D74-C)") (class "Default")
      (node (ref "D74") (pin "K") (pinfunction "C_K") (pintype "passive"))
      (node (ref "R156") (pin "2") (pinfunction "2_2") (pintype "passive"))
    )
    (net (code "65") (name "Net-(D75-C)") (class "Default")
      (node (ref "D75") (pin "K") (pinfunction "C_K") (pintype "passive"))
      (node (ref "R158") (pin "2") (pinfunction "2_2") (pintype "passive"))
    )
    (net (code "66") (name "Net-(D76-C)") (class "Default")
      (node (ref "D76") (pin "K") (pinfunction "C_K") (pintype "passive"))
      (node (ref "R160") (pin "2") (pinfunction "2_2") (pintype "passive"))
    )
    (net (code "67") (name "Net-(D77-C)") (class "Default")
      (node (ref "D77") (pin "K") (pinfunction "C_K") (pintype "passive"))
      (node (ref "R162") (pin "2") (pinfunction "2_2") (pintype "passive"))
    )
    (net (code "68") (name "Net-(D78-C)") (class "Default")
      (node (ref "D78") (pin "K") (pinfunction "C_K") (pintype "passive"))
      (node (ref "R164") (pin "2") (pinfunction "2_2") (pintype "passive"))
    )
    (net (code "69") (name "Net-(D79-C)") (class "Default")
      (node (ref "D79") (pin "K") (pinfunction "C_K") (pintype "passive"))
      (node (ref "R166") (pin "2") (pinfunction "2_2") (pintype "passive"))
    )
    (net (code "70") (name "Net-(D80-C)") (class "Default")
      (node (ref "D80") (pin "K") (pinfunction "C_K") (pintype "passive"))
      (node (ref "R168") (pin "2") (pinfunction "2_2") (pintype "passive"))
    )
    (net (code "71") (name "Net-(D81-C)") (class "Default")
      (node (ref "D81") (pin "K") (pinfunction "C_K") (pintype "passive"))
      (node (ref "R170") (pin "2") (pinfunction "2_2") (pintype "passive"))
    )
    (net (code "72") (name "Net-(D82-C)") (class "Default")
      (node (ref "D82") (pin "K") (pinfunction "C_K") (pintype "passive"))
      (node (ref "R172") (pin "2") (pinfunction "2_2") (pintype "passive"))
    )
    (net (code "73") (name "Net-(D83-C)") (class "Default")
      (node (ref "D83") (pin "K") (pinfunction "C_K") (pintype "passive"))
      (node (ref "R174") (pin "2") (pinfunction "2_2") (pintype "passive"))
    )
    (net (code "74") (name "Net-(D84-C)") (class "Default")
      (node (ref "D84") (pin "K") (pinfunction "C_K") (pintype "passive"))
      (node (ref "R176") (pin "2") (pinfunction "2_2") (pintype "passive"))
    )
    (net (code "75") (name "Net-(D85-C)") (class "Default")
      (node (ref "D85") (pin "K") (pinfunction "C_K") (pintype "passive"))
      (node (ref "R177") (pin "2") (pinfunction "2_2") (pintype "passive"))
    )
    (net (code "76") (name "Net-(D86-C)") (class "Default")
      (node (ref "D86") (pin "K") (pinfunction "C_K") (pintype "passive"))
      (node (ref "R178") (pin "2") (pinfunction "2_2") (pintype "passive"))
    )
    (net (code "77") (name "Net-(Q1-PadD)") (class "Default")
      (node (ref "Q1") (pin "D") (pinfunction "D_D") (pintype "passive"))
      (node (ref "Q2") (pin "G") (pinfunction "G_G") (pintype "passive"))
      (node (ref "R1") (pin "1") (pinfunction "1_1") (pintype "passive"))
      (node (ref "R2") (pin "1") (pinfunction "1_1") (pintype "passive"))
    )
    (net (code "78") (name "Net-(Q3-PadD)") (class "Default")
      (node (ref "Q3") (pin "D") (pinfunction "D_D") (pintype "passive"))
      (node (ref "Q4") (pin "G") (pinfunction "G_G") (pintype "passive"))
      (node (ref "R3") (pin "1") (pinfunction "1_1") (pintype "passive"))
      (node (ref "R4") (pin "1") (pinfunction "1_1") (pintype "passive"))
    )
    (net (code "79") (name "Net-(Q5-PadD)") (class "Default")
      (node (ref "Q5") (pin "D") (pinfunction "D_D") (pintype "passive"))
      (node (ref "Q6") (pin "G") (pinfunction "G_G") (pintype "passive"))
      (node (ref "R5") (pin "1") (pinfunction "1_1") (pintype "passive"))
      (node (ref "R6") (pin "1") (pinfunction "1_1") (pintype "passive"))
    )
    (net (code "80") (name "Net-(Q7-PadD)") (class "Default")
      (node (ref "Q7") (pin "D") (pinfunction "D_D") (pintype "passive"))
      (node (ref "Q8") (pin "G") (pinfunction "G_G") (pintype "passive"))
      (node (ref "R7") (pin "1") (pinfunction "1_1") (pintype "passive"))
      (node (ref "R8") (pin "1") (pinfunction "1_1") (pintype "passive"))
    )
    (net (code "81") (name "Net-(Q10-PadG)") (class "Default")
      (node (ref "Q10") (pin "G") (pinfunction "G_G") (pintype "passive"))
      (node (ref "Q9") (pin "D") (pinfunction "D_D") (pintype "passive"))
      (node (ref "R10") (pin "1") (pinfunction "1_1") (pintype "passive"))
      (node (ref "R9") (pin "1") (pinfunction "1_1") (pintype "passive"))
    )
    (net (code "82") (name "Net-(Q11-PadD)") (class "Default")
      (node (ref "Q11") (pin "D") (pinfunction "D_D") (pintype "passive"))
      (node (ref "Q12") (pin "G") (pinfunction "G_G") (pintype "passive"))
      (node (ref "R11") (pin "1") (pinfunction "1_1") (pintype "passive"))
      (node (ref "R12") (pin "1") (pinfunction "1_1") (pintype "passive"))
    )
    (net (code "83") (name "Net-(Q13-PadD)") (class "Default")
      (node (ref "Q13") (pin "D") (pinfunction "D_D") (pintype "passive"))
      (node (ref "Q14") (pin "G") (pinfunction "G_G") (pintype "passive"))
      (node (ref "R13") (pin "1") (pinfunction "1_1") (pintype "passive"))
      (node (ref "R14") (pin "1") (pinfunction "1_1") (pintype "passive"))
    )
    (net (code "84") (name "Net-(Q15-PadD)") (class "Default")
      (node (ref "Q15") (pin "D") (pinfunction "D_D") (pintype "passive"))
      (node (ref "Q16") (pin "G") (pinfunction "G_G") (pintype "passive"))
      (node (ref "R15") (pin "1") (pinfunction "1_1") (pintype "passive"))
      (node (ref "R16") (pin "1") (pinfunction "1_1") (pintype "passive"))
    )
    (net (code "85") (name "Net-(Q17-PadD)") (class "Default")
      (node (ref "Q17") (pin "D") (pinfunction "D_D") (pintype "passive"))
      (node (ref "Q18") (pin "G") (pinfunction "G_G") (pintype "passive"))
      (node (ref "R17") (pin "1") (pinfunction "1_1") (pintype "passive"))
      (node (ref "R18") (pin "1") (pinfunction "1_1") (pintype "passive"))
    )
    (net (code "86") (name "Net-(Q19-PadD)") (class "Default")
      (node (ref "Q19") (pin "D") (pinfunction "D_D") (pintype "passive"))
      (node (ref "Q20") (pin "G") (pinfunction "G_G") (pintype "passive"))
      (node (ref "R19") (pin "1") (pinfunction "1_1") (pintype "passive"))
      (node (ref "R20") (pin "1") (pinfunction "1_1") (pintype "passive"))
    )
    (net (code "87") (name "Net-(Q21-PadD)") (class "Default")
      (node (ref "Q21") (pin "D") (pinfunction "D_D") (pintype "passive"))
      (node (ref "Q22") (pin "G") (pinfunction "G_G") (pintype "passive"))
      (node (ref "R21") (pin "1") (pinfunction "1_1") (pintype "passive"))
      (node (ref "R22") (pin "1") (pinfunction "1_1") (pintype "passive"))
    )
    (net (code "88") (name "Net-(Q23-PadD)") (class "Default")
      (node (ref "Q23") (pin "D") (pinfunction "D_D") (pintype "passive"))
      (node (ref "Q24") (pin "G") (pinfunction "G_G") (pintype "passive"))
      (node (ref "R23") (pin "1") (pinfunction "1_1") (pintype "passive"))
      (node (ref "R24") (pin "1") (pinfunction "1_1") (pintype "passive"))
    )
    (net (code "89") (name "Net-(Q25-PadD)") (class "Default")
      (node (ref "Q25") (pin "D") (pinfunction "D_D") (pintype "passive"))
      (node (ref "Q26") (pin "G") (pinfunction "G_G") (pintype "passive"))
      (node (ref "R25") (pin "1") (pinfunction "1_1") (pintype "passive"))
      (node (ref "R26") (pin "1") (pinfunction "1_1") (pintype "passive"))
    )
    (net (code "90") (name "Net-(Q27-PadD)") (class "Default")
      (node (ref "Q27") (pin "D") (pinfunction "D_D") (pintype "passive"))
      (node (ref "Q28") (pin "G") (pinfunction "G_G") (pintype "passive"))
      (node (ref "R27") (pin "1") (pinfunction "1_1") (pintype "passive"))
      (node (ref "R28") (pin "1") (pinfunction "1_1") (pintype "passive"))
    )
    (net (code "91") (name "Net-(Q29-PadD)") (class "Default")
      (node (ref "Q29") (pin "D") (pinfunction "D_D") (pintype "passive"))
      (node (ref "Q30") (pin "G") (pinfunction "G_G") (pintype "passive"))
      (node (ref "R29") (pin "1") (pinfunction "1_1") (pintype "passive"))
      (node (ref "R30") (pin "1") (pinfunction "1_1") (pintype "passive"))
    )
    (net (code "92") (name "Net-(Q31-PadD)") (class "Default")
      (node (ref "Q31") (pin "D") (pinfunction "D_D") (pintype "passive"))
      (node (ref "Q32") (pin "G") (pinfunction "G_G") (pintype "passive"))
      (node (ref "R31") (pin "1") (pinfunction "1_1") (pintype "passive"))
      (node (ref "R32") (pin "1") (pinfunction "1_1") (pintype "passive"))
    )
    (net (code "93") (name "Net-(Q33-PadD)") (class "Default")
      (node (ref "Q33") (pin "D") (pinfunction "D_D") (pintype "passive"))
      (node (ref "Q34") (pin "G") (pinfunction "G_G") (pintype "passive"))
      (node (ref "R33") (pin "1") (pinfunction "1_1") (pintype "passive"))
      (node (ref "R34") (pin "1") (pinfunction "1_1") (pintype "passive"))
    )
    (net (code "94") (name "Net-(Q35-PadD)") (class "Default")
      (node (ref "Q35") (pin "D") (pinfunction "D_D") (pintype "passive"))
      (node (ref "Q36") (pin "G") (pinfunction "G_G") (pintype "passive"))
      (node (ref "R35") (pin "1") (pinfunction "1_1") (pintype "passive"))
      (node (ref "R36") (pin "1") (pinfunction "1_1") (pintype "passive"))
    )
    (net (code "95") (name "Net-(Q37-PadD)") (class "Default")
      (node (ref "Q37") (pin "D") (pinfunction "D_D") (pintype "passive"))
      (node (ref "Q38") (pin "G") (pinfunction "G_G") (pintype "passive"))
      (node (ref "R37") (pin "1") (pinfunction "1_1") (pintype "passive"))
      (node (ref "R38") (pin "1") (pinfunction "1_1") (pintype "passive"))
    )
    (net (code "96") (name "Net-(Q39-PadD)") (class "Default")
      (node (ref "Q39") (pin "D") (pinfunction "D_D") (pintype "passive"))
      (node (ref "Q40") (pin "G") (pinfunction "G_G") (pintype "passive"))
      (node (ref "R39") (pin "1") (pinfunction "1_1") (pintype "passive"))
      (node (ref "R40") (pin "1") (pinfunction "1_1") (pintype "passive"))
    )
    (net (code "97") (name "Net-(Q41-PadD)") (class "Default")
      (node (ref "Q41") (pin "D") (pinfunction "D_D") (pintype "passive"))
      (node (ref "Q42") (pin "G") (pinfunction "G_G") (pintype "passive"))
      (node (ref "R41") (pin "1") (pinfunction "1_1") (pintype "passive"))
      (node (ref "R42") (pin "1") (pinfunction "1_1") (pintype "passive"))
    )
    (net (code "98") (name "Net-(Q43-PadD)") (class "Default")
      (node (ref "Q43") (pin "D") (pinfunction "D_D") (pintype "passive"))
      (node (ref "Q44") (pin "G") (pinfunction "G_G") (pintype "passive"))
      (node (ref "R43") (pin "1") (pinfunction "1_1") (pintype "passive"))
      (node (ref "R44") (pin "1") (pinfunction "1_1") (pintype "passive"))
    )
    (net (code "99") (name "Net-(Q45-PadD)") (class "Default")
      (node (ref "Q45") (pin "D") (pinfunction "D_D") (pintype "passive"))
      (node (ref "Q46") (pin "G") (pinfunction "G_G") (pintype "passive"))
      (node (ref "R45") (pin "1") (pinfunction "1_1") (pintype "passive"))
      (node (ref "R46") (pin "1") (pinfunction "1_1") (pintype "passive"))
    )
    (net (code "100") (name "Net-(Q47-PadD)") (class "Default")
      (node (ref "Q47") (pin "D") (pinfunction "D_D") (pintype "passive"))
      (node (ref "Q48") (pin "G") (pinfunction "G_G") (pintype "passive"))
      (node (ref "R47") (pin "1") (pinfunction "1_1") (pintype "passive"))
      (node (ref "R48") (pin "1") (pinfunction "1_1") (pintype "passive"))
    )
    (net (code "101") (name "Net-(Q49-PadD)") (class "Default")
      (node (ref "Q49") (pin "D") (pinfunction "D_D") (pintype "passive"))
      (node (ref "Q50") (pin "G") (pinfunction "G_G") (pintype "passive"))
      (node (ref "R49") (pin "1") (pinfunction "1_1") (pintype "passive"))
      (node (ref "R50") (pin "1") (pinfunction "1_1") (pintype "passive"))
    )
    (net (code "102") (name "Net-(Q51-PadD)") (class "Default")
      (node (ref "Q51") (pin "D") (pinfunction "D_D") (pintype "passive"))
      (node (ref "Q52") (pin "G") (pinfunction "G_G") (pintype "passive"))
      (node (ref "R51") (pin "1") (pinfunction "1_1") (pintype "passive"))
      (node (ref "R52") (pin "1") (pinfunction "1_1") (pintype "passive"))
    )
    (net (code "103") (name "Net-(Q53-PadD)") (class "Default")
      (node (ref "Q53") (pin "D") (pinfunction "D_D") (pintype "passive"))
      (node (ref "Q54") (pin "G") (pinfunction "G_G") (pintype "passive"))
      (node (ref "R53") (pin "1") (pinfunction "1_1") (pintype "passive"))
      (node (ref "R54") (pin "1") (pinfunction "1_1") (pintype "passive"))
    )
    (net (code "104") (name "Net-(Q55-PadD)") (class "Default")
      (node (ref "Q55") (pin "D") (pinfunction "D_D") (pintype "passive"))
      (node (ref "Q56") (pin "G") (pinfunction "G_G") (pintype "passive"))
      (node (ref "R55") (pin "1") (pinfunction "1_1") (pintype "passive"))
      (node (ref "R56") (pin "1") (pinfunction "1_1") (pintype "passive"))
    )
    (net (code "105") (name "Net-(Q57-PadD)") (class "Default")
      (node (ref "Q57") (pin "D") (pinfunction "D_D") (pintype "passive"))
      (node (ref "Q58") (pin "G") (pinfunction "G_G") (pintype "passive"))
      (node (ref "R57") (pin "1") (pinfunction "1_1") (pintype "passive"))
      (node (ref "R58") (pin "1") (pinfunction "1_1") (pintype "passive"))
    )
    (net (code "106") (name "Net-(Q59-PadD)") (class "Default")
      (node (ref "Q59") (pin "D") (pinfunction "D_D") (pintype "passive"))
      (node (ref "Q60") (pin "G") (pinfunction "G_G") (pintype "passive"))
      (node (ref "R59") (pin "1") (pinfunction "1_1") (pintype "passive"))
      (node (ref "R60") (pin "1") (pinfunction "1_1") (pintype "passive"))
    )
    (net (code "107") (name "Net-(Q61-PadD)") (class "Default")
      (node (ref "Q61") (pin "D") (pinfunction "D_D") (pintype "passive"))
      (node (ref "Q62") (pin "G") (pinfunction "G_G") (pintype "passive"))
      (node (ref "R61") (pin "1") (pinfunction "1_1") (pintype "passive"))
      (node (ref "R62") (pin "1") (pinfunction "1_1") (pintype "passive"))
    )
    (net (code "108") (name "Net-(Q63-PadD)") (class "Default")
      (node (ref "Q63") (pin "D") (pinfunction "D_D") (pintype "passive"))
      (node (ref "Q64") (pin "G") (pinfunction "G_G") (pintype "passive"))
      (node (ref "R63") (pin "1") (pinfunction "1_1") (pintype "passive"))
      (node (ref "R64") (pin "1") (pinfunction "1_1") (pintype "passive"))
    )
    (net (code "109") (name "Net-(Q141-PadD)") (class "Default")
      (node (ref "Q141") (pin "D") (pinfunction "D_D") (pintype "passive"))
      (node (ref "Q142") (pin "G") (pinfunction "G_G") (pintype "passive"))
      (node (ref "R145") (pin "1") (pinfunction "1_1") (pintype "passive"))
      (node (ref "R146") (pin "1") (pinfunction "1_1") (pintype "passive"))
    )
    (net (code "110") (name "Net-(Q141-PadS)") (class "Default")
      (node (ref "Q141") (pin "S") (pinfunction "S_S") (pintype "passive"))
      (node (ref "Q143") (pin "D") (pinfunction "D_D") (pintype "passive"))
    )
    (net (code "111") (name "Net-(Q146-PadD)") (class "Default")
      (node (ref "Q146") (pin "D") (pinfunction "D_D") (pintype "passive"))
      (node (ref "Q147") (pin "G") (pinfunction "G_G") (pintype "passive"))
      (node (ref "R147") (pin "1") (pinfunction "1_1") (pintype "passive"))
      (node (ref "R148") (pin "1") (pinfunction "1_1") (pintype "passive"))
    )
    (net (code "112") (name "Net-(Q146-PadS)") (class "Default")
      (node (ref "Q146") (pin "S") (pinfunction "S_S") (pintype "passive"))
      (node (ref "Q148") (pin "D") (pinfunction "D_D") (pintype "passive"))
    )
    (net (code "113") (name "Net-(Q151-PadD)") (class "Default")
      (node (ref "Q151") (pin "D") (pinfunction "D_D") (pintype "passive"))
      (node (ref "Q152") (pin "G") (pinfunction "G_G") (pintype "passive"))
      (node (ref "R149") (pin "1") (pinfunction "1_1") (pintype "passive"))
      (node (ref "R150") (pin "1") (pinfunction "1_1") (pintype "passive"))
    )
    (net (code "114") (name "Net-(Q151-PadS)") (class "Default")
      (node (ref "Q151") (pin "S") (pinfunction "S_S") (pintype "passive"))
      (node (ref "Q153") (pin "D") (pinfunction "D_D") (pintype "passive"))
    )
    (net (code "115") (name "Net-(Q156-PadD)") (class "Default")
      (node (ref "Q156") (pin "D") (pinfunction "D_D") (pintype "passive"))
      (node (ref "Q157") (pin "G") (pinfunction "G_G") (pintype "passive"))
      (node (ref "R151") (pin "1") (pinfunction "1_1") (pintype "passive"))
      (node (ref "R152") (pin "1") (pinfunction "1_1") (pintype "passive"))
    )
    (net (code "116") (name "Net-(Q156-PadS)") (class "Default")
      (node (ref "Q156") (pin "S") (pinfunction "S_S") (pintype "passive"))
      (node (ref "Q158") (pin "D") (pinfunction "D_D") (pintype "passive"))
    )
    (net (code "117") (name "Net-(Q161-PadD)") (class "Default")
      (node (ref "Q161") (pin "D") (pinfunction "D_D") (pintype "passive"))
      (node (ref "Q162") (pin "G") (pinfunction "G_G") (pintype "passive"))
      (node (ref "R153") (pin "1") (pinfunction "1_1") (pintype "passive"))
      (node (ref "R154") (pin "1") (pinfunction "1_1") (pintype "passive"))
    )
    (net (code "118") (name "Net-(Q161-PadS)") (class "Default")
      (node (ref "Q161") (pin "S") (pinfunction "S_S") (pintype "passive"))
      (node (ref "Q163") (pin "D") (pinfunction "D_D") (pintype "passive"))
    )
    (net (code "119") (name "Net-(Q166-PadD)") (class "Default")
      (node (ref "Q166") (pin "D") (pinfunction "D_D") (pintype "passive"))
      (node (ref "Q167") (pin "G") (pinfunction "G_G") (pintype "passive"))
      (node (ref "R155") (pin "1") (pinfunction "1_1") (pintype "passive"))
      (node (ref "R156") (pin "1") (pinfunction "1_1") (pintype "passive"))
    )
    (net (code "120") (name "Net-(Q166-PadS)") (class "Default")
      (node (ref "Q166") (pin "S") (pinfunction "S_S") (pintype "passive"))
      (node (ref "Q168") (pin "D") (pinfunction "D_D") (pintype "passive"))
    )
    (net (code "121") (name "Net-(Q171-PadD)") (class "Default")
      (node (ref "Q171") (pin "D") (pinfunction "D_D") (pintype "passive"))
      (node (ref "Q172") (pin "G") (pinfunction "G_G") (pintype "passive"))
      (node (ref "R157") (pin "1") (pinfunction "1_1") (pintype "passive"))
      (node (ref "R158") (pin "1") (pinfunction "1_1") (pintype "passive"))
    )
    (net (code "122") (name "Net-(Q171-PadS)") (class "Default")
      (node (ref "Q171") (pin "S") (pinfunction "S_S") (pintype "passive"))
      (node (ref "Q173") (pin "D") (pinfunction "D_D") (pintype "passive"))
    )
    (net (code "123") (name "Net-(Q176-PadD)") (class "Default")
      (node (ref "Q176") (pin "D") (pinfunction "D_D") (pintype "passive"))
      (node (ref "Q177") (pin "G") (pinfunction "G_G") (pintype "passive"))
      (node (ref "R159") (pin "1") (pinfunction "1_1") (pintype "passive"))
      (node (ref "R160") (pin "1") (pinfunction "1_1") (pintype "passive"))
    )
    (net (code "124") (name "Net-(Q176-PadS)") (class "Default")
      (node (ref "Q176") (pin "S") (pinfunction "S_S") (pintype "passive"))
      (node (ref "Q178") (pin "D") (pinfunction "D_D") (pintype "passive"))
    )
    (net (code "125") (name "Net-(Q181-PadD)") (class "Default")
      (node (ref "Q181") (pin "D") (pinfunction "D_D") (pintype "passive"))
      (node (ref "Q182") (pin "G") (pinfunction "G_G") (pintype "passive"))
      (node (ref "R161") (pin "1") (pinfunction "1_1") (pintype "passive"))
      (node (ref "R162") (pin "1") (pinfunction "1_1") (pintype "passive"))
    )
    (net (code "126") (name "Net-(Q181-PadS)") (class "Default")
      (node (ref "Q181") (pin "S") (pinfunction "S_S") (pintype "passive"))
      (node (ref "Q183") (pin "D") (pinfunction "D_D") (pintype "passive"))
    )
    (net (code "127") (name "Net-(Q186-PadD)") (class "Default")
      (node (ref "Q186") (pin "D") (pinfunction "D_D") (pintype "passive"))
      (node (ref "Q187") (pin "G") (pinfunction "G_G") (pintype "passive"))
      (node (ref "R163") (pin "1") (pinfunction "1_1") (pintype "passive"))
      (node (ref "R164") (pin "1") (pinfunction "1_1") (pintype "passive"))
    )
    (net (code "128") (name "Net-(Q186-PadS)") (class "Default")
      (node (ref "Q186") (pin "S") (pinfunction "S_S") (pintype "passive"))
      (node (ref "Q188") (pin "D") (pinfunction "D_D") (pintype "passive"))
    )
    (net (code "129") (name "Net-(Q191-PadD)") (class "Default")
      (node (ref "Q191") (pin "D") (pinfunction "D_D") (pintype "passive"))
      (node (ref "Q192") (pin "G") (pinfunction "G_G") (pintype "passive"))
      (node (ref "R165") (pin "1") (pinfunction "1_1") (pintype "passive"))
      (node (ref "R166") (pin "1") (pinfunction "1_1") (pintype "passive"))
    )
    (net (code "130") (name "Net-(Q191-PadS)") (class "Default")
      (node (ref "Q191") (pin "S") (pinfunction "S_S") (pintype "passive"))
      (node (ref "Q193") (pin "D") (pinfunction "D_D") (pintype "passive"))
    )
    (net (code "131") (name "Net-(Q196-PadD)") (class "Default")
      (node (ref "Q196") (pin "D") (pinfunction "D_D") (pintype "passive"))
      (node (ref "Q197") (pin "G") (pinfunction "G_G") (pintype "passive"))
      (node (ref "R167") (pin "1") (pinfunction "1_1") (pintype "passive"))
      (node (ref "R168") (pin "1") (pinfunction "1_1") (pintype "passive"))
    )
    (net (code "132") (name "Net-(Q196-PadS)") (class "Default")
      (node (ref "Q196") (pin "S") (pinfunction "S_S") (pintype "passive"))
      (node (ref "Q198") (pin "D") (pinfunction "D_D") (pintype "passive"))
    )
    (net (code "133") (name "Net-(Q201-PadD)") (class "Default")
      (node (ref "Q201") (pin "D") (pinfunction "D_D") (pintype "passive"))
      (node (ref "Q202") (pin "G") (pinfunction "G_G") (pintype "passive"))
      (node (ref "R169") (pin "1") (pinfunction "1_1") (pintype "passive"))
      (node (ref "R170") (pin "1") (pinfunction "1_1") (pintype "passive"))
    )
    (net (code "134") (name "Net-(Q201-PadS)") (class "Default")
      (node (ref "Q201") (pin "S") (pinfunction "S_S") (pintype "passive"))
      (node (ref "Q203") (pin "D") (pinfunction "D_D") (pintype "passive"))
    )
    (net (code "135") (name "Net-(Q206-PadD)") (class "Default")
      (node (ref "Q206") (pin "D") (pinfunction "D_D") (pintype "passive"))
      (node (ref "Q207") (pin "G") (pinfunction "G_G") (pintype "passive"))
      (node (ref "R171") (pin "1") (pinfunction "1_1") (pintype "passive"))
      (node (ref "R172") (pin "1") (pinfunction "1_1") (pintype "passive"))
    )
    (net (code "136") (name "Net-(Q206-PadS)") (class "Default")
      (node (ref "Q206") (pin "S") (pinfunction "S_S") (pintype "passive"))
      (node (ref "Q208") (pin "D") (pinfunction "D_D") (pintype "passive"))
    )
    (net (code "137") (name "Net-(Q211-PadD)") (class "Default")
      (node (ref "Q211") (pin "D") (pinfunction "D_D") (pintype "passive"))
      (node (ref "Q212") (pin "G") (pinfunction "G_G") (pintype "passive"))
      (node (ref "R173") (pin "1") (pinfunction "1_1") (pintype "passive"))
      (node (ref "R174") (pin "1") (pinfunction "1_1") (pintype "passive"))
    )
    (net (code "138") (name "Net-(Q211-PadS)") (class "Default")
      (node (ref "Q211") (pin "S") (pinfunction "S_S") (pintype "passive"))
      (node (ref "Q213") (pin "D") (pinfunction "D_D") (pintype "passive"))
    )
    (net (code "139") (name "Net-(Q216-PadD)") (class "Default")
      (node (ref "Q216") (pin "D") (pinfunction "D_D") (pintype "passive"))
      (node (ref "Q217") (pin "G") (pinfunction "G_G") (pintype "passive"))
      (node (ref "R175") (pin "1") (pinfunction "1_1") (pintype "passive"))
      (node (ref "R176") (pin "1") (pinfunction "1_1") (pintype "passive"))
    )
    (net (code "140") (name "Net-(Q216-PadS)") (class "Default")
      (node (ref "Q216") (pin "S") (pinfunction "S_S") (pintype "passive"))
      (node (ref "Q218") (pin "D") (pinfunction "D_D") (pintype "passive"))
    )
    (net (code "141") (name "S0_D0") (class "Default")
      (node (ref "J1") (pin "2") (pinfunction "2_2") (pintype "bidirectional"))
      (node (ref "Q1") (pin "G") (pinfunction "G_G") (pintype "passive"))
    )
    (net (code "142") (name "S0_D1") (class "Default")
      (node (ref "J1") (pin "3") (pinfunction "3_3") (pintype "bidirectional"))
      (node (ref "Q3") (pin "G") (pinfunction "G_G") (pintype "passive"))
    )
    (net (code "143") (name "S0_D2") (class "Default")
      (node (ref "J1") (pin "4") (pinfunction "4_4") (pintype "bidirectional"))
      (node (ref "Q5") (pin "G") (pinfunction "G_G") (pintype "passive"))
    )
    (net (code "144") (name "S0_D3") (class "Default")
      (node (ref "J1") (pin "5") (pinfunction "5_5") (pintype "bidirectional"))
      (node (ref "Q7") (pin "G") (pinfunction "G_G") (pintype "passive"))
    )
    (net (code "145") (name "S0_D4") (class "Default")
      (node (ref "J1") (pin "6") (pinfunction "6_6") (pintype "bidirectional"))
      (node (ref "Q9") (pin "G") (pinfunction "G_G") (pintype "passive"))
    )
    (net (code "146") (name "S0_D5") (class "Default")
      (node (ref "J1") (pin "7") (pinfunction "7_7") (pintype "bidirectional"))
      (node (ref "Q11") (pin "G") (pinfunction "G_G") (pintype "passive"))
    )
    (net (code "147") (name "S0_D6") (class "Default")
      (node (ref "J1") (pin "8") (pinfunction "8_8") (pintype "bidirectional"))
      (node (ref "Q13") (pin "G") (pinfunction "G_G") (pintype "passive"))
    )
    (net (code "148") (name "S0_D7") (class "Default")
      (node (ref "J1") (pin "9") (pinfunction "9_9") (pintype "bidirectional"))
      (node (ref "Q15") (pin "G") (pinfunction "G_G") (pintype "passive"))
    )
    (net (code "149") (name "S0_D8") (class "Default")
      (node (ref "J1") (pin "12") (pinfunction "12_12") (pintype "bidirectional"))
      (node (ref "Q17") (pin "G") (pinfunction "G_G") (pintype "passive"))
    )
    (net (code "150") (name "S0_D9") (class "Default")
      (node (ref "J1") (pin "13") (pinfunction "13_13") (pintype "bidirectional"))
      (node (ref "Q19") (pin "G") (pinfunction "G_G") (pintype "passive"))
    )
    (net (code "151") (name "S0_D10") (class "Default")
      (node (ref "J1") (pin "14") (pinfunction "14_14") (pintype "bidirectional"))
      (node (ref "Q21") (pin "G") (pinfunction "G_G") (pintype "passive"))
    )
    (net (code "152") (name "S0_D11") (class "Default")
      (node (ref "J1") (pin "15") (pinfunction "15_15") (pintype "bidirectional"))
      (node (ref "Q23") (pin "G") (pinfunction "G_G") (pintype "passive"))
    )
    (net (code "153") (name "S0_D12") (class "Default")
      (node (ref "J1") (pin "16") (pinfunction "16_16") (pintype "bidirectional"))
      (node (ref "Q25") (pin "G") (pinfunction "G_G") (pintype "passive"))
    )
    (net (code "154") (name "S0_D13") (class "Default")
      (node (ref "J1") (pin "17") (pinfunction "17_17") (pintype "bidirectional"))
      (node (ref "Q27") (pin "G") (pinfunction "G_G") (pintype "passive"))
    )
    (net (code "155") (name "S0_D14") (class "Default")
      (node (ref "J1") (pin "18") (pinfunction "18_18") (pintype "bidirectional"))
      (node (ref "Q29") (pin "G") (pinfunction "G_G") (pintype "passive"))
    )
    (net (code "156") (name "S0_D15") (class "Default")
      (node (ref "J1") (pin "19") (pinfunction "19_19") (pintype "bidirectional"))
      (node (ref "Q31") (pin "G") (pinfunction "G_G") (pintype "passive"))
    )
    (net (code "157") (name "S1_D0") (class "Default")
      (node (ref "J2") (pin "2") (pinfunction "2_2") (pintype "bidirectional"))
      (node (ref "Q33") (pin "G") (pinfunction "G_G") (pintype "passive"))
    )
    (net (code "158") (name "S1_D1") (class "Default")
      (node (ref "J2") (pin "3") (pinfunction "3_3") (pintype "bidirectional"))
      (node (ref "Q35") (pin "G") (pinfunction "G_G") (pintype "passive"))
    )
    (net (code "159") (name "S1_D2") (class "Default")
      (node (ref "J2") (pin "4") (pinfunction "4_4") (pintype "bidirectional"))
      (node (ref "Q37") (pin "G") (pinfunction "G_G") (pintype "passive"))
    )
    (net (code "160") (name "S1_D3") (class "Default")
      (node (ref "J2") (pin "5") (pinfunction "5_5") (pintype "bidirectional"))
      (node (ref "Q39") (pin "G") (pinfunction "G_G") (pintype "passive"))
    )
    (net (code "161") (name "S1_D4") (class "Default")
      (node (ref "J2") (pin "6") (pinfunction "6_6") (pintype "bidirectional"))
      (node (ref "Q41") (pin "G") (pinfunction "G_G") (pintype "passive"))
    )
    (net (code "162") (name "S1_D5") (class "Default")
      (node (ref "J2") (pin "7") (pinfunction "7_7") (pintype "bidirectional"))
      (node (ref "Q43") (pin "G") (pinfunction "G_G") (pintype "passive"))
    )
    (net (code "163") (name "S1_D6") (class "Default")
      (node (ref "J2") (pin "8") (pinfunction "8_8") (pintype "bidirectional"))
      (node (ref "Q45") (pin "G") (pinfunction "G_G") (pintype "passive"))
    )
    (net (code "164") (name "S1_D7") (class "Default")
      (node (ref "J2") (pin "9") (pinfunction "9_9") (pintype "bidirectional"))
      (node (ref "Q47") (pin "G") (pinfunction "G_G") (pintype "passive"))
    )
    (net (code "165") (name "S1_D8") (class "Default")
      (node (ref "J2") (pin "12") (pinfunction "12_12") (pintype "bidirectional"))
      (node (ref "Q49") (pin "G") (pinfunction "G_G") (pintype "passive"))
    )
    (net (code "166") (name "S1_D9") (class "Default")
      (node (ref "J2") (pin "13") (pinfunction "13_13") (pintype "bidirectional"))
      (node (ref "Q51") (pin "G") (pinfunction "G_G") (pintype "passive"))
    )
    (net (code "167") (name "S1_D10") (class "Default")
      (node (ref "J2") (pin "14") (pinfunction "14_14") (pintype "bidirectional"))
      (node (ref "Q53") (pin "G") (pinfunction "G_G") (pintype "passive"))
    )
    (net (code "168") (name "S1_D11") (class "Default")
      (node (ref "J2") (pin "15") (pinfunction "15_15") (pintype "bidirectional"))
      (node (ref "Q55") (pin "G") (pinfunction "G_G") (pintype "passive"))
    )
    (net (code "169") (name "S1_D12") (class "Default")
      (node (ref "J2") (pin "16") (pinfunction "16_16") (pintype "bidirectional"))
      (node (ref "Q57") (pin "G") (pinfunction "G_G") (pintype "passive"))
    )
    (net (code "170") (name "S1_D13") (class "Default")
      (node (ref "J2") (pin "17") (pinfunction "17_17") (pintype "bidirectional"))
      (node (ref "Q59") (pin "G") (pinfunction "G_G") (pintype "passive"))
    )
    (net (code "171") (name "S1_D14") (class "Default")
      (node (ref "J2") (pin "18") (pinfunction "18_18") (pintype "bidirectional"))
      (node (ref "Q61") (pin "G") (pinfunction "G_G") (pintype "passive"))
    )
    (net (code "172") (name "S1_D15") (class "Default")
      (node (ref "J2") (pin "19") (pinfunction "19_19") (pintype "bidirectional"))
      (node (ref "Q63") (pin "G") (pinfunction "G_G") (pintype "passive"))
    )
    (net (code "173") (name "SEL0") (class "Default")
      (node (ref "Q129") (pin "G") (pinfunction "G_G") (pintype "passive"))
      (node (ref "TP1") (pin "P$1") (pinfunction "P$1_P$1") (pintype "bidirectional"))
    )
    (net (code "174") (name "SEL1") (class "Default")
      (node (ref "Q132") (pin "G") (pinfunction "G_G") (pintype "passive"))
      (node (ref "TP2") (pin "P$1") (pinfunction "P$1_P$1") (pintype "bidirectional"))
    )
    (net (code "175") (name "T0_D0") (class "Default")
      (node (ref "Q141") (pin "G") (pinfunction "G_G") (pintype "passive"))
      (node (ref "Q2") (pin "D") (pinfunction "D_D") (pintype "passive"))
      (node (ref "R181") (pin "1") (pinfunction "1_1") (pintype "passive"))
    )
    (net (code "176") (name "T0_D1") (class "Default")
      (node (ref "Q146") (pin "G") (pinfunction "G_G") (pintype "passive"))
      (node (ref "Q4") (pin "D") (pinfunction "D_D") (pintype "passive"))
      (node (ref "R182") (pin "1") (pinfunction "1_1") (pintype "passive"))
    )
    (net (code "177") (name "T0_D2") (class "Default")
      (node (ref "Q151") (pin "G") (pinfunction "G_G") (pintype "passive"))
      (node (ref "Q6") (pin "D") (pinfunction "D_D") (pintype "passive"))
      (node (ref "R183") (pin "1") (pinfunction "1_1") (pintype "passive"))
    )
    (net (code "178") (name "T0_D3") (class "Default")
      (node (ref "Q156") (pin "G") (pinfunction "G_G") (pintype "passive"))
      (node (ref "Q8") (pin "D") (pinfunction "D_D") (pintype "passive"))
      (node (ref "R184") (pin "1") (pinfunction "1_1") (pintype "passive"))
    )
    (net (code "179") (name "T0_D4") (class "Default")
      (node (ref "Q10") (pin "D") (pinfunction "D_D") (pintype "passive"))
      (node (ref "Q161") (pin "G") (pinfunction "G_G") (pintype "passive"))
      (node (ref "R185") (pin "1") (pinfunction "1_1") (pintype "passive"))
    )
    (net (code "180") (name "T0_D5") (class "Default")
      (node (ref "Q12") (pin "D") (pinfunction "D_D") (pintype "passive"))
      (node (ref "Q166") (pin "G") (pinfunction "G_G") (pintype "passive"))
      (node (ref "R186") (pin "1") (pinfunction "1_1") (pintype "passive"))
    )
    (net (code "181") (name "T0_D6") (class "Default")
      (node (ref "Q14") (pin "D") (pinfunction "D_D") (pintype "passive"))
      (node (ref "Q171") (pin "G") (pinfunction "G_G") (pintype "passive"))
      (node (ref "R187") (pin "1") (pinfunction "1_1") (pintype "passive"))
    )
    (net (code "182") (name "T0_D7") (class "Default")
      (node (ref "Q16") (pin "D") (pinfunction "D_D") (pintype "passive"))
      (node (ref "Q176") (pin "G") (pinfunction "G_G") (pintype "passive"))
      (node (ref "R188") (pin "1") (pinfunction "1_1") (pintype "passive"))
    )
    (net (code "183") (name "T0_D8") (class "Default")
      (node (ref "Q18") (pin "D") (pinfunction "D_D") (pintype "passive"))
      (node (ref "Q181") (pin "G") (pinfunction "G_G") (pintype "passive"))
      (node (ref "R189") (pin "1") (pinfunction "1_1") (pintype "passive"))
    )
    (net (code "184") (name "T0_D9") (class "Default")
      (node (ref "Q186") (pin "G") (pinfunction "G_G") (pintype "passive"))
      (node (ref "Q20") (pin "D") (pinfunction "D_D") (pintype "passive"))
      (node (ref "R190") (pin "1") (pinfunction "1_1") (pintype "passive"))
    )
    (net (code "185") (name "T0_D10") (class "Default")
      (node (ref "Q191") (pin "G") (pinfunction "G_G") (pintype "passive"))
      (node (ref "Q22") (pin "D") (pinfunction "D_D") (pintype "passive"))
      (node (ref "R191") (pin "1") (pinfunction "1_1") (pintype "passive"))
    )
    (net (code "186") (name "T0_D11") (class "Default")
      (node (ref "Q196") (pin "G") (pinfunction "G_G") (pintype "passive"))
      (node (ref "Q24") (pin "D") (pinfunction "D_D") (pintype "passive"))
      (node (ref "R192") (pin "1") (pinfunction "1_1") (pintype "passive"))
    )
    (net (code "187") (name "T0_D12") (class "Default")
      (node (ref "Q201") (pin "G") (pinfunction "G_G") (pintype "passive"))
      (node (ref "Q26") (pin "D") (pinfunction "D_D") (pintype "passive"))
      (node (ref "R193") (pin "1") (pinfunction "1_1") (pintype "passive"))
    )
    (net (code "188") (name "T0_D13") (class "Default")
      (node (ref "Q206") (pin "G") (pinfunction "G_G") (pintype "passive"))
      (node (ref "Q28") (pin "D") (pinfunction "D_D") (pintype "passive"))
      (node (ref "R194") (pin "1") (pinfunction "1_1") (pintype "passive"))
    )
    (net (code "189") (name "T0_D14") (class "Default")
      (node (ref "Q211") (pin "G") (pinfunction "G_G") (pintype "passive"))
      (node (ref "Q30") (pin "D") (pinfunction "D_D") (pintype "passive"))
      (node (ref "R195") (pin "1") (pinfunction "1_1") (pintype "passive"))
    )
    (net (code "190") (name "T0_D15") (class "Default")
      (node (ref "Q216") (pin "G") (pinfunction "G_G") (pintype "passive"))
      (node (ref "Q32") (pin "D") (pinfunction "D_D") (pintype "passive"))
      (node (ref "R196") (pin "1") (pinfunction "1_1") (pintype "passive"))
    )
    (net (code "191") (name "T1_D0") (class "Default")
      (node (ref "Q143") (pin "G") (pinfunction "G_G") (pintype "passive"))
      (node (ref "Q34") (pin "D") (pinfunction "D_D") (pintype "passive"))
      (node (ref "R197") (pin "1") (pinfunction "1_1") (pintype "passive"))
    )
    (net (code "192") (name "T1_D1") (class "Default")
      (node (ref "Q148") (pin "G") (pinfunction "G_G") (pintype "passive"))
      (node (ref "Q36") (pin "D") (pinfunction "D_D") (pintype "passive"))
      (node (ref "R198") (pin "1") (pinfunction "1_1") (pintype "passive"))
    )
    (net (code "193") (name "T1_D2") (class "Default")
      (node (ref "Q153") (pin "G") (pinfunction "G_G") (pintype "passive"))
      (node (ref "Q38") (pin "D") (pinfunction "D_D") (pintype "passive"))
      (node (ref "R199") (pin "1") (pinfunction "1_1") (pintype "passive"))
    )
    (net (code "194") (name "T1_D3") (class "Default")
      (node (ref "Q158") (pin "G") (pinfunction "G_G") (pintype "passive"))
      (node (ref "Q40") (pin "D") (pinfunction "D_D") (pintype "passive"))
      (node (ref "R200") (pin "1") (pinfunction "1_1") (pintype "passive"))
    )
    (net (code "195") (name "T1_D4") (class "Default")
      (node (ref "Q163") (pin "G") (pinfunction "G_G") (pintype "passive"))
      (node (ref "Q42") (pin "D") (pinfunction "D_D") (pintype "passive"))
      (node (ref "R201") (pin "1") (pinfunction "1_1") (pintype "passive"))
    )
    (net (code "196") (name "T1_D5") (class "Default")
      (node (ref "Q168") (pin "G") (pinfunction "G_G") (pintype "passive"))
      (node (ref "Q44") (pin "D") (pinfunction "D_D") (pintype "passive"))
      (node (ref "R202") (pin "1") (pinfunction "1_1") (pintype "passive"))
    )
    (net (code "197") (name "T1_D6") (class "Default")
      (node (ref "Q173") (pin "G") (pinfunction "G_G") (pintype "passive"))
      (node (ref "Q46") (pin "D") (pinfunction "D_D") (pintype "passive"))
      (node (ref "R203") (pin "1") (pinfunction "1_1") (pintype "passive"))
    )
    (net (code "198") (name "T1_D7") (class "Default")
      (node (ref "Q178") (pin "G") (pinfunction "G_G") (pintype "passive"))
      (node (ref "Q48") (pin "D") (pinfunction "D_D") (pintype "passive"))
      (node (ref "R204") (pin "1") (pinfunction "1_1") (pintype "passive"))
    )
    (net (code "199") (name "T1_D8") (class "Default")
      (node (ref "Q183") (pin "G") (pinfunction "G_G") (pintype "passive"))
      (node (ref "Q50") (pin "D") (pinfunction "D_D") (pintype "passive"))
      (node (ref "R205") (pin "1") (pinfunction "1_1") (pintype "passive"))
    )
    (net (code "200") (name "T1_D9") (class "Default")
      (node (ref "Q188") (pin "G") (pinfunction "G_G") (pintype "passive"))
      (node (ref "Q52") (pin "D") (pinfunction "D_D") (pintype "passive"))
      (node (ref "R206") (pin "1") (pinfunction "1_1") (pintype "passive"))
    )
    (net (code "201") (name "T1_D10") (class "Default")
      (node (ref "Q193") (pin "G") (pinfunction "G_G") (pintype "passive"))
      (node (ref "Q54") (pin "D") (pinfunction "D_D") (pintype "passive"))
      (node (ref "R207") (pin "1") (pinfunction "1_1") (pintype "passive"))
    )
    (net (code "202") (name "T1_D11") (class "Default")
      (node (ref "Q198") (pin "G") (pinfunction "G_G") (pintype "passive"))
      (node (ref "Q56") (pin "D") (pinfunction "D_D") (pintype "passive"))
      (node (ref "R208") (pin "1") (pinfunction "1_1") (pintype "passive"))
    )
    (net (code "203") (name "T1_D12") (class "Default")
      (node (ref "Q203") (pin "G") (pinfunction "G_G") (pintype "passive"))
      (node (ref "Q58") (pin "D") (pinfunction "D_D") (pintype "passive"))
      (node (ref "R209") (pin "1") (pinfunction "1_1") (pintype "passive"))
    )
    (net (code "204") (name "T1_D13") (class "Default")
      (node (ref "Q208") (pin "G") (pinfunction "G_G") (pintype "passive"))
      (node (ref "Q60") (pin "D") (pinfunction "D_D") (pintype "passive"))
      (node (ref "R210") (pin "1") (pinfunction "1_1") (pintype "passive"))
    )
    (net (code "205") (name "T1_D14") (class "Default")
      (node (ref "Q213") (pin "G") (pinfunction "G_G") (pintype "passive"))
      (node (ref "Q62") (pin "D") (pinfunction "D_D") (pintype "passive"))
      (node (ref "R211") (pin "1") (pinfunction "1_1") (pintype "passive"))
    )
    (net (code "206") (name "T1_D15") (class "Default")
      (node (ref "Q218") (pin "G") (pinfunction "G_G") (pintype "passive"))
      (node (ref "Q64") (pin "D") (pinfunction "D_D") (pintype "passive"))
      (node (ref "R212") (pin "1") (pinfunction "1_1") (pintype "passive"))
    )
  )
)
